# v0a.net
KiCad netlist of a schematic drawn in EAGLE
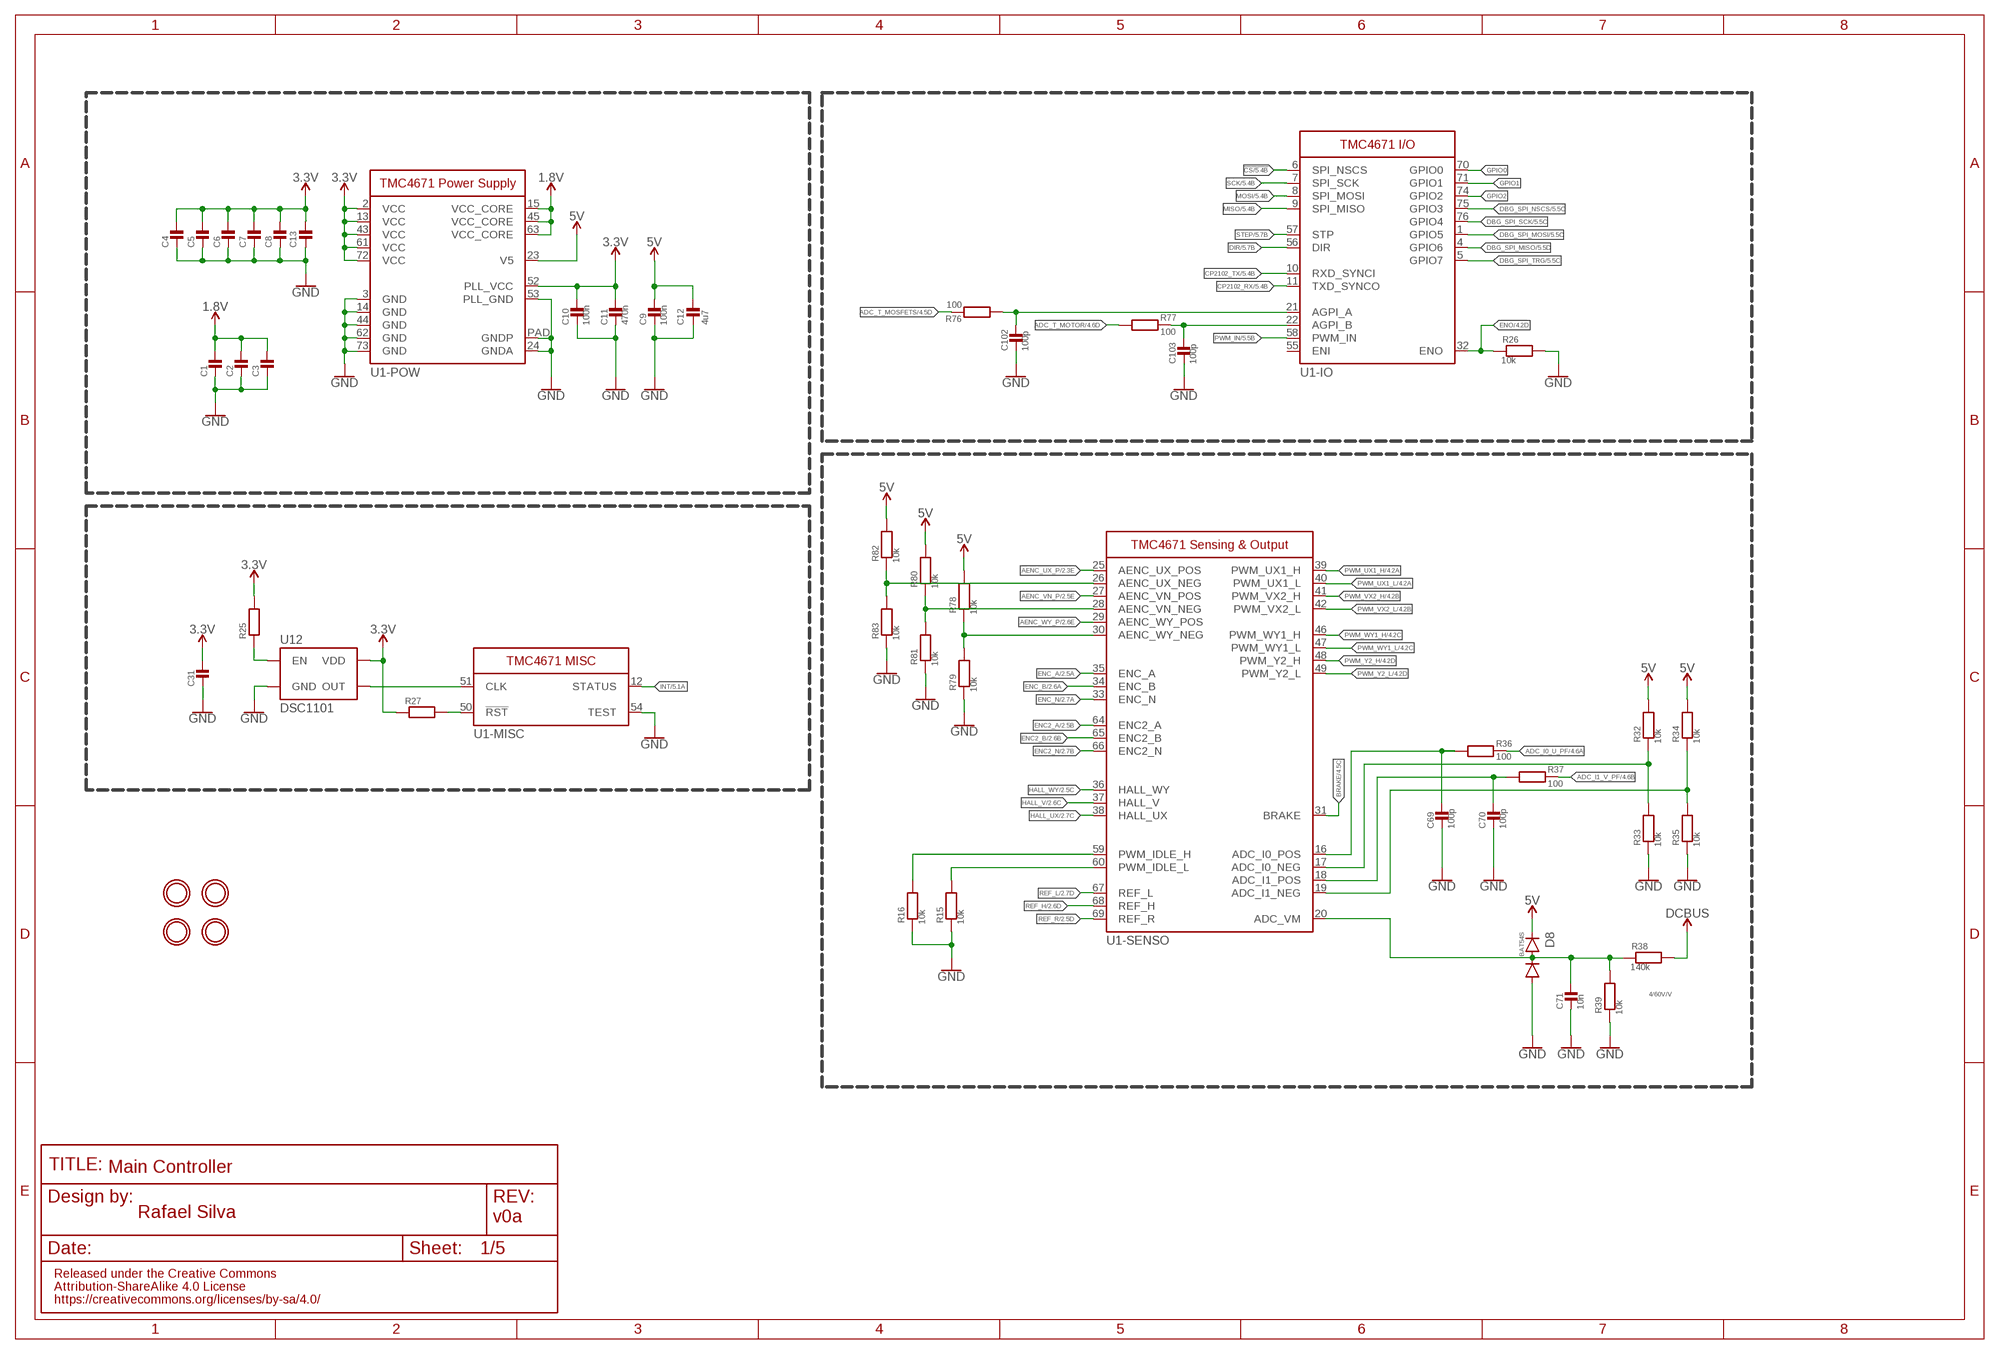
[diagram p0: schematic, sheet 1]
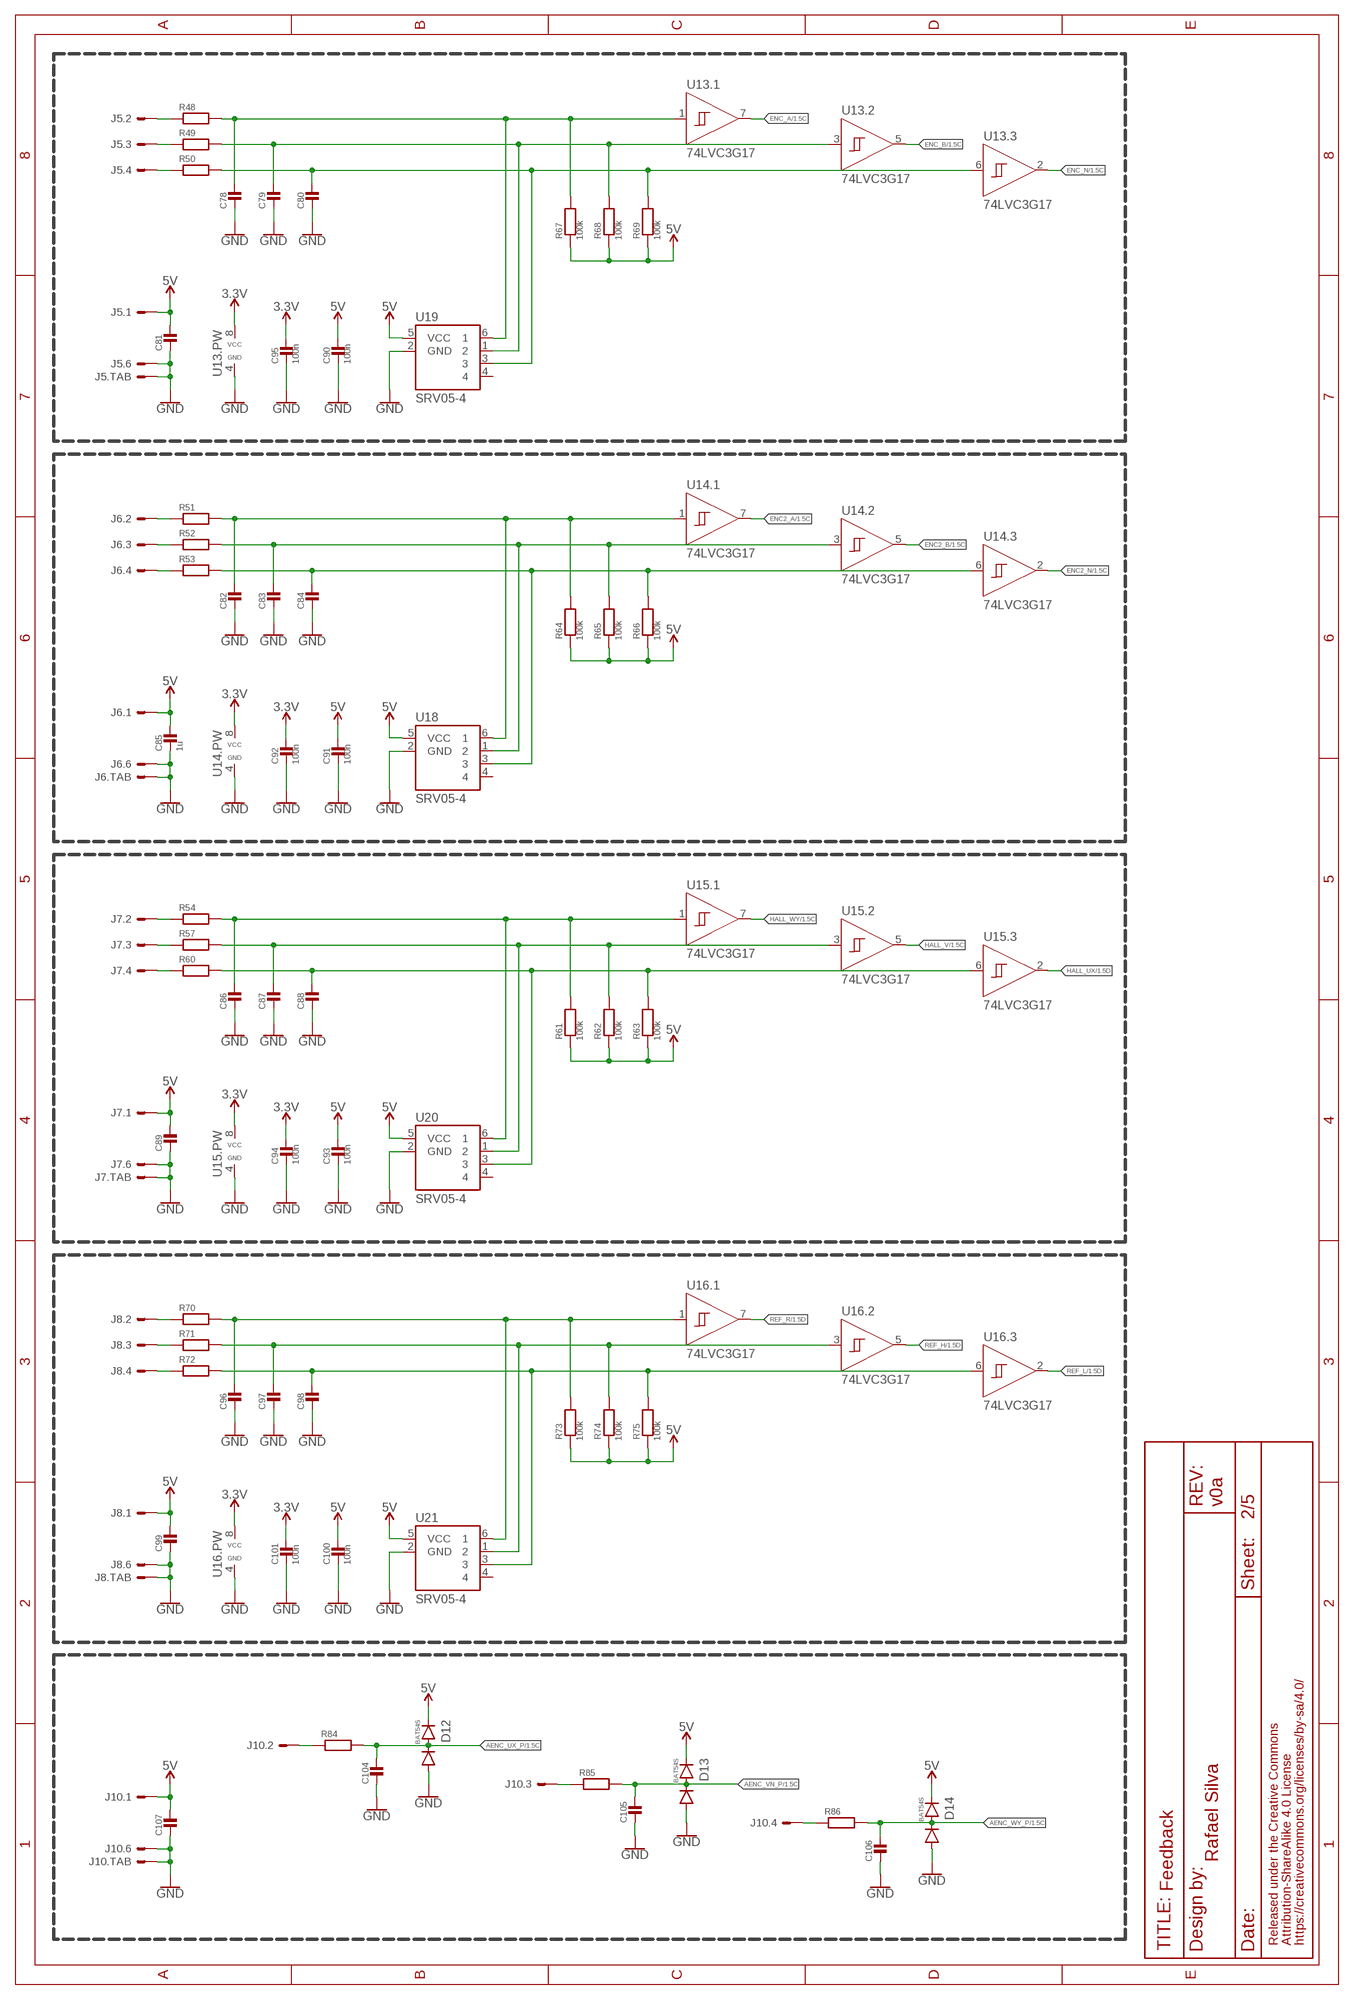
[diagram p1: schematic, sheet 2]
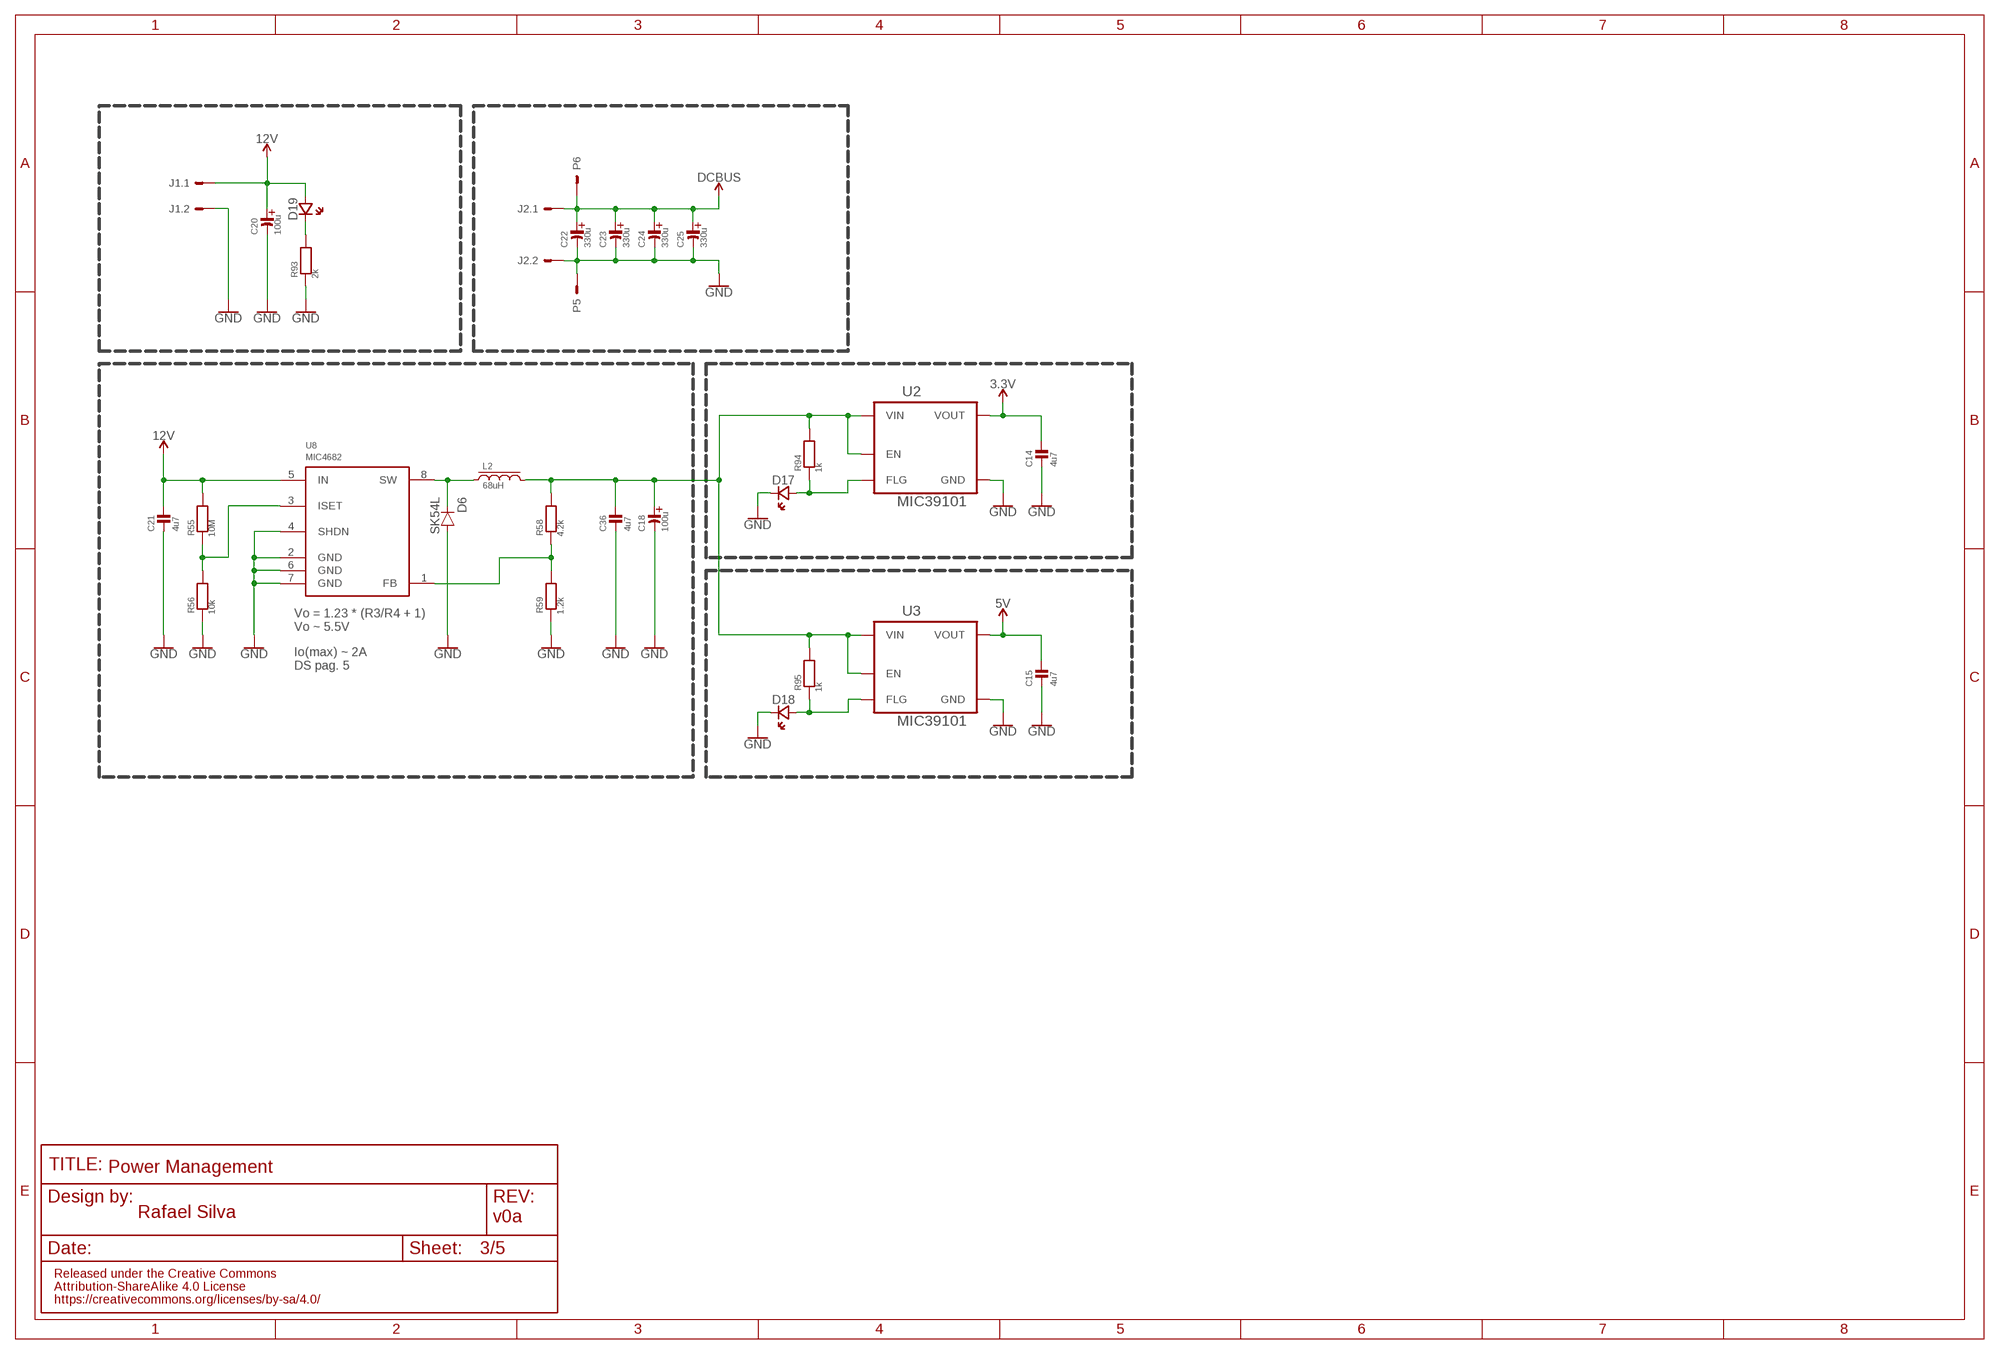
[diagram p2: schematic, sheet 3]
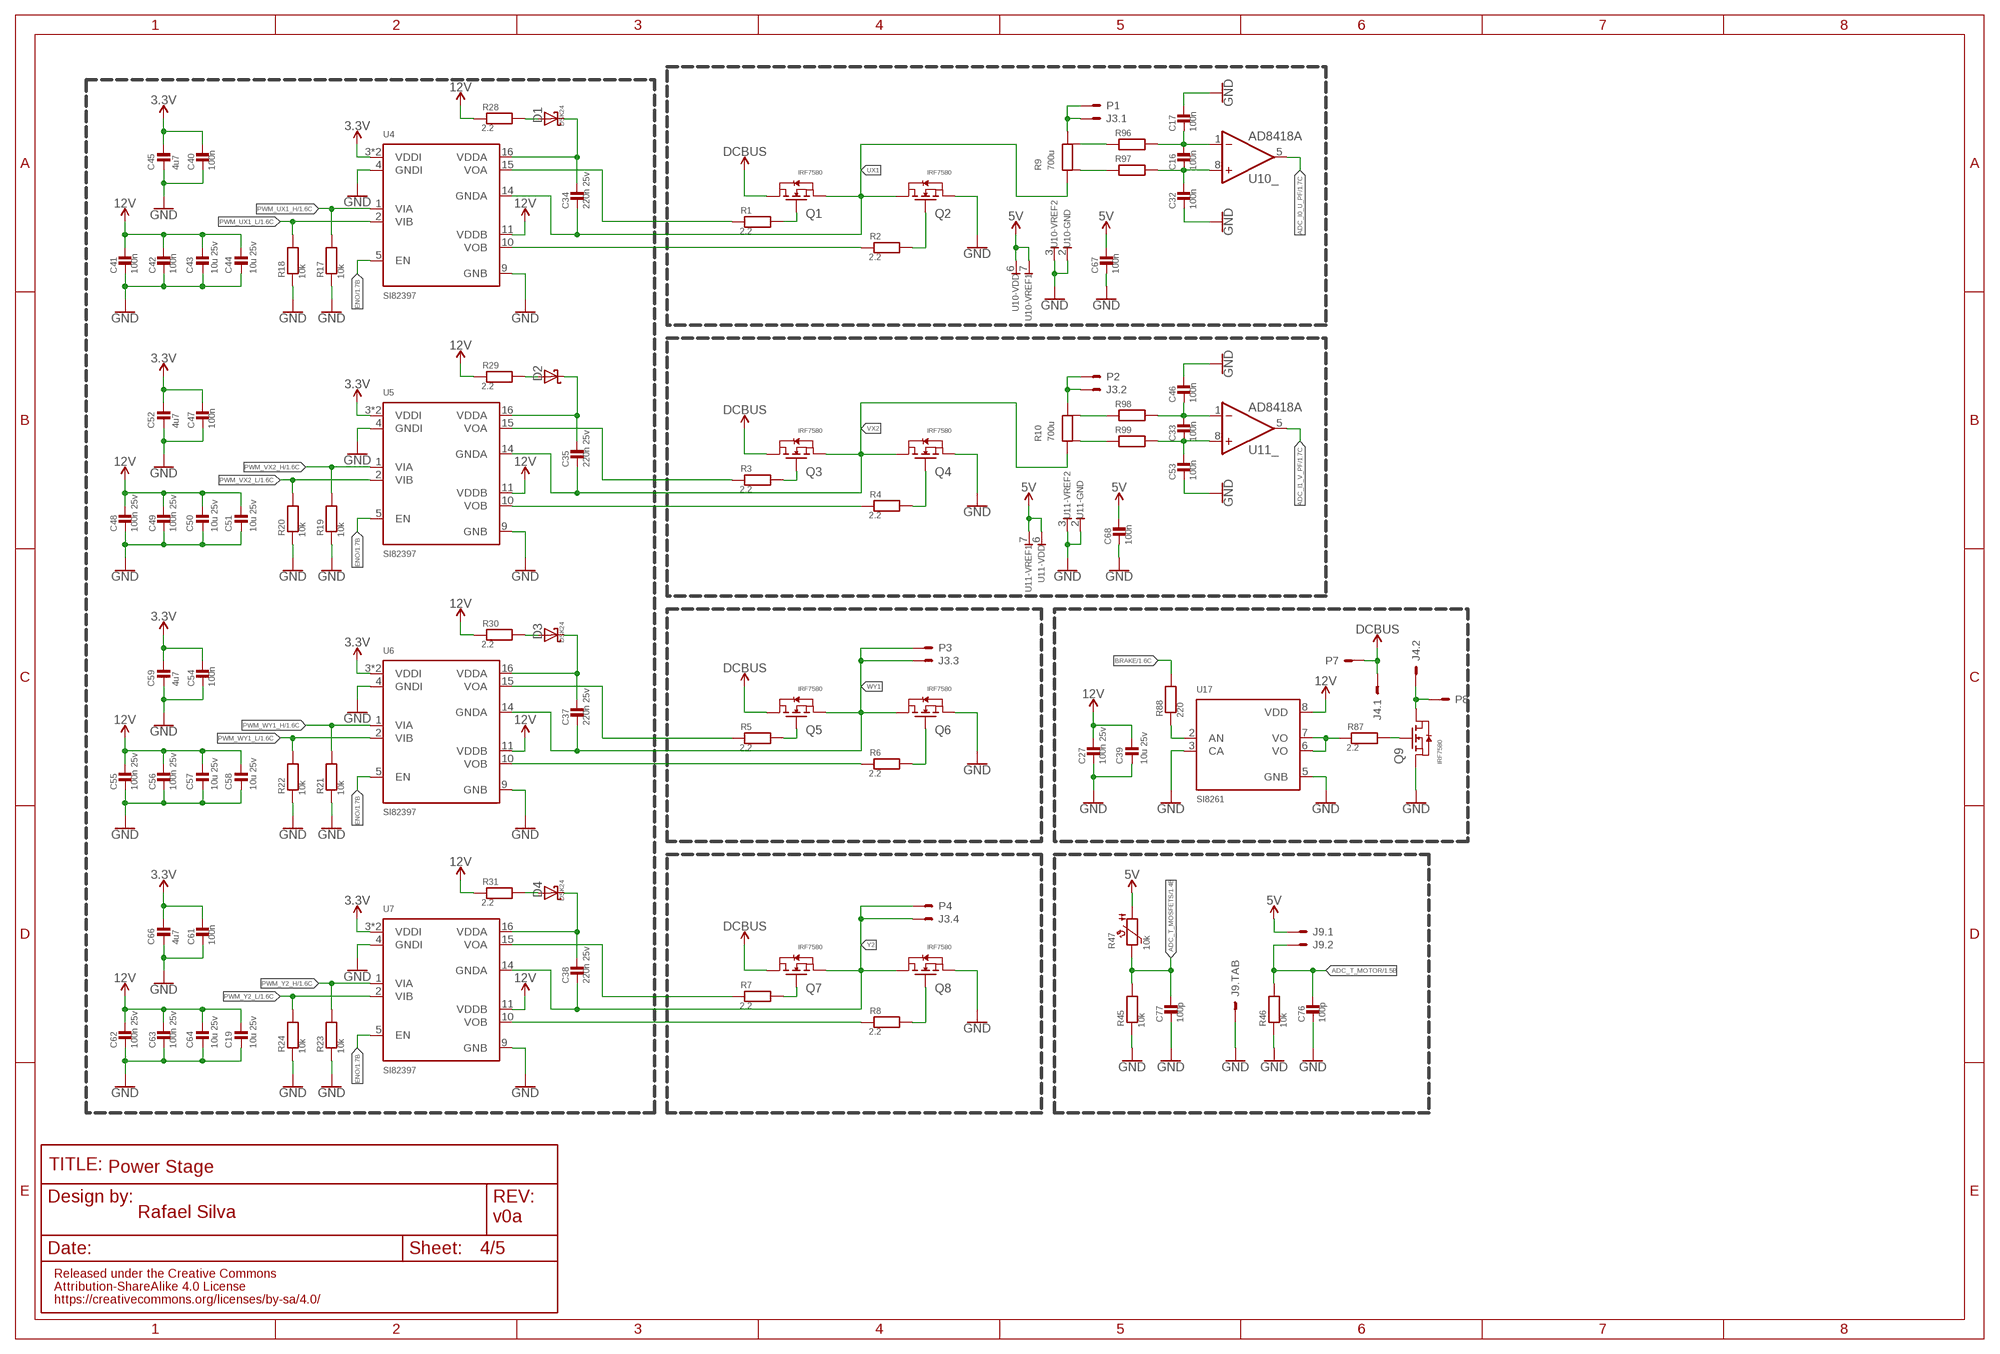
[diagram p3: schematic, sheet 4]
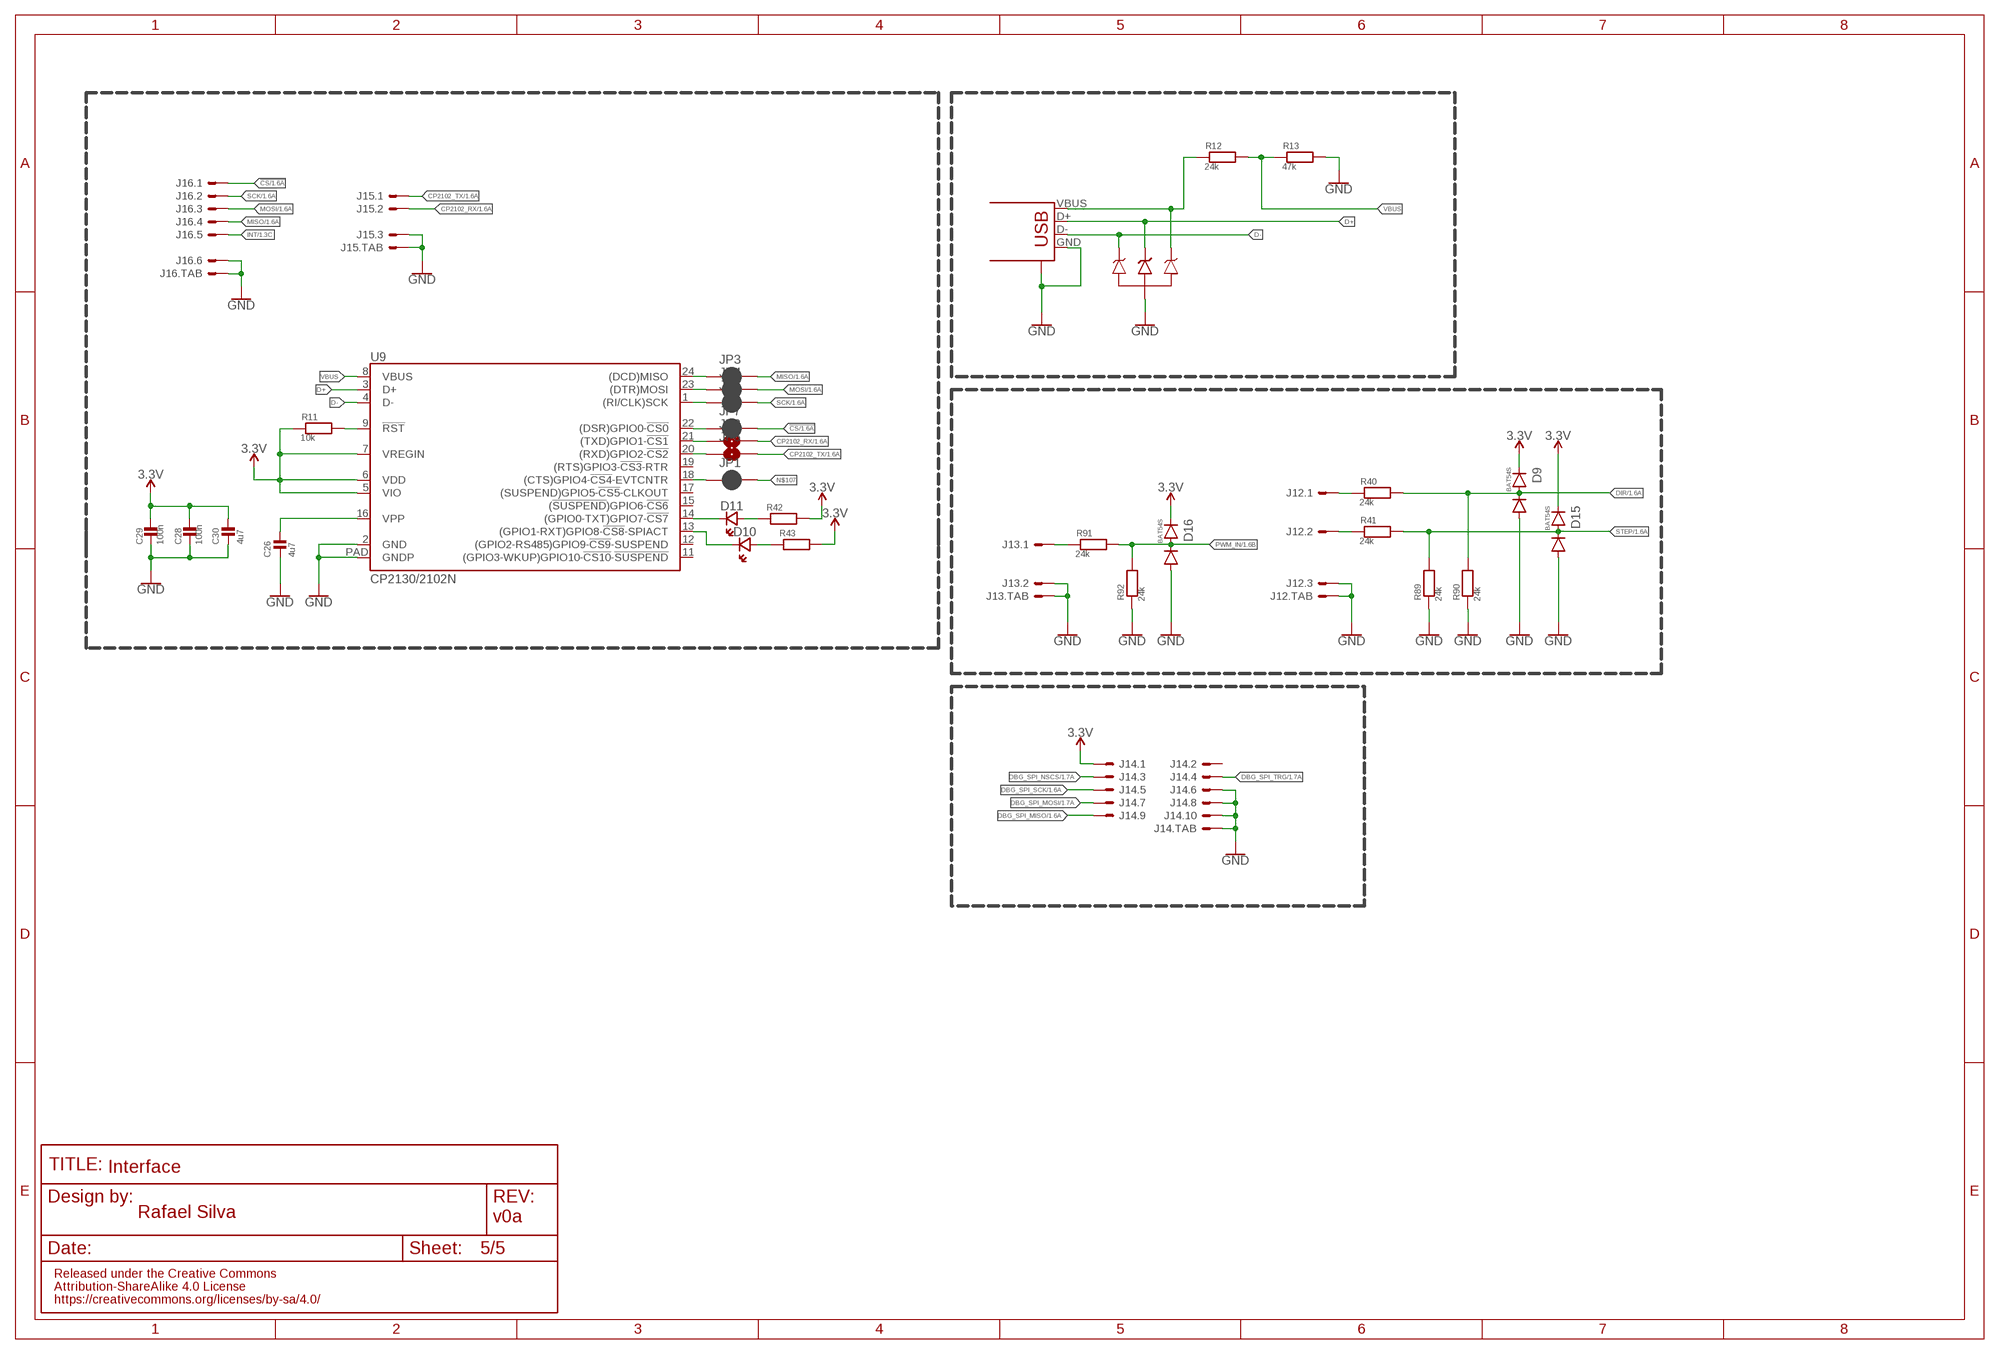
[diagram p4: schematic, sheet 5]

(export (version "E")
  (design (tool "Eeschema 10.0.6"))
  (components
    (comp (ref "C26")
      (value "4u7")
      (footprint "eagle-import:0603_WAVE")
      (libsource (lib "eagle-import") (part "MLCC0603"))
    )
    (comp (ref "C28")
      (value "100n")
      (footprint "eagle-import:0603_WAVE")
      (libsource (lib "eagle-import") (part "MLCC0603"))
    )
    (comp (ref "C29")
      (value "100n")
      (footprint "eagle-import:0603_WAVE")
      (libsource (lib "eagle-import") (part "MLCC0603"))
    )
    (comp (ref "C30")
      (value "4u7")
      (footprint "eagle-import:0603_WAVE")
      (libsource (lib "eagle-import") (part "MLCC0603"))
    )
    (comp (ref "D5")
      (value "SP0503BAHT")
      (footprint "eagle-import:SOT143")
      (libsource (lib "eagle-import") (part "SP0503BAHT"))
    )
    (comp (ref "D9")
      (value "BAT54S")
      (footprint "eagle-import:SOT-23-3")
      (libsource (lib "eagle-import") (part "BAT54S"))
    )
    (comp (ref "D10")
      (value "LED0603")
      (footprint "eagle-import:CHIPLED_0603")
      (libsource (lib "eagle-import") (part "LED0603"))
    )
    (comp (ref "D11")
      (value "LED0603")
      (footprint "eagle-import:CHIPLED_0603")
      (libsource (lib "eagle-import") (part "LED0603"))
    )
    (comp (ref "D15")
      (value "BAT54S")
      (footprint "eagle-import:SOT-23-3")
      (libsource (lib "eagle-import") (part "BAT54S"))
    )
    (comp (ref "D16")
      (value "BAT54S")
      (footprint "eagle-import:SOT-23-3")
      (libsource (lib "eagle-import") (part "BAT54S"))
    )
    (comp (ref "J12")
      (value "SH-3")
      (footprint "eagle-import:SM03B-SSR-H-TB")
      (libsource (lib "eagle-import") (part "SH-3"))
    )
    (comp (ref "J13")
      (value "SH-2")
      (footprint "eagle-import:SM02B-SSR-H-TB")
      (libsource (lib "eagle-import") (part "SH-2"))
    )
    (comp (ref "J14")
      (value "F20F-10DP-1V")
      (footprint "eagle-import:F20F-10DP-1V")
      (libsource (lib "eagle-import") (part "F20F-10DP-1V"))
    )
    (comp (ref "J15")
      (value "SH-3")
      (footprint "eagle-import:SM03B-SSR-H-TB")
      (libsource (lib "eagle-import") (part "SH-3"))
    )
    (comp (ref "J16")
      (value "SH-6")
      (footprint "eagle-import:SM06B-SSR-H-TB")
      (libsource (lib "eagle-import") (part "SH-6"))
    )
    (comp (ref "JP1")
      (value "JUMPER-SMT_2_NC_PASTE_SILK")
      (footprint "eagle-import:SMT-JUMPER_2_NC_PASTE_SILK")
      (libsource (lib "eagle-import") (part "JUMPER-SMT_2_NC_PASTE_SILK"))
    )
    (comp (ref "JP2")
      (value "JUMPER-SMT_2_NO_SILK")
      (footprint "eagle-import:SMT-JUMPER_2_NO_SILK")
      (libsource (lib "eagle-import") (part "JUMPER-SMT_2_NO_SILK"))
    )
    (comp (ref "JP3")
      (value "JUMPER-SMT_2_NC_PASTE_SILK")
      (footprint "eagle-import:SMT-JUMPER_2_NC_PASTE_SILK")
      (libsource (lib "eagle-import") (part "JUMPER-SMT_2_NC_PASTE_SILK"))
    )
    (comp (ref "JP4")
      (value "JUMPER-SMT_2_NC_PASTE_SILK")
      (footprint "eagle-import:SMT-JUMPER_2_NC_PASTE_SILK")
      (libsource (lib "eagle-import") (part "JUMPER-SMT_2_NC_PASTE_SILK"))
    )
    (comp (ref "JP5")
      (value "JUMPER-SMT_2_NC_PASTE_SILK")
      (footprint "eagle-import:SMT-JUMPER_2_NC_PASTE_SILK")
      (libsource (lib "eagle-import") (part "JUMPER-SMT_2_NC_PASTE_SILK"))
    )
    (comp (ref "JP6")
      (value "JUMPER-SMT_2_NO_SILK")
      (footprint "eagle-import:SMT-JUMPER_2_NO_SILK")
      (libsource (lib "eagle-import") (part "JUMPER-SMT_2_NO_SILK"))
    )
    (comp (ref "JP7")
      (value "JUMPER-SMT_2_NC_PASTE_SILK")
      (footprint "eagle-import:SMT-JUMPER_2_NC_PASTE_SILK")
      (libsource (lib "eagle-import") (part "JUMPER-SMT_2_NC_PASTE_SILK"))
    )
    (comp (ref "R11")
      (value "10k")
      (footprint "eagle-import:0603_WAVE")
      (libsource (lib "eagle-import") (part "RESISTOR0603"))
    )
    (comp (ref "R12")
      (value "24k")
      (footprint "eagle-import:0603_WAVE")
      (libsource (lib "eagle-import") (part "RESISTOR0603"))
    )
    (comp (ref "R13")
      (value "47k")
      (footprint "eagle-import:0603_WAVE")
      (libsource (lib "eagle-import") (part "RESISTOR0603"))
    )
    (comp (ref "R40")
      (value "24k")
      (footprint "eagle-import:0603_WAVE")
      (libsource (lib "eagle-import") (part "RESISTOR0603"))
    )
    (comp (ref "R41")
      (value "24k")
      (footprint "eagle-import:0603_WAVE")
      (libsource (lib "eagle-import") (part "RESISTOR0603"))
    )
    (comp (ref "R42")
      (value "RESISTOR0603")
      (footprint "eagle-import:0603_WAVE")
      (libsource (lib "eagle-import") (part "RESISTOR0603"))
    )
    (comp (ref "R43")
      (value "RESISTOR0603")
      (footprint "eagle-import:0603_WAVE")
      (libsource (lib "eagle-import") (part "RESISTOR0603"))
    )
    (comp (ref "R89")
      (value "24k")
      (footprint "eagle-import:0603_WAVE")
      (libsource (lib "eagle-import") (part "RESISTOR0603"))
    )
    (comp (ref "R90")
      (value "24k")
      (footprint "eagle-import:0603_WAVE")
      (libsource (lib "eagle-import") (part "RESISTOR0603"))
    )
    (comp (ref "R91")
      (value "24k")
      (footprint "eagle-import:0603_WAVE")
      (libsource (lib "eagle-import") (part "RESISTOR0603"))
    )
    (comp (ref "R92")
      (value "24k")
      (footprint "eagle-import:0603_WAVE")
      (libsource (lib "eagle-import") (part "RESISTOR0603"))
    )
    (comp (ref "U$10")
      (value "USB-SHIELD")
      (footprint "eagle-import:USB-M-S1")
      (libsource (lib "eagle-import") (part "USB-SHIELD"))
    )
    (comp (ref "U9")
      (value "CP2130/2102N")
      (footprint "eagle-import:QFN24")
      (libsource (lib "eagle-import") (part "CP2130/2102N"))
    )
    (comp (ref "C16")
      (value "100n")
      (footprint "eagle-import:0603_WAVE")
      (libsource (lib "eagle-import") (part "MLCC0603"))
    )
    (comp (ref "C17")
      (value "100n")
      (footprint "eagle-import:0603_WAVE")
      (libsource (lib "eagle-import") (part "MLCC0603"))
    )
    (comp (ref "C19")
      (value "10u 25v")
      (footprint "eagle-import:0603_WAVE")
      (libsource (lib "eagle-import") (part "MLCC0603"))
    )
    (comp (ref "C27")
      (value "100n 25v")
      (footprint "eagle-import:0603_WAVE")
      (libsource (lib "eagle-import") (part "MLCC0603"))
    )
    (comp (ref "C32")
      (value "100n")
      (footprint "eagle-import:0603_WAVE")
      (libsource (lib "eagle-import") (part "MLCC0603"))
    )
    (comp (ref "C33")
      (value "100n")
      (footprint "eagle-import:0603_WAVE")
      (libsource (lib "eagle-import") (part "MLCC0603"))
    )
    (comp (ref "C34")
      (value "220n 25v")
      (footprint "eagle-import:0603_WAVE")
      (libsource (lib "eagle-import") (part "MLCC0603"))
    )
    (comp (ref "C35")
      (value "220n 25v")
      (footprint "eagle-import:0603_WAVE")
      (libsource (lib "eagle-import") (part "MLCC0603"))
    )
    (comp (ref "C37")
      (value "220n 25v")
      (footprint "eagle-import:0603_WAVE")
      (libsource (lib "eagle-import") (part "MLCC0603"))
    )
    (comp (ref "C38")
      (value "220n 25v")
      (footprint "eagle-import:0603_WAVE")
      (libsource (lib "eagle-import") (part "MLCC0603"))
    )
    (comp (ref "C39")
      (value "10u 25v")
      (footprint "eagle-import:0603_WAVE")
      (libsource (lib "eagle-import") (part "MLCC0603"))
    )
    (comp (ref "C40")
      (value "100n")
      (footprint "eagle-import:0603_WAVE")
      (libsource (lib "eagle-import") (part "MLCC0603"))
    )
    (comp (ref "C41")
      (value "100n")
      (footprint "eagle-import:0603_WAVE")
      (libsource (lib "eagle-import") (part "MLCC0603"))
    )
    (comp (ref "C42")
      (value "100n")
      (footprint "eagle-import:0603_WAVE")
      (libsource (lib "eagle-import") (part "MLCC0603"))
    )
    (comp (ref "C43")
      (value "10u 25v")
      (footprint "eagle-import:0603_WAVE")
      (libsource (lib "eagle-import") (part "MLCC0603"))
    )
    (comp (ref "C44")
      (value "10u 25v")
      (footprint "eagle-import:0603_WAVE")
      (libsource (lib "eagle-import") (part "MLCC0603"))
    )
    (comp (ref "C45")
      (value "4u7")
      (footprint "eagle-import:0603_WAVE")
      (libsource (lib "eagle-import") (part "MLCC0603"))
    )
    (comp (ref "C46")
      (value "100n")
      (footprint "eagle-import:0603_WAVE")
      (libsource (lib "eagle-import") (part "MLCC0603"))
    )
    (comp (ref "C47")
      (value "100n")
      (footprint "eagle-import:0603_WAVE")
      (libsource (lib "eagle-import") (part "MLCC0603"))
    )
    (comp (ref "C48")
      (value "100n 25v")
      (footprint "eagle-import:0603_WAVE")
      (libsource (lib "eagle-import") (part "MLCC0603"))
    )
    (comp (ref "C49")
      (value "100n 25v")
      (footprint "eagle-import:0603_WAVE")
      (libsource (lib "eagle-import") (part "MLCC0603"))
    )
    (comp (ref "C50")
      (value "10u 25v")
      (footprint "eagle-import:0603_WAVE")
      (libsource (lib "eagle-import") (part "MLCC0603"))
    )
    (comp (ref "C51")
      (value "10u 25v")
      (footprint "eagle-import:0603_WAVE")
      (libsource (lib "eagle-import") (part "MLCC0603"))
    )
    (comp (ref "C52")
      (value "4u7")
      (footprint "eagle-import:0603_WAVE")
      (libsource (lib "eagle-import") (part "MLCC0603"))
    )
    (comp (ref "C53")
      (value "100n")
      (footprint "eagle-import:0603_WAVE")
      (libsource (lib "eagle-import") (part "MLCC0603"))
    )
    (comp (ref "C54")
      (value "100n")
      (footprint "eagle-import:0603_WAVE")
      (libsource (lib "eagle-import") (part "MLCC0603"))
    )
    (comp (ref "C55")
      (value "100n 25v")
      (footprint "eagle-import:0603_WAVE")
      (libsource (lib "eagle-import") (part "MLCC0603"))
    )
    (comp (ref "C56")
      (value "100n 25v")
      (footprint "eagle-import:0603_WAVE")
      (libsource (lib "eagle-import") (part "MLCC0603"))
    )
    (comp (ref "C57")
      (value "10u 25v")
      (footprint "eagle-import:0603_WAVE")
      (libsource (lib "eagle-import") (part "MLCC0603"))
    )
    (comp (ref "C58")
      (value "10u 25v")
      (footprint "eagle-import:0603_WAVE")
      (libsource (lib "eagle-import") (part "MLCC0603"))
    )
    (comp (ref "C59")
      (value "4u7")
      (footprint "eagle-import:0603_WAVE")
      (libsource (lib "eagle-import") (part "MLCC0603"))
    )
    (comp (ref "C61")
      (value "100n")
      (footprint "eagle-import:0603_WAVE")
      (libsource (lib "eagle-import") (part "MLCC0603"))
    )
    (comp (ref "C62")
      (value "100n 25v")
      (footprint "eagle-import:0603_WAVE")
      (libsource (lib "eagle-import") (part "MLCC0603"))
    )
    (comp (ref "C63")
      (value "100n 25v")
      (footprint "eagle-import:0603_WAVE")
      (libsource (lib "eagle-import") (part "MLCC0603"))
    )
    (comp (ref "C64")
      (value "10u 25v")
      (footprint "eagle-import:0603_WAVE")
      (libsource (lib "eagle-import") (part "MLCC0603"))
    )
    (comp (ref "C66")
      (value "4u7")
      (footprint "eagle-import:0603_WAVE")
      (libsource (lib "eagle-import") (part "MLCC0603"))
    )
    (comp (ref "C67")
      (value "100n")
      (footprint "eagle-import:0603_WAVE")
      (libsource (lib "eagle-import") (part "MLCC0603"))
    )
    (comp (ref "C68")
      (value "100n")
      (footprint "eagle-import:0603_WAVE")
      (libsource (lib "eagle-import") (part "MLCC0603"))
    )
    (comp (ref "C76")
      (value "100p")
      (footprint "eagle-import:0603_WAVE")
      (libsource (lib "eagle-import") (part "MLCC0603"))
    )
    (comp (ref "C77")
      (value "100p")
      (footprint "eagle-import:0603_WAVE")
      (libsource (lib "eagle-import") (part "MLCC0603"))
    )
    (comp (ref "D1")
      (value "DSK24")
      (footprint "eagle-import:SOD-123")
      (libsource (lib "eagle-import") (part "DSK24"))
    )
    (comp (ref "D2")
      (value "DSK24")
      (footprint "eagle-import:SOD-123")
      (libsource (lib "eagle-import") (part "DSK24"))
    )
    (comp (ref "D3")
      (value "DSK24")
      (footprint "eagle-import:SOD-123")
      (libsource (lib "eagle-import") (part "DSK24"))
    )
    (comp (ref "D4")
      (value "DSK24")
      (footprint "eagle-import:SOD-123")
      (libsource (lib "eagle-import") (part "DSK24"))
    )
    (comp (ref "J3")
      (value "4P-6.35P")
      (footprint "eagle-import:4P-6.35P")
      (libsource (lib "eagle-import") (part "4P-6.35P"))
    )
    (comp (ref "J4")
      (value "2P-6.35P")
      (footprint "eagle-import:2P-6.35P")
      (libsource (lib "eagle-import") (part "2P-6.35P"))
    )
    (comp (ref "J9")
      (value "SH-2")
      (footprint "eagle-import:SM02B-SSR-H-TB")
      (libsource (lib "eagle-import") (part "SH-2"))
    )
    (comp (ref "P1")
      (value "POWPAD")
      (footprint "eagle-import:TH-HP")
      (libsource (lib "eagle-import") (part "POWPAD"))
    )
    (comp (ref "P2")
      (value "POWPAD")
      (footprint "eagle-import:TH-HP")
      (libsource (lib "eagle-import") (part "POWPAD"))
    )
    (comp (ref "P3")
      (value "POWPAD")
      (footprint "eagle-import:TH-HP")
      (libsource (lib "eagle-import") (part "POWPAD"))
    )
    (comp (ref "P4")
      (value "POWPAD")
      (footprint "eagle-import:TH-HP")
      (libsource (lib "eagle-import") (part "POWPAD"))
    )
    (comp (ref "P7")
      (value "POWPAD")
      (footprint "eagle-import:TH-HP")
      (libsource (lib "eagle-import") (part "POWPAD"))
    )
    (comp (ref "P8")
      (value "POWPAD")
      (footprint "eagle-import:TH-HP")
      (libsource (lib "eagle-import") (part "POWPAD"))
    )
    (comp (ref "Q1")
      (value "IRF7580")
      (footprint "eagle-import:DIRECTFET-ME")
      (libsource (lib "eagle-import") (part "IRF7580"))
    )
    (comp (ref "Q2")
      (value "IRF7580")
      (footprint "eagle-import:DIRECTFET-ME")
      (libsource (lib "eagle-import") (part "IRF7580"))
    )
    (comp (ref "Q3")
      (value "IRF7580")
      (footprint "eagle-import:DIRECTFET-ME")
      (libsource (lib "eagle-import") (part "IRF7580"))
    )
    (comp (ref "Q4")
      (value "IRF7580")
      (footprint "eagle-import:DIRECTFET-ME")
      (libsource (lib "eagle-import") (part "IRF7580"))
    )
    (comp (ref "Q5")
      (value "IRF7580")
      (footprint "eagle-import:DIRECTFET-ME")
      (libsource (lib "eagle-import") (part "IRF7580"))
    )
    (comp (ref "Q6")
      (value "IRF7580")
      (footprint "eagle-import:DIRECTFET-ME")
      (libsource (lib "eagle-import") (part "IRF7580"))
    )
    (comp (ref "Q7")
      (value "IRF7580")
      (footprint "eagle-import:DIRECTFET-ME")
      (libsource (lib "eagle-import") (part "IRF7580"))
    )
    (comp (ref "Q8")
      (value "IRF7580")
      (footprint "eagle-import:DIRECTFET-ME")
      (libsource (lib "eagle-import") (part "IRF7580"))
    )
    (comp (ref "Q9")
      (value "IRF7580")
      (footprint "eagle-import:DIRECTFET-ME")
      (libsource (lib "eagle-import") (part "IRF7580"))
    )
    (comp (ref "R1")
      (value "2.2")
      (footprint "eagle-import:0603_WAVE")
      (libsource (lib "eagle-import") (part "RESISTOR0603"))
    )
    (comp (ref "R2")
      (value "2.2")
      (footprint "eagle-import:0603_WAVE")
      (libsource (lib "eagle-import") (part "RESISTOR0603"))
    )
    (comp (ref "R3")
      (value "2.2")
      (footprint "eagle-import:0603_WAVE")
      (libsource (lib "eagle-import") (part "RESISTOR0603"))
    )
    (comp (ref "R4")
      (value "2.2")
      (footprint "eagle-import:0603_WAVE")
      (libsource (lib "eagle-import") (part "RESISTOR0603"))
    )
    (comp (ref "R5")
      (value "2.2")
      (footprint "eagle-import:0603_WAVE")
      (libsource (lib "eagle-import") (part "RESISTOR0603"))
    )
    (comp (ref "R6")
      (value "2.2")
      (footprint "eagle-import:0603_WAVE")
      (libsource (lib "eagle-import") (part "RESISTOR0603"))
    )
    (comp (ref "R7")
      (value "2.2")
      (footprint "eagle-import:0603_WAVE")
      (libsource (lib "eagle-import") (part "RESISTOR0603"))
    )
    (comp (ref "R8")
      (value "2.2")
      (footprint "eagle-import:0603_WAVE")
      (libsource (lib "eagle-import") (part "RESISTOR0603"))
    )
    (comp (ref "R9")
      (value "700u")
      (footprint "eagle-import:3920")
      (libsource (lib "eagle-import") (part "LRMAP3920"))
    )
    (comp (ref "R10")
      (value "700u")
      (footprint "eagle-import:3920")
      (libsource (lib "eagle-import") (part "LRMAP3920"))
    )
    (comp (ref "R17")
      (value "10k")
      (footprint "eagle-import:0603_WAVE")
      (libsource (lib "eagle-import") (part "RESISTOR0603"))
    )
    (comp (ref "R18")
      (value "10k")
      (footprint "eagle-import:0603_WAVE")
      (libsource (lib "eagle-import") (part "RESISTOR0603"))
    )
    (comp (ref "R19")
      (value "10k")
      (footprint "eagle-import:0603_WAVE")
      (libsource (lib "eagle-import") (part "RESISTOR0603"))
    )
    (comp (ref "R20")
      (value "10k")
      (footprint "eagle-import:0603_WAVE")
      (libsource (lib "eagle-import") (part "RESISTOR0603"))
    )
    (comp (ref "R21")
      (value "10k")
      (footprint "eagle-import:0603_WAVE")
      (libsource (lib "eagle-import") (part "RESISTOR0603"))
    )
    (comp (ref "R22")
      (value "10k")
      (footprint "eagle-import:0603_WAVE")
      (libsource (lib "eagle-import") (part "RESISTOR0603"))
    )
    (comp (ref "R23")
      (value "10k")
      (footprint "eagle-import:0603_WAVE")
      (libsource (lib "eagle-import") (part "RESISTOR0603"))
    )
    (comp (ref "R24")
      (value "10k")
      (footprint "eagle-import:0603_WAVE")
      (libsource (lib "eagle-import") (part "RESISTOR0603"))
    )
    (comp (ref "R28")
      (value "2.2")
      (footprint "eagle-import:0603_WAVE")
      (libsource (lib "eagle-import") (part "RESISTOR0603"))
    )
    (comp (ref "R29")
      (value "2.2")
      (footprint "eagle-import:0603_WAVE")
      (libsource (lib "eagle-import") (part "RESISTOR0603"))
    )
    (comp (ref "R30")
      (value "2.2")
      (footprint "eagle-import:0603_WAVE")
      (libsource (lib "eagle-import") (part "RESISTOR0603"))
    )
    (comp (ref "R31")
      (value "2.2")
      (footprint "eagle-import:0603_WAVE")
      (libsource (lib "eagle-import") (part "RESISTOR0603"))
    )
    (comp (ref "R45")
      (value "10k")
      (footprint "eagle-import:0603_WAVE")
      (libsource (lib "eagle-import") (part "RESISTOR0603"))
    )
    (comp (ref "R46")
      (value "10k")
      (footprint "eagle-import:0603_WAVE")
      (libsource (lib "eagle-import") (part "RESISTOR0603"))
    )
    (comp (ref "R47")
      (value "10k")
      (footprint "eagle-import:0603_WAVE")
      (libsource (lib "eagle-import") (part "NTC0603"))
    )
    (comp (ref "R87")
      (value "2.2")
      (footprint "eagle-import:0603_WAVE")
      (libsource (lib "eagle-import") (part "RESISTOR0603"))
    )
    (comp (ref "R88")
      (value "220")
      (footprint "eagle-import:0603_WAVE")
      (libsource (lib "eagle-import") (part "RESISTOR0603"))
    )
    (comp (ref "R96")
      (value "RESISTOR0603")
      (footprint "eagle-import:0603_WAVE")
      (libsource (lib "eagle-import") (part "RESISTOR0603"))
    )
    (comp (ref "R97")
      (value "RESISTOR0603")
      (footprint "eagle-import:0603_WAVE")
      (libsource (lib "eagle-import") (part "RESISTOR0603"))
    )
    (comp (ref "R98")
      (value "RESISTOR0603")
      (footprint "eagle-import:0603_WAVE")
      (libsource (lib "eagle-import") (part "RESISTOR0603"))
    )
    (comp (ref "R99")
      (value "RESISTOR0603")
      (footprint "eagle-import:0603_WAVE")
      (libsource (lib "eagle-import") (part "RESISTOR0603"))
    )
    (comp (ref "U4")
      (value "SI82397")
      (footprint "eagle-import:SOIC-16-WB")
      (libsource (lib "eagle-import") (part "SI82397"))
    )
    (comp (ref "U5")
      (value "SI82397")
      (footprint "eagle-import:SOIC-16-WB")
      (libsource (lib "eagle-import") (part "SI82397"))
    )
    (comp (ref "U6")
      (value "SI82397")
      (footprint "eagle-import:SOIC-16-WB")
      (libsource (lib "eagle-import") (part "SI82397"))
    )
    (comp (ref "U7")
      (value "SI82397")
      (footprint "eagle-import:SOIC-16-WB")
      (libsource (lib "eagle-import") (part "SI82397"))
    )
    (comp (ref "U10")
      (value "AD8418A")
      (footprint "eagle-import:MSOP-8")
      (libsource (lib "eagle-import") (part "AD8418A"))
    )
    (comp (ref "U11")
      (value "AD8418A")
      (footprint "eagle-import:MSOP-8")
      (libsource (lib "eagle-import") (part "AD8418A"))
    )
    (comp (ref "U17")
      (value "SI8261")
      (footprint "eagle-import:SOIC_8")
      (libsource (lib "eagle-import") (part "SI8261"))
    )
    (comp (ref "C78")
      (value "MLCC0603")
      (footprint "eagle-import:0603_WAVE")
      (libsource (lib "eagle-import") (part "MLCC0603"))
    )
    (comp (ref "C79")
      (value "MLCC0603")
      (footprint "eagle-import:0603_WAVE")
      (libsource (lib "eagle-import") (part "MLCC0603"))
    )
    (comp (ref "C80")
      (value "MLCC0603")
      (footprint "eagle-import:0603_WAVE")
      (libsource (lib "eagle-import") (part "MLCC0603"))
    )
    (comp (ref "C81")
      (value "MLCC0603")
      (footprint "eagle-import:0603_WAVE")
      (libsource (lib "eagle-import") (part "MLCC0603"))
    )
    (comp (ref "C82")
      (value "MLCC0603")
      (footprint "eagle-import:0603_WAVE")
      (libsource (lib "eagle-import") (part "MLCC0603"))
    )
    (comp (ref "C83")
      (value "MLCC0603")
      (footprint "eagle-import:0603_WAVE")
      (libsource (lib "eagle-import") (part "MLCC0603"))
    )
    (comp (ref "C84")
      (value "MLCC0603")
      (footprint "eagle-import:0603_WAVE")
      (libsource (lib "eagle-import") (part "MLCC0603"))
    )
    (comp (ref "C85")
      (value "1u")
      (footprint "eagle-import:0603_WAVE")
      (libsource (lib "eagle-import") (part "MLCC0603"))
    )
    (comp (ref "C86")
      (value "MLCC0603")
      (footprint "eagle-import:0603_WAVE")
      (libsource (lib "eagle-import") (part "MLCC0603"))
    )
    (comp (ref "C87")
      (value "MLCC0603")
      (footprint "eagle-import:0603_WAVE")
      (libsource (lib "eagle-import") (part "MLCC0603"))
    )
    (comp (ref "C88")
      (value "MLCC0603")
      (footprint "eagle-import:0603_WAVE")
      (libsource (lib "eagle-import") (part "MLCC0603"))
    )
    (comp (ref "C89")
      (value "MLCC0603")
      (footprint "eagle-import:0603_WAVE")
      (libsource (lib "eagle-import") (part "MLCC0603"))
    )
    (comp (ref "C90")
      (value "100n")
      (footprint "eagle-import:0603_WAVE")
      (libsource (lib "eagle-import") (part "MLCC0603"))
    )
    (comp (ref "C91")
      (value "100n")
      (footprint "eagle-import:0603_WAVE")
      (libsource (lib "eagle-import") (part "MLCC0603"))
    )
    (comp (ref "C92")
      (value "100n")
      (footprint "eagle-import:0603_WAVE")
      (libsource (lib "eagle-import") (part "MLCC0603"))
    )
    (comp (ref "C93")
      (value "100n")
      (footprint "eagle-import:0603_WAVE")
      (libsource (lib "eagle-import") (part "MLCC0603"))
    )
    (comp (ref "C94")
      (value "100n")
      (footprint "eagle-import:0603_WAVE")
      (libsource (lib "eagle-import") (part "MLCC0603"))
    )
    (comp (ref "C95")
      (value "100n")
      (footprint "eagle-import:0603_WAVE")
      (libsource (lib "eagle-import") (part "MLCC0603"))
    )
    (comp (ref "C96")
      (value "MLCC0603")
      (footprint "eagle-import:0603_WAVE")
      (libsource (lib "eagle-import") (part "MLCC0603"))
    )
    (comp (ref "C97")
      (value "MLCC0603")
      (footprint "eagle-import:0603_WAVE")
      (libsource (lib "eagle-import") (part "MLCC0603"))
    )
    (comp (ref "C98")
      (value "MLCC0603")
      (footprint "eagle-import:0603_WAVE")
      (libsource (lib "eagle-import") (part "MLCC0603"))
    )
    (comp (ref "C99")
      (value "MLCC0603")
      (footprint "eagle-import:0603_WAVE")
      (libsource (lib "eagle-import") (part "MLCC0603"))
    )
    (comp (ref "C100")
      (value "100n")
      (footprint "eagle-import:0603_WAVE")
      (libsource (lib "eagle-import") (part "MLCC0603"))
    )
    (comp (ref "C101")
      (value "100n")
      (footprint "eagle-import:0603_WAVE")
      (libsource (lib "eagle-import") (part "MLCC0603"))
    )
    (comp (ref "C104")
      (value "MLCC0603")
      (footprint "eagle-import:0603_WAVE")
      (libsource (lib "eagle-import") (part "MLCC0603"))
    )
    (comp (ref "C105")
      (value "MLCC0603")
      (footprint "eagle-import:0603_WAVE")
      (libsource (lib "eagle-import") (part "MLCC0603"))
    )
    (comp (ref "C106")
      (value "MLCC0603")
      (footprint "eagle-import:0603_WAVE")
      (libsource (lib "eagle-import") (part "MLCC0603"))
    )
    (comp (ref "C107")
      (value "MLCC0603")
      (footprint "eagle-import:0603_WAVE")
      (libsource (lib "eagle-import") (part "MLCC0603"))
    )
    (comp (ref "D12")
      (value "BAT54S")
      (footprint "eagle-import:SOT-23-3")
      (libsource (lib "eagle-import") (part "BAT54S"))
    )
    (comp (ref "D13")
      (value "BAT54S")
      (footprint "eagle-import:SOT-23-3")
      (libsource (lib "eagle-import") (part "BAT54S"))
    )
    (comp (ref "D14")
      (value "BAT54S")
      (footprint "eagle-import:SOT-23-3")
      (libsource (lib "eagle-import") (part "BAT54S"))
    )
    (comp (ref "J5")
      (value "SH-5")
      (footprint "eagle-import:SM05B-SSR-H-TB")
      (libsource (lib "eagle-import") (part "SH-5"))
    )
    (comp (ref "J6")
      (value "SH-5")
      (footprint "eagle-import:SM05B-SSR-H-TB")
      (libsource (lib "eagle-import") (part "SH-5"))
    )
    (comp (ref "J7")
      (value "SH-5")
      (footprint "eagle-import:SM05B-SSR-H-TB")
      (libsource (lib "eagle-import") (part "SH-5"))
    )
    (comp (ref "J8")
      (value "SH-5")
      (footprint "eagle-import:SM05B-SSR-H-TB")
      (libsource (lib "eagle-import") (part "SH-5"))
    )
    (comp (ref "J10")
      (value "SH-5")
      (footprint "eagle-import:SM05B-SSR-H-TB")
      (libsource (lib "eagle-import") (part "SH-5"))
    )
    (comp (ref "R48")
      (value "RESISTOR0603")
      (footprint "eagle-import:0603_WAVE")
      (libsource (lib "eagle-import") (part "RESISTOR0603"))
    )
    (comp (ref "R49")
      (value "RESISTOR0603")
      (footprint "eagle-import:0603_WAVE")
      (libsource (lib "eagle-import") (part "RESISTOR0603"))
    )
    (comp (ref "R50")
      (value "RESISTOR0603")
      (footprint "eagle-import:0603_WAVE")
      (libsource (lib "eagle-import") (part "RESISTOR0603"))
    )
    (comp (ref "R51")
      (value "RESISTOR0603")
      (footprint "eagle-import:0603_WAVE")
      (libsource (lib "eagle-import") (part "RESISTOR0603"))
    )
    (comp (ref "R52")
      (value "RESISTOR0603")
      (footprint "eagle-import:0603_WAVE")
      (libsource (lib "eagle-import") (part "RESISTOR0603"))
    )
    (comp (ref "R53")
      (value "RESISTOR0603")
      (footprint "eagle-import:0603_WAVE")
      (libsource (lib "eagle-import") (part "RESISTOR0603"))
    )
    (comp (ref "R54")
      (value "RESISTOR0603")
      (footprint "eagle-import:0603_WAVE")
      (libsource (lib "eagle-import") (part "RESISTOR0603"))
    )
    (comp (ref "R57")
      (value "RESISTOR0603")
      (footprint "eagle-import:0603_WAVE")
      (libsource (lib "eagle-import") (part "RESISTOR0603"))
    )
    (comp (ref "R60")
      (value "RESISTOR0603")
      (footprint "eagle-import:0603_WAVE")
      (libsource (lib "eagle-import") (part "RESISTOR0603"))
    )
    (comp (ref "R61")
      (value "100k")
      (footprint "eagle-import:0603_WAVE")
      (libsource (lib "eagle-import") (part "RESISTOR0603"))
    )
    (comp (ref "R62")
      (value "100k")
      (footprint "eagle-import:0603_WAVE")
      (libsource (lib "eagle-import") (part "RESISTOR0603"))
    )
    (comp (ref "R63")
      (value "100k")
      (footprint "eagle-import:0603_WAVE")
      (libsource (lib "eagle-import") (part "RESISTOR0603"))
    )
    (comp (ref "R64")
      (value "100k")
      (footprint "eagle-import:0603_WAVE")
      (libsource (lib "eagle-import") (part "RESISTOR0603"))
    )
    (comp (ref "R65")
      (value "100k")
      (footprint "eagle-import:0603_WAVE")
      (libsource (lib "eagle-import") (part "RESISTOR0603"))
    )
    (comp (ref "R66")
      (value "100k")
      (footprint "eagle-import:0603_WAVE")
      (libsource (lib "eagle-import") (part "RESISTOR0603"))
    )
    (comp (ref "R67")
      (value "100k")
      (footprint "eagle-import:0603_WAVE")
      (libsource (lib "eagle-import") (part "RESISTOR0603"))
    )
    (comp (ref "R68")
      (value "100k")
      (footprint "eagle-import:0603_WAVE")
      (libsource (lib "eagle-import") (part "RESISTOR0603"))
    )
    (comp (ref "R69")
      (value "100k")
      (footprint "eagle-import:0603_WAVE")
      (libsource (lib "eagle-import") (part "RESISTOR0603"))
    )
    (comp (ref "R70")
      (value "RESISTOR0603")
      (footprint "eagle-import:0603_WAVE")
      (libsource (lib "eagle-import") (part "RESISTOR0603"))
    )
    (comp (ref "R71")
      (value "RESISTOR0603")
      (footprint "eagle-import:0603_WAVE")
      (libsource (lib "eagle-import") (part "RESISTOR0603"))
    )
    (comp (ref "R72")
      (value "RESISTOR0603")
      (footprint "eagle-import:0603_WAVE")
      (libsource (lib "eagle-import") (part "RESISTOR0603"))
    )
    (comp (ref "R73")
      (value "100k")
      (footprint "eagle-import:0603_WAVE")
      (libsource (lib "eagle-import") (part "RESISTOR0603"))
    )
    (comp (ref "R74")
      (value "100k")
      (footprint "eagle-import:0603_WAVE")
      (libsource (lib "eagle-import") (part "RESISTOR0603"))
    )
    (comp (ref "R75")
      (value "100k")
      (footprint "eagle-import:0603_WAVE")
      (libsource (lib "eagle-import") (part "RESISTOR0603"))
    )
    (comp (ref "R84")
      (value "RESISTOR0603")
      (footprint "eagle-import:0603_WAVE")
      (libsource (lib "eagle-import") (part "RESISTOR0603"))
    )
    (comp (ref "R85")
      (value "RESISTOR0603")
      (footprint "eagle-import:0603_WAVE")
      (libsource (lib "eagle-import") (part "RESISTOR0603"))
    )
    (comp (ref "R86")
      (value "RESISTOR0603")
      (footprint "eagle-import:0603_WAVE")
      (libsource (lib "eagle-import") (part "RESISTOR0603"))
    )
    (comp (ref "U13")
      (value "74LVC3G17")
      (footprint "eagle-import:TSSOP-8")
      (libsource (lib "eagle-import") (part "74LVC3G17"))
    )
    (comp (ref "U14")
      (value "74LVC3G17")
      (footprint "eagle-import:TSSOP-8")
      (libsource (lib "eagle-import") (part "74LVC3G17"))
    )
    (comp (ref "U15")
      (value "74LVC3G17")
      (footprint "eagle-import:TSSOP-8")
      (libsource (lib "eagle-import") (part "74LVC3G17"))
    )
    (comp (ref "U16")
      (value "74LVC3G17")
      (footprint "eagle-import:TSSOP-8")
      (libsource (lib "eagle-import") (part "74LVC3G17"))
    )
    (comp (ref "U18")
      (value "SRV05-4")
      (footprint "eagle-import:SOT23-6")
      (libsource (lib "eagle-import") (part "SRV05-4"))
    )
    (comp (ref "U19")
      (value "SRV05-4")
      (footprint "eagle-import:SOT23-6")
      (libsource (lib "eagle-import") (part "SRV05-4"))
    )
    (comp (ref "U20")
      (value "SRV05-4")
      (footprint "eagle-import:SOT23-6")
      (libsource (lib "eagle-import") (part "SRV05-4"))
    )
    (comp (ref "U21")
      (value "SRV05-4")
      (footprint "eagle-import:SOT23-6")
      (libsource (lib "eagle-import") (part "SRV05-4"))
    )
    (comp (ref "C14")
      (value "4u7")
      (footprint "eagle-import:0603_WAVE")
      (libsource (lib "eagle-import") (part "MLCC0603"))
    )
    (comp (ref "C15")
      (value "4u7")
      (footprint "eagle-import:0603_WAVE")
      (libsource (lib "eagle-import") (part "MLCC0603"))
    )
    (comp (ref "C18")
      (value "100u")
      (footprint "eagle-import:PANASONIC_D")
      (libsource (lib "eagle-import") (part "CAPACITOR_ELD"))
    )
    (comp (ref "C20")
      (value "100u")
      (footprint "eagle-import:PANASONIC_D")
      (libsource (lib "eagle-import") (part "CAPACITOR_ELD"))
    )
    (comp (ref "C21")
      (value "4u7")
      (footprint "eagle-import:0603_WAVE")
      (libsource (lib "eagle-import") (part "MLCC0603"))
    )
    (comp (ref "C22")
      (value "330u")
      (footprint "eagle-import:PANASONIC_G")
      (libsource (lib "eagle-import") (part "CAPACITOR_ELG"))
    )
    (comp (ref "C23")
      (value "330u")
      (footprint "eagle-import:PANASONIC_G")
      (libsource (lib "eagle-import") (part "CAPACITOR_ELG"))
    )
    (comp (ref "C24")
      (value "330u")
      (footprint "eagle-import:PANASONIC_G")
      (libsource (lib "eagle-import") (part "CAPACITOR_ELG"))
    )
    (comp (ref "C25")
      (value "330u")
      (footprint "eagle-import:PANASONIC_G")
      (libsource (lib "eagle-import") (part "CAPACITOR_ELG"))
    )
    (comp (ref "C36")
      (value "4u7")
      (footprint "eagle-import:0603_WAVE")
      (libsource (lib "eagle-import") (part "MLCC0603"))
    )
    (comp (ref "D6")
      (value "SK54L")
      (footprint "eagle-import:DO214AA")
      (libsource (lib "eagle-import") (part "SK54L"))
    )
    (comp (ref "D17")
      (value "LED0603")
      (footprint "eagle-import:CHIPLED_0603")
      (libsource (lib "eagle-import") (part "LED0603"))
    )
    (comp (ref "D18")
      (value "LED0603")
      (footprint "eagle-import:CHIPLED_0603")
      (libsource (lib "eagle-import") (part "LED0603"))
    )
    (comp (ref "D19")
      (value "LED0603")
      (footprint "eagle-import:CHIPLED_0603")
      (libsource (lib "eagle-import") (part "LED0603"))
    )
    (comp (ref "J1")
      (value "2P-6.35P")
      (footprint "eagle-import:2P-6.35P")
      (libsource (lib "eagle-import") (part "2P-6.35P"))
    )
    (comp (ref "J2")
      (value "2P-6.35P")
      (footprint "eagle-import:2P-6.35P")
      (libsource (lib "eagle-import") (part "2P-6.35P"))
    )
    (comp (ref "L2")
      (value "68uH")
      (footprint "eagle-import:CDRH104R")
      (libsource (lib "eagle-import") (part "INDUCTORCDRH104R"))
    )
    (comp (ref "P5")
      (value "POWPAD")
      (footprint "eagle-import:TH-HP")
      (libsource (lib "eagle-import") (part "POWPAD"))
    )
    (comp (ref "P6")
      (value "POWPAD")
      (footprint "eagle-import:TH-HP")
      (libsource (lib "eagle-import") (part "POWPAD"))
    )
    (comp (ref "R55")
      (value "10M")
      (footprint "eagle-import:0603_WAVE")
      (libsource (lib "eagle-import") (part "RESISTOR0603"))
    )
    (comp (ref "R56")
      (value "10k")
      (footprint "eagle-import:0603_WAVE")
      (libsource (lib "eagle-import") (part "RESISTOR0603"))
    )
    (comp (ref "R58")
      (value "4.2k")
      (footprint "eagle-import:0603_WAVE")
      (libsource (lib "eagle-import") (part "RESISTOR0603"))
    )
    (comp (ref "R59")
      (value "1.2k")
      (footprint "eagle-import:0603_WAVE")
      (libsource (lib "eagle-import") (part "RESISTOR0603"))
    )
    (comp (ref "R93")
      (value "2k")
      (footprint "eagle-import:0603_WAVE")
      (libsource (lib "eagle-import") (part "RESISTOR0603"))
    )
    (comp (ref "R94")
      (value "1k")
      (footprint "eagle-import:0603_WAVE")
      (libsource (lib "eagle-import") (part "RESISTOR0603"))
    )
    (comp (ref "R95")
      (value "1k")
      (footprint "eagle-import:0603_WAVE")
      (libsource (lib "eagle-import") (part "RESISTOR0603"))
    )
    (comp (ref "U2")
      (value "MIC39101")
      (footprint "eagle-import:SOIC8")
      (libsource (lib "eagle-import") (part "MIC39101"))
    )
    (comp (ref "U3")
      (value "MIC39101")
      (footprint "eagle-import:SOIC8")
      (libsource (lib "eagle-import") (part "MIC39101"))
    )
    (comp (ref "U8")
      (value "MIC4682")
      (footprint "eagle-import:SOIC8")
      (libsource (lib "eagle-import") (part "MIC4682"))
    )
    (comp (ref "C1")
      (value "MLCC0603")
      (footprint "eagle-import:0603_WAVE")
      (libsource (lib "eagle-import") (part "MLCC0603"))
    )
    (comp (ref "C2")
      (value "MLCC0603")
      (footprint "eagle-import:0603_WAVE")
      (libsource (lib "eagle-import") (part "MLCC0603"))
    )
    (comp (ref "C3")
      (value "MLCC0603")
      (footprint "eagle-import:0603_WAVE")
      (libsource (lib "eagle-import") (part "MLCC0603"))
    )
    (comp (ref "C4")
      (value "MLCC0603")
      (footprint "eagle-import:0603_WAVE")
      (libsource (lib "eagle-import") (part "MLCC0603"))
    )
    (comp (ref "C5")
      (value "MLCC0603")
      (footprint "eagle-import:0603_WAVE")
      (libsource (lib "eagle-import") (part "MLCC0603"))
    )
    (comp (ref "C6")
      (value "MLCC0603")
      (footprint "eagle-import:0603_WAVE")
      (libsource (lib "eagle-import") (part "MLCC0603"))
    )
    (comp (ref "C7")
      (value "MLCC0603")
      (footprint "eagle-import:0603_WAVE")
      (libsource (lib "eagle-import") (part "MLCC0603"))
    )
    (comp (ref "C8")
      (value "MLCC0603")
      (footprint "eagle-import:0603_WAVE")
      (libsource (lib "eagle-import") (part "MLCC0603"))
    )
    (comp (ref "C9")
      (value "100n")
      (footprint "eagle-import:0603_WAVE")
      (libsource (lib "eagle-import") (part "MLCC0603"))
    )
    (comp (ref "C10")
      (value "100n")
      (footprint "eagle-import:0603_WAVE")
      (libsource (lib "eagle-import") (part "MLCC0603"))
    )
    (comp (ref "C11")
      (value "470n")
      (footprint "eagle-import:0603_WAVE")
      (libsource (lib "eagle-import") (part "MLCC0603"))
    )
    (comp (ref "C12")
      (value "4u7")
      (footprint "eagle-import:0603_WAVE")
      (libsource (lib "eagle-import") (part "MLCC0603"))
    )
    (comp (ref "C13")
      (value "MLCC0603")
      (footprint "eagle-import:0603_WAVE")
      (libsource (lib "eagle-import") (part "MLCC0603"))
    )
    (comp (ref "C31")
      (value "MLCC0603")
      (footprint "eagle-import:0603_WAVE")
      (libsource (lib "eagle-import") (part "MLCC0603"))
    )
    (comp (ref "C69")
      (value "100p")
      (footprint "eagle-import:0603_WAVE")
      (libsource (lib "eagle-import") (part "MLCC0603"))
    )
    (comp (ref "C70")
      (value "100p")
      (footprint "eagle-import:0603_WAVE")
      (libsource (lib "eagle-import") (part "MLCC0603"))
    )
    (comp (ref "C71")
      (value "10n")
      (footprint "eagle-import:0603_WAVE")
      (libsource (lib "eagle-import") (part "MLCC0603"))
    )
    (comp (ref "C102")
      (value "100p")
      (footprint "eagle-import:0603_WAVE")
      (libsource (lib "eagle-import") (part "MLCC0603"))
    )
    (comp (ref "C103")
      (value "100p")
      (footprint "eagle-import:0603_WAVE")
      (libsource (lib "eagle-import") (part "MLCC0603"))
    )
    (comp (ref "D8")
      (value "BAT54S")
      (footprint "eagle-import:SOT-23-3")
      (libsource (lib "eagle-import") (part "BAT54S"))
    )
    (comp (ref "R15")
      (value "10k")
      (footprint "eagle-import:0603_WAVE")
      (libsource (lib "eagle-import") (part "RESISTOR0603"))
    )
    (comp (ref "R16")
      (value "10k")
      (footprint "eagle-import:0603_WAVE")
      (libsource (lib "eagle-import") (part "RESISTOR0603"))
    )
    (comp (ref "R25")
      (value "RESISTOR0603")
      (footprint "eagle-import:0603_WAVE")
      (libsource (lib "eagle-import") (part "RESISTOR0603"))
    )
    (comp (ref "R26")
      (value "10k")
      (footprint "eagle-import:0603_WAVE")
      (libsource (lib "eagle-import") (part "RESISTOR0603"))
    )
    (comp (ref "R27")
      (value "RESISTOR0603")
      (footprint "eagle-import:0603_WAVE")
      (libsource (lib "eagle-import") (part "RESISTOR0603"))
    )
    (comp (ref "R32")
      (value "10k")
      (footprint "eagle-import:0603_WAVE")
      (libsource (lib "eagle-import") (part "RESISTOR0603"))
    )
    (comp (ref "R33")
      (value "10k")
      (footprint "eagle-import:0603_WAVE")
      (libsource (lib "eagle-import") (part "RESISTOR0603"))
    )
    (comp (ref "R34")
      (value "10k")
      (footprint "eagle-import:0603_WAVE")
      (libsource (lib "eagle-import") (part "RESISTOR0603"))
    )
    (comp (ref "R35")
      (value "10k")
      (footprint "eagle-import:0603_WAVE")
      (libsource (lib "eagle-import") (part "RESISTOR0603"))
    )
    (comp (ref "R36")
      (value "100")
      (footprint "eagle-import:0603_WAVE")
      (libsource (lib "eagle-import") (part "RESISTOR0603"))
    )
    (comp (ref "R37")
      (value "100")
      (footprint "eagle-import:0603_WAVE")
      (libsource (lib "eagle-import") (part "RESISTOR0603"))
    )
    (comp (ref "R38")
      (value "140k")
      (footprint "eagle-import:0603_WAVE")
      (libsource (lib "eagle-import") (part "RESISTOR0603"))
    )
    (comp (ref "R39")
      (value "10k")
      (footprint "eagle-import:0603_WAVE")
      (libsource (lib "eagle-import") (part "RESISTOR0603"))
    )
    (comp (ref "R76")
      (value "100")
      (footprint "eagle-import:0603_WAVE")
      (libsource (lib "eagle-import") (part "RESISTOR0603"))
    )
    (comp (ref "R77")
      (value "100")
      (footprint "eagle-import:0603_WAVE")
      (libsource (lib "eagle-import") (part "RESISTOR0603"))
    )
    (comp (ref "R78")
      (value "10k")
      (footprint "eagle-import:0603_WAVE")
      (libsource (lib "eagle-import") (part "RESISTOR0603"))
    )
    (comp (ref "R79")
      (value "10k")
      (footprint "eagle-import:0603_WAVE")
      (libsource (lib "eagle-import") (part "RESISTOR0603"))
    )
    (comp (ref "R80")
      (value "10k")
      (footprint "eagle-import:0603_WAVE")
      (libsource (lib "eagle-import") (part "RESISTOR0603"))
    )
    (comp (ref "R81")
      (value "10k")
      (footprint "eagle-import:0603_WAVE")
      (libsource (lib "eagle-import") (part "RESISTOR0603"))
    )
    (comp (ref "R82")
      (value "10k")
      (footprint "eagle-import:0603_WAVE")
      (libsource (lib "eagle-import") (part "RESISTOR0603"))
    )
    (comp (ref "R83")
      (value "10k")
      (footprint "eagle-import:0603_WAVE")
      (libsource (lib "eagle-import") (part "RESISTOR0603"))
    )
    (comp (ref "U$12")
      (value "MOUNTINGHOLE3.0")
      (footprint "eagle-import:MOUNTINGHOLE_3.0_PLATED")
      (libsource (lib "eagle-import") (part "MOUNTINGHOLE3.0"))
    )
    (comp (ref "U$13")
      (value "MOUNTINGHOLE3.0")
      (footprint "eagle-import:MOUNTINGHOLE_3.0_PLATED")
      (libsource (lib "eagle-import") (part "MOUNTINGHOLE3.0"))
    )
    (comp (ref "U$15")
      (value "MOUNTINGHOLE3.0")
      (footprint "eagle-import:MOUNTINGHOLE_3.0_PLATED")
      (libsource (lib "eagle-import") (part "MOUNTINGHOLE3.0"))
    )
    (comp (ref "U$16")
      (value "MOUNTINGHOLE3.0")
      (footprint "eagle-import:MOUNTINGHOLE_3.0_PLATED")
      (libsource (lib "eagle-import") (part "MOUNTINGHOLE3.0"))
    )
    (comp (ref "U1")
      (value "TMC4671")
      (footprint "eagle-import:QFN76")
      (libsource (lib "eagle-import") (part "TMC4671"))
    )
    (comp (ref "U12")
      (value "DSC1101")
      (footprint "eagle-import:CDFN_5X3.2")
      (libsource (lib "eagle-import") (part "DSC1101"))
    )
  )
  (nets
    (net (code "1") (name "1.8V") (class "Default")
      (node (ref "C1") (pin "P$1") (pinfunction "P$1_P$1") (pintype "bidirectional"))
      (node (ref "C2") (pin "P$1") (pinfunction "P$1_P$1") (pintype "bidirectional"))
      (node (ref "C3") (pin "P$1") (pinfunction "P$1_P$1") (pintype "bidirectional"))
      (node (ref "U1") (pin "15") (pinfunction "VCC_CORE_15") (pintype "bidirectional"))
      (node (ref "U1") (pin "45") (pinfunction "VCC_CORE_45") (pintype "bidirectional"))
      (node (ref "U1") (pin "63") (pinfunction "VCC_CORE_63") (pintype "bidirectional"))
    )
    (net (code "2") (name "3.3V") (class "Default")
      (node (ref "C10") (pin "P$1") (pinfunction "P$1_P$1") (pintype "bidirectional"))
      (node (ref "C101") (pin "P$1") (pinfunction "P$1_P$1") (pintype "bidirectional"))
      (node (ref "C11") (pin "P$1") (pinfunction "P$1_P$1") (pintype "bidirectional"))
      (node (ref "C13") (pin "P$1") (pinfunction "P$1_P$1") (pintype "bidirectional"))
      (node (ref "C14") (pin "P$1") (pinfunction "P$1_P$1") (pintype "bidirectional"))
      (node (ref "C28") (pin "P$1") (pinfunction "P$1_P$1") (pintype "bidirectional"))
      (node (ref "C29") (pin "P$1") (pinfunction "P$1_P$1") (pintype "bidirectional"))
      (node (ref "C30") (pin "P$1") (pinfunction "P$1_P$1") (pintype "bidirectional"))
      (node (ref "C31") (pin "P$1") (pinfunction "P$1_P$1") (pintype "bidirectional"))
      (node (ref "C4") (pin "P$1") (pinfunction "P$1_P$1") (pintype "bidirectional"))
      (node (ref "C40") (pin "P$1") (pinfunction "P$1_P$1") (pintype "bidirectional"))
      (node (ref "C45") (pin "P$1") (pinfunction "P$1_P$1") (pintype "bidirectional"))
      (node (ref "C47") (pin "P$1") (pinfunction "P$1_P$1") (pintype "bidirectional"))
      (node (ref "C5") (pin "P$1") (pinfunction "P$1_P$1") (pintype "bidirectional"))
      (node (ref "C52") (pin "P$1") (pinfunction "P$1_P$1") (pintype "bidirectional"))
      (node (ref "C54") (pin "P$1") (pinfunction "P$1_P$1") (pintype "bidirectional"))
      (node (ref "C59") (pin "P$1") (pinfunction "P$1_P$1") (pintype "bidirectional"))
      (node (ref "C6") (pin "P$1") (pinfunction "P$1_P$1") (pintype "bidirectional"))
      (node (ref "C61") (pin "P$1") (pinfunction "P$1_P$1") (pintype "bidirectional"))
      (node (ref "C66") (pin "P$1") (pinfunction "P$1_P$1") (pintype "bidirectional"))
      (node (ref "C7") (pin "P$1") (pinfunction "P$1_P$1") (pintype "bidirectional"))
      (node (ref "C8") (pin "P$1") (pinfunction "P$1_P$1") (pintype "bidirectional"))
      (node (ref "C92") (pin "P$1") (pinfunction "P$1_P$1") (pintype "bidirectional"))
      (node (ref "C94") (pin "P$1") (pinfunction "P$1_P$1") (pintype "bidirectional"))
      (node (ref "C95") (pin "P$1") (pinfunction "P$1_P$1") (pintype "bidirectional"))
      (node (ref "D15") (pin "P$2") (pinfunction "2_P$2") (pintype "bidirectional"))
      (node (ref "D16") (pin "P$2") (pinfunction "2_P$2") (pintype "bidirectional"))
      (node (ref "D9") (pin "P$2") (pinfunction "2_P$2") (pintype "bidirectional"))
      (node (ref "J14") (pin "1") (pinfunction "S_1") (pintype "passive"))
      (node (ref "R11") (pin "P$1") (pinfunction "P$1_P$1") (pintype "bidirectional"))
      (node (ref "R25") (pin "P$2") (pinfunction "P$2_P$2") (pintype "bidirectional"))
      (node (ref "R27") (pin "P$1") (pinfunction "P$1_P$1") (pintype "bidirectional"))
      (node (ref "R42") (pin "P$2") (pinfunction "P$2_P$2") (pintype "bidirectional"))
      (node (ref "R43") (pin "P$2") (pinfunction "P$2_P$2") (pintype "bidirectional"))
      (node (ref "U1") (pin "13") (pinfunction "VCC_13") (pintype "bidirectional"))
      (node (ref "U1") (pin "2") (pinfunction "VCC_2") (pintype "bidirectional"))
      (node (ref "U1") (pin "43") (pinfunction "VCC_43") (pintype "bidirectional"))
      (node (ref "U1") (pin "52") (pinfunction "PLL_VCC_52") (pintype "bidirectional"))
      (node (ref "U1") (pin "61") (pinfunction "VCC_61") (pintype "bidirectional"))
      (node (ref "U1") (pin "72") (pinfunction "VCC_72") (pintype "bidirectional"))
      (node (ref "U12") (pin "6") (pinfunction "VDD_6") (pintype "bidirectional"))
      (node (ref "U13") (pin "8") (pinfunction "VCC_8") (pintype "bidirectional"))
      (node (ref "U14") (pin "8") (pinfunction "VCC_8") (pintype "bidirectional"))
      (node (ref "U15") (pin "8") (pinfunction "VCC_8") (pintype "bidirectional"))
      (node (ref "U16") (pin "8") (pinfunction "VCC_8") (pintype "bidirectional"))
      (node (ref "U2") (pin "3") (pinfunction "VOUT_3") (pintype "bidirectional"))
      (node (ref "U4") (pin "3") (pinfunction "VDDI_3") (pintype "bidirectional"))
      (node (ref "U4") (pin "8") (pinfunction "VDDI_8") (pintype "bidirectional"))
      (node (ref "U5") (pin "3") (pinfunction "VDDI_3") (pintype "bidirectional"))
      (node (ref "U5") (pin "8") (pinfunction "VDDI_8") (pintype "bidirectional"))
      (node (ref "U6") (pin "3") (pinfunction "VDDI_3") (pintype "bidirectional"))
      (node (ref "U6") (pin "8") (pinfunction "VDDI_8") (pintype "bidirectional"))
      (node (ref "U7") (pin "3") (pinfunction "VDDI_3") (pintype "bidirectional"))
      (node (ref "U7") (pin "8") (pinfunction "VDDI_8") (pintype "bidirectional"))
      (node (ref "U9") (pin "5") (pinfunction "VIO_5") (pintype "bidirectional"))
      (node (ref "U9") (pin "6") (pinfunction "VDD_6") (pintype "bidirectional"))
      (node (ref "U9") (pin "7") (pinfunction "VREGIN_7") (pintype "bidirectional"))
    )
    (net (code "3") (name "5V") (class "Default")
      (node (ref "C100") (pin "P$1") (pinfunction "P$1_P$1") (pintype "bidirectional"))
      (node (ref "C107") (pin "P$1") (pinfunction "P$1_P$1") (pintype "bidirectional"))
      (node (ref "C12") (pin "P$1") (pinfunction "P$1_P$1") (pintype "bidirectional"))
      (node (ref "C15") (pin "P$1") (pinfunction "P$1_P$1") (pintype "bidirectional"))
      (node (ref "C67") (pin "P$1") (pinfunction "P$1_P$1") (pintype "bidirectional"))
      (node (ref "C68") (pin "P$1") (pinfunction "P$1_P$1") (pintype "bidirectional"))
      (node (ref "C81") (pin "P$1") (pinfunction "P$1_P$1") (pintype "bidirectional"))
      (node (ref "C85") (pin "P$1") (pinfunction "P$1_P$1") (pintype "bidirectional"))
      (node (ref "C89") (pin "P$1") (pinfunction "P$1_P$1") (pintype "bidirectional"))
      (node (ref "C9") (pin "P$1") (pinfunction "P$1_P$1") (pintype "bidirectional"))
      (node (ref "C90") (pin "P$1") (pinfunction "P$1_P$1") (pintype "bidirectional"))
      (node (ref "C91") (pin "P$1") (pinfunction "P$1_P$1") (pintype "bidirectional"))
      (node (ref "C93") (pin "P$1") (pinfunction "P$1_P$1") (pintype "bidirectional"))
      (node (ref "C99") (pin "P$1") (pinfunction "P$1_P$1") (pintype "bidirectional"))
      (node (ref "D12") (pin "P$2") (pinfunction "2_P$2") (pintype "bidirectional"))
      (node (ref "D13") (pin "P$2") (pinfunction "2_P$2") (pintype "bidirectional"))
      (node (ref "D14") (pin "P$2") (pinfunction "2_P$2") (pintype "bidirectional"))
      (node (ref "D8") (pin "P$2") (pinfunction "2_P$2") (pintype "bidirectional"))
      (node (ref "J10") (pin "1") (pinfunction "S_1") (pintype "passive"))
      (node (ref "J5") (pin "1") (pinfunction "S_1") (pintype "passive"))
      (node (ref "J6") (pin "1") (pinfunction "S_1") (pintype "passive"))
      (node (ref "J7") (pin "1") (pinfunction "S_1") (pintype "passive"))
      (node (ref "J8") (pin "1") (pinfunction "S_1") (pintype "passive"))
      (node (ref "J9") (pin "1") (pinfunction "S_1") (pintype "passive"))
      (node (ref "R32") (pin "P$2") (pinfunction "P$2_P$2") (pintype "bidirectional"))
      (node (ref "R34") (pin "P$2") (pinfunction "P$2_P$2") (pintype "bidirectional"))
      (node (ref "R47") (pin "P$2") (pinfunction "P$2_P$2") (pintype "bidirectional"))
      (node (ref "R61") (pin "P$1") (pinfunction "P$1_P$1") (pintype "bidirectional"))
      (node (ref "R62") (pin "P$1") (pinfunction "P$1_P$1") (pintype "bidirectional"))
      (node (ref "R63") (pin "P$1") (pinfunction "P$1_P$1") (pintype "bidirectional"))
      (node (ref "R64") (pin "P$1") (pinfunction "P$1_P$1") (pintype "bidirectional"))
      (node (ref "R65") (pin "P$1") (pinfunction "P$1_P$1") (pintype "bidirectional"))
      (node (ref "R66") (pin "P$1") (pinfunction "P$1_P$1") (pintype "bidirectional"))
      (node (ref "R67") (pin "P$1") (pinfunction "P$1_P$1") (pintype "bidirectional"))
      (node (ref "R68") (pin "P$1") (pinfunction "P$1_P$1") (pintype "bidirectional"))
      (node (ref "R69") (pin "P$1") (pinfunction "P$1_P$1") (pintype "bidirectional"))
      (node (ref "R73") (pin "P$1") (pinfunction "P$1_P$1") (pintype "bidirectional"))
      (node (ref "R74") (pin "P$1") (pinfunction "P$1_P$1") (pintype "bidirectional"))
      (node (ref "R75") (pin "P$1") (pinfunction "P$1_P$1") (pintype "bidirectional"))
      (node (ref "R78") (pin "P$2") (pinfunction "P$2_P$2") (pintype "bidirectional"))
      (node (ref "R80") (pin "P$2") (pinfunction "P$2_P$2") (pintype "bidirectional"))
      (node (ref "R82") (pin "P$2") (pinfunction "P$2_P$2") (pintype "bidirectional"))
      (node (ref "U1") (pin "23") (pinfunction "V5_23") (pintype "bidirectional"))
      (node (ref "U10") (pin "6") (pinfunction "P$1_6") (pintype "bidirectional"))
      (node (ref "U10") (pin "7") (pinfunction "P$1_7") (pintype "bidirectional"))
      (node (ref "U11") (pin "6") (pinfunction "P$1_6") (pintype "bidirectional"))
      (node (ref "U11") (pin "7") (pinfunction "P$1_7") (pintype "bidirectional"))
      (node (ref "U18") (pin "5") (pinfunction "VCC_5") (pintype "bidirectional"))
      (node (ref "U19") (pin "5") (pinfunction "VCC_5") (pintype "bidirectional"))
      (node (ref "U20") (pin "5") (pinfunction "VCC_5") (pintype "bidirectional"))
      (node (ref "U21") (pin "5") (pinfunction "VCC_5") (pintype "bidirectional"))
      (node (ref "U3") (pin "3") (pinfunction "VOUT_3") (pintype "bidirectional"))
    )
    (net (code "4") (name "12V") (class "Default")
      (node (ref "C19") (pin "P$1") (pinfunction "P$1_P$1") (pintype "bidirectional"))
      (node (ref "C20") (pin "+") (pinfunction "AN_+") (pintype "bidirectional"))
      (node (ref "C21") (pin "P$1") (pinfunction "P$1_P$1") (pintype "bidirectional"))
      (node (ref "C27") (pin "P$1") (pinfunction "P$1_P$1") (pintype "bidirectional"))
      (node (ref "C39") (pin "P$1") (pinfunction "P$1_P$1") (pintype "bidirectional"))
      (node (ref "C41") (pin "P$1") (pinfunction "P$1_P$1") (pintype "bidirectional"))
      (node (ref "C42") (pin "P$1") (pinfunction "P$1_P$1") (pintype "bidirectional"))
      (node (ref "C43") (pin "P$1") (pinfunction "P$1_P$1") (pintype "bidirectional"))
      (node (ref "C44") (pin "P$1") (pinfunction "P$1_P$1") (pintype "bidirectional"))
      (node (ref "C48") (pin "P$1") (pinfunction "P$1_P$1") (pintype "bidirectional"))
      (node (ref "C49") (pin "P$1") (pinfunction "P$1_P$1") (pintype "bidirectional"))
      (node (ref "C50") (pin "P$1") (pinfunction "P$1_P$1") (pintype "bidirectional"))
      (node (ref "C51") (pin "P$1") (pinfunction "P$1_P$1") (pintype "bidirectional"))
      (node (ref "C55") (pin "P$1") (pinfunction "P$1_P$1") (pintype "bidirectional"))
      (node (ref "C56") (pin "P$1") (pinfunction "P$1_P$1") (pintype "bidirectional"))
      (node (ref "C57") (pin "P$1") (pinfunction "P$1_P$1") (pintype "bidirectional"))
      (node (ref "C58") (pin "P$1") (pinfunction "P$1_P$1") (pintype "bidirectional"))
      (node (ref "C62") (pin "P$1") (pinfunction "P$1_P$1") (pintype "bidirectional"))
      (node (ref "C63") (pin "P$1") (pinfunction "P$1_P$1") (pintype "bidirectional"))
      (node (ref "C64") (pin "P$1") (pinfunction "P$1_P$1") (pintype "bidirectional"))
      (node (ref "D19") (pin "A") (pinfunction "AN_A") (pintype "bidirectional"))
      (node (ref "J1") (pin "1") (pinfunction "S_1") (pintype "passive"))
      (node (ref "R28") (pin "P$1") (pinfunction "P$1_P$1") (pintype "bidirectional"))
      (node (ref "R29") (pin "P$1") (pinfunction "P$1_P$1") (pintype "bidirectional"))
      (node (ref "R30") (pin "P$1") (pinfunction "P$1_P$1") (pintype "bidirectional"))
      (node (ref "R31") (pin "P$1") (pinfunction "P$1_P$1") (pintype "bidirectional"))
      (node (ref "R55") (pin "P$2") (pinfunction "P$2_P$2") (pintype "bidirectional"))
      (node (ref "U17") (pin "8") (pinfunction "VDD_8") (pintype "bidirectional"))
      (node (ref "U4") (pin "11") (pinfunction "VDDB_11") (pintype "bidirectional"))
      (node (ref "U5") (pin "11") (pinfunction "VDDB_11") (pintype "bidirectional"))
      (node (ref "U6") (pin "11") (pinfunction "VDDB_11") (pintype "bidirectional"))
      (node (ref "U7") (pin "11") (pinfunction "VDDB_11") (pintype "bidirectional"))
      (node (ref "U8") (pin "5") (pinfunction "IN_5") (pintype "bidirectional"))
    )
    (net (code "5") (name "ADC_I0_U_PF") (class "Default")
      (node (ref "R36") (pin "P$2") (pinfunction "P$2_P$2") (pintype "bidirectional"))
      (node (ref "U10") (pin "5") (pinfunction "O_5") (pintype "bidirectional"))
    )
    (net (code "6") (name "ADC_I1_V_PF") (class "Default")
      (node (ref "R37") (pin "P$2") (pinfunction "P$2_P$2") (pintype "bidirectional"))
      (node (ref "U11") (pin "5") (pinfunction "O_5") (pintype "bidirectional"))
    )
    (net (code "7") (name "ADC_T_MOSFETS") (class "Default")
      (node (ref "C77") (pin "P$1") (pinfunction "P$1_P$1") (pintype "bidirectional"))
      (node (ref "R45") (pin "P$2") (pinfunction "P$2_P$2") (pintype "bidirectional"))
      (node (ref "R47") (pin "P$1") (pinfunction "P$1_P$1") (pintype "bidirectional"))
      (node (ref "R76") (pin "P$2") (pinfunction "P$2_P$2") (pintype "bidirectional"))
    )
    (net (code "8") (name "ADC_T_MOTOR") (class "Default")
      (node (ref "C76") (pin "P$1") (pinfunction "P$1_P$1") (pintype "bidirectional"))
      (node (ref "J9") (pin "2") (pinfunction "S_2") (pintype "passive"))
      (node (ref "R46") (pin "P$2") (pinfunction "P$2_P$2") (pintype "bidirectional"))
      (node (ref "R77") (pin "P$1") (pinfunction "P$1_P$1") (pintype "bidirectional"))
    )
    (net (code "9") (name "AENC_UX_P") (class "Default")
      (node (ref "C104") (pin "P$1") (pinfunction "P$1_P$1") (pintype "bidirectional"))
      (node (ref "D12") (pin "P$3") (pinfunction "3_P$3") (pintype "bidirectional"))
      (node (ref "R84") (pin "P$2") (pinfunction "P$2_P$2") (pintype "bidirectional"))
      (node (ref "U1") (pin "25") (pinfunction "AENC_UX_POS_25") (pintype "bidirectional"))
    )
    (net (code "10") (name "AENC_VN_P") (class "Default")
      (node (ref "C105") (pin "P$1") (pinfunction "P$1_P$1") (pintype "bidirectional"))
      (node (ref "D13") (pin "P$3") (pinfunction "3_P$3") (pintype "bidirectional"))
      (node (ref "R85") (pin "P$2") (pinfunction "P$2_P$2") (pintype "bidirectional"))
      (node (ref "U1") (pin "27") (pinfunction "AENC_VN_POS_27") (pintype "bidirectional"))
    )
    (net (code "11") (name "AENC_WY_P") (class "Default")
      (node (ref "C106") (pin "P$1") (pinfunction "P$1_P$1") (pintype "bidirectional"))
      (node (ref "D14") (pin "P$3") (pinfunction "3_P$3") (pintype "bidirectional"))
      (node (ref "R86") (pin "P$2") (pinfunction "P$2_P$2") (pintype "bidirectional"))
      (node (ref "U1") (pin "29") (pinfunction "AENC_WY_POS_29") (pintype "bidirectional"))
    )
    (net (code "12") (name "BRAKE") (class "Default")
      (node (ref "R88") (pin "P$2") (pinfunction "P$2_P$2") (pintype "bidirectional"))
      (node (ref "U1") (pin "31") (pinfunction "BRAKE_31") (pintype "bidirectional"))
    )
    (net (code "13") (name "CP2102_RX") (class "Default")
      (node (ref "J15") (pin "2") (pinfunction "S_2") (pintype "passive"))
      (node (ref "JP2") (pin "2") (pinfunction "2_2") (pintype "passive"))
      (node (ref "U1") (pin "11") (pinfunction "TXD_SYNCO_11") (pintype "bidirectional"))
    )
    (net (code "14") (name "CP2102_TX") (class "Default")
      (node (ref "J15") (pin "1") (pinfunction "S_1") (pintype "passive"))
      (node (ref "JP6") (pin "2") (pinfunction "2_2") (pintype "passive"))
      (node (ref "U1") (pin "10") (pinfunction "RXD_SYNCI_10") (pintype "bidirectional"))
    )
    (net (code "15") (name "D+") (class "Default")
      (node (ref "D5") (pin "3") (pinfunction "3_3") (pintype "bidirectional"))
      (node (ref "U$10") (pin "D+") (pinfunction "D+_D+") (pintype "bidirectional"))
      (node (ref "U9") (pin "3") (pinfunction "D+_3") (pintype "bidirectional"))
    )
    (net (code "16") (name "D-") (class "Default")
      (node (ref "D5") (pin "2") (pinfunction "2_2") (pintype "bidirectional"))
      (node (ref "U$10") (pin "D-") (pinfunction "D-_D-") (pintype "bidirectional"))
      (node (ref "U9") (pin "4") (pinfunction "D-_4") (pintype "bidirectional"))
    )
    (net (code "17") (name "DBG_SPI_MISO") (class "Default")
      (node (ref "J14") (pin "9") (pinfunction "S_9") (pintype "passive"))
      (node (ref "U1") (pin "4") (pinfunction "GPIO6_4") (pintype "bidirectional"))
    )
    (net (code "18") (name "DBG_SPI_MOSI") (class "Default")
      (node (ref "J14") (pin "7") (pinfunction "S_7") (pintype "passive"))
      (node (ref "U1") (pin "1") (pinfunction "GPIO5_1") (pintype "bidirectional"))
    )
    (net (code "19") (name "DBG_SPI_NSCS") (class "Default")
      (node (ref "J14") (pin "3") (pinfunction "S_3") (pintype "passive"))
      (node (ref "U1") (pin "75") (pinfunction "GPIO3_75") (pintype "bidirectional"))
    )
    (net (code "20") (name "DBG_SPI_SCK") (class "Default")
      (node (ref "J14") (pin "5") (pinfunction "S_5") (pintype "passive"))
      (node (ref "U1") (pin "76") (pinfunction "GPIO4_76") (pintype "bidirectional"))
    )
    (net (code "21") (name "DBG_SPI_TRG") (class "Default")
      (node (ref "J14") (pin "4") (pinfunction "S_4") (pintype "passive"))
      (node (ref "U1") (pin "5") (pinfunction "GPIO7_5") (pintype "bidirectional"))
    )
    (net (code "22") (name "DCBUS") (class "Default")
      (node (ref "C22") (pin "+") (pinfunction "AN_+") (pintype "bidirectional"))
      (node (ref "C23") (pin "+") (pinfunction "AN_+") (pintype "bidirectional"))
      (node (ref "C24") (pin "+") (pinfunction "AN_+") (pintype "bidirectional"))
      (node (ref "C25") (pin "+") (pinfunction "AN_+") (pintype "bidirectional"))
      (node (ref "J2") (pin "1") (pinfunction "S_1") (pintype "passive"))
      (node (ref "J4") (pin "1") (pinfunction "S_1") (pintype "passive"))
      (node (ref "P6") (pin "H1") (pinfunction "S_H1") (pintype "passive"))
      (node (ref "P6") (pin "H10") (pinfunction "S_H10") (pintype "passive"))
      (node (ref "P6") (pin "H11") (pinfunction "S_H11") (pintype "passive"))
      (node (ref "P6") (pin "H12") (pinfunction "S_H12") (pintype "passive"))
      (node (ref "P6") (pin "H2") (pinfunction "S_H2") (pintype "passive"))
      (node (ref "P6") (pin "H3") (pinfunction "S_H3") (pintype "passive"))
      (node (ref "P6") (pin "H4") (pinfunction "S_H4") (pintype "passive"))
      (node (ref "P6") (pin "H5") (pinfunction "S_H5") (pintype "passive"))
      (node (ref "P6") (pin "H6") (pinfunction "S_H6") (pintype "passive"))
      (node (ref "P6") (pin "H7") (pinfunction "S_H7") (pintype "passive"))
      (node (ref "P6") (pin "H8") (pinfunction "S_H8") (pintype "passive"))
      (node (ref "P6") (pin "H9") (pinfunction "S_H9") (pintype "passive"))
      (node (ref "P6") (pin "PAD") (pinfunction "S_PAD") (pintype "passive"))
      (node (ref "P7") (pin "H1") (pinfunction "S_H1") (pintype "passive"))
      (node (ref "P7") (pin "H10") (pinfunction "S_H10") (pintype "passive"))
      (node (ref "P7") (pin "H11") (pinfunction "S_H11") (pintype "passive"))
      (node (ref "P7") (pin "H12") (pinfunction "S_H12") (pintype "passive"))
      (node (ref "P7") (pin "H2") (pinfunction "S_H2") (pintype "passive"))
      (node (ref "P7") (pin "H3") (pinfunction "S_H3") (pintype "passive"))
      (node (ref "P7") (pin "H4") (pinfunction "S_H4") (pintype "passive"))
      (node (ref "P7") (pin "H5") (pinfunction "S_H5") (pintype "passive"))
      (node (ref "P7") (pin "H6") (pinfunction "S_H6") (pintype "passive"))
      (node (ref "P7") (pin "H7") (pinfunction "S_H7") (pintype "passive"))
      (node (ref "P7") (pin "H8") (pinfunction "S_H8") (pintype "passive"))
      (node (ref "P7") (pin "H9") (pinfunction "S_H9") (pintype "passive"))
      (node (ref "P7") (pin "PAD") (pinfunction "S_PAD") (pintype "passive"))
      (node (ref "Q1") (pin "D1") (pinfunction "D1_D1") (pintype "bidirectional"))
      (node (ref "Q1") (pin "D2") (pinfunction "D1_D2") (pintype "bidirectional"))
      (node (ref "Q1") (pin "D3") (pinfunction "D1_D3") (pintype "bidirectional"))
      (node (ref "Q1") (pin "D4") (pinfunction "D1_D4") (pintype "bidirectional"))
      (node (ref "Q3") (pin "D1") (pinfunction "D1_D1") (pintype "bidirectional"))
      (node (ref "Q3") (pin "D2") (pinfunction "D1_D2") (pintype "bidirectional"))
      (node (ref "Q3") (pin "D3") (pinfunction "D1_D3") (pintype "bidirectional"))
      (node (ref "Q3") (pin "D4") (pinfunction "D1_D4") (pintype "bidirectional"))
      (node (ref "Q5") (pin "D1") (pinfunction "D1_D1") (pintype "bidirectional"))
      (node (ref "Q5") (pin "D2") (pinfunction "D1_D2") (pintype "bidirectional"))
      (node (ref "Q5") (pin "D3") (pinfunction "D1_D3") (pintype "bidirectional"))
      (node (ref "Q5") (pin "D4") (pinfunction "D1_D4") (pintype "bidirectional"))
      (node (ref "Q7") (pin "D1") (pinfunction "D1_D1") (pintype "bidirectional"))
      (node (ref "Q7") (pin "D2") (pinfunction "D1_D2") (pintype "bidirectional"))
      (node (ref "Q7") (pin "D3") (pinfunction "D1_D3") (pintype "bidirectional"))
      (node (ref "Q7") (pin "D4") (pinfunction "D1_D4") (pintype "bidirectional"))
      (node (ref "R38") (pin "P$2") (pinfunction "P$2_P$2") (pintype "bidirectional"))
    )
    (net (code "23") (name "DIR") (class "Default")
      (node (ref "D9") (pin "P$3") (pinfunction "3_P$3") (pintype "bidirectional"))
      (node (ref "R40") (pin "P$2") (pinfunction "P$2_P$2") (pintype "bidirectional"))
      (node (ref "R90") (pin "P$2") (pinfunction "P$2_P$2") (pintype "bidirectional"))
      (node (ref "U1") (pin "56") (pinfunction "DIR_56") (pintype "bidirectional"))
    )
    (net (code "24") (name "ENC2_A") (class "Default")
      (node (ref "U1") (pin "64") (pinfunction "ENC2_A_64") (pintype "bidirectional"))
      (node (ref "U14") (pin "7") (pinfunction "Y_7") (pintype "output"))
    )
    (net (code "25") (name "ENC2_B") (class "Default")
      (node (ref "U1") (pin "65") (pinfunction "ENC2_B_65") (pintype "bidirectional"))
      (node (ref "U14") (pin "5") (pinfunction "Y_5") (pintype "output"))
    )
    (net (code "26") (name "ENC2_N") (class "Default")
      (node (ref "U1") (pin "66") (pinfunction "ENC2_N_66") (pintype "bidirectional"))
      (node (ref "U14") (pin "2") (pinfunction "Y_2") (pintype "output"))
    )
    (net (code "27") (name "ENC_A") (class "Default")
      (node (ref "U1") (pin "35") (pinfunction "ENC_A_35") (pintype "bidirectional"))
      (node (ref "U13") (pin "7") (pinfunction "Y_7") (pintype "output"))
    )
    (net (code "28") (name "ENC_B") (class "Default")
      (node (ref "U1") (pin "34") (pinfunction "ENC_B_34") (pintype "bidirectional"))
      (node (ref "U13") (pin "5") (pinfunction "Y_5") (pintype "output"))
    )
    (net (code "29") (name "ENC_N") (class "Default")
      (node (ref "U1") (pin "33") (pinfunction "ENC_N_33") (pintype "bidirectional"))
      (node (ref "U13") (pin "2") (pinfunction "Y_2") (pintype "output"))
    )
    (net (code "30") (name "ENO") (class "Default")
      (node (ref "R26") (pin "P$1") (pinfunction "P$1_P$1") (pintype "bidirectional"))
      (node (ref "U1") (pin "32") (pinfunction "ENO_32") (pintype "bidirectional"))
      (node (ref "U4") (pin "5") (pinfunction "EN_5") (pintype "bidirectional"))
      (node (ref "U5") (pin "5") (pinfunction "EN_5") (pintype "bidirectional"))
      (node (ref "U6") (pin "5") (pinfunction "EN_5") (pintype "bidirectional"))
      (node (ref "U7") (pin "5") (pinfunction "EN_5") (pintype "bidirectional"))
    )
    (net (code "31") (name "GND") (class "Default")
      (node (ref "C1") (pin "P$2") (pinfunction "P$2_P$2") (pintype "bidirectional"))
      (node (ref "C10") (pin "P$2") (pinfunction "P$2_P$2") (pintype "bidirectional"))
      (node (ref "C100") (pin "P$2") (pinfunction "P$2_P$2") (pintype "bidirectional"))
      (node (ref "C101") (pin "P$2") (pinfunction "P$2_P$2") (pintype "bidirectional"))
      (node (ref "C102") (pin "P$2") (pinfunction "P$2_P$2") (pintype "bidirectional"))
      (node (ref "C103") (pin "P$2") (pinfunction "P$2_P$2") (pintype "bidirectional"))
      (node (ref "C104") (pin "P$2") (pinfunction "P$2_P$2") (pintype "bidirectional"))
      (node (ref "C105") (pin "P$2") (pinfunction "P$2_P$2") (pintype "bidirectional"))
      (node (ref "C106") (pin "P$2") (pinfunction "P$2_P$2") (pintype "bidirectional"))
      (node (ref "C107") (pin "P$2") (pinfunction "P$2_P$2") (pintype "bidirectional"))
      (node (ref "C11") (pin "P$2") (pinfunction "P$2_P$2") (pintype "bidirectional"))
      (node (ref "C12") (pin "P$2") (pinfunction "P$2_P$2") (pintype "bidirectional"))
      (node (ref "C13") (pin "P$2") (pinfunction "P$2_P$2") (pintype "bidirectional"))
      (node (ref "C14") (pin "P$2") (pinfunction "P$2_P$2") (pintype "bidirectional"))
      (node (ref "C15") (pin "P$2") (pinfunction "P$2_P$2") (pintype "bidirectional"))
      (node (ref "C17") (pin "P$1") (pinfunction "P$1_P$1") (pintype "bidirectional"))
      (node (ref "C18") (pin "-") (pinfunction "CA_-") (pintype "bidirectional"))
      (node (ref "C19") (pin "P$2") (pinfunction "P$2_P$2") (pintype "bidirectional"))
      (node (ref "C2") (pin "P$2") (pinfunction "P$2_P$2") (pintype "bidirectional"))
      (node (ref "C20") (pin "-") (pinfunction "CA_-") (pintype "bidirectional"))
      (node (ref "C21") (pin "P$2") (pinfunction "P$2_P$2") (pintype "bidirectional"))
      (node (ref "C22") (pin "-") (pinfunction "CA_-") (pintype "bidirectional"))
      (node (ref "C23") (pin "-") (pinfunction "CA_-") (pintype "bidirectional"))
      (node (ref "C24") (pin "-") (pinfunction "CA_-") (pintype "bidirectional"))
      (node (ref "C25") (pin "-") (pinfunction "CA_-") (pintype "bidirectional"))
      (node (ref "C26") (pin "P$2") (pinfunction "P$2_P$2") (pintype "bidirectional"))
      (node (ref "C27") (pin "P$2") (pinfunction "P$2_P$2") (pintype "bidirectional"))
      (node (ref "C28") (pin "P$2") (pinfunction "P$2_P$2") (pintype "bidirectional"))
      (node (ref "C29") (pin "P$2") (pinfunction "P$2_P$2") (pintype "bidirectional"))
      (node (ref "C3") (pin "P$2") (pinfunction "P$2_P$2") (pintype "bidirectional"))
      (node (ref "C30") (pin "P$2") (pinfunction "P$2_P$2") (pintype "bidirectional"))
      (node (ref "C31") (pin "P$2") (pinfunction "P$2_P$2") (pintype "bidirectional"))
      (node (ref "C32") (pin "P$2") (pinfunction "P$2_P$2") (pintype "bidirectional"))
      (node (ref "C36") (pin "P$2") (pinfunction "P$2_P$2") (pintype "bidirectional"))
      (node (ref "C39") (pin "P$2") (pinfunction "P$2_P$2") (pintype "bidirectional"))
      (node (ref "C4") (pin "P$2") (pinfunction "P$2_P$2") (pintype "bidirectional"))
      (node (ref "C40") (pin "P$2") (pinfunction "P$2_P$2") (pintype "bidirectional"))
      (node (ref "C41") (pin "P$2") (pinfunction "P$2_P$2") (pintype "bidirectional"))
      (node (ref "C42") (pin "P$2") (pinfunction "P$2_P$2") (pintype "bidirectional"))
      (node (ref "C43") (pin "P$2") (pinfunction "P$2_P$2") (pintype "bidirectional"))
      (node (ref "C44") (pin "P$2") (pinfunction "P$2_P$2") (pintype "bidirectional"))
      (node (ref "C45") (pin "P$2") (pinfunction "P$2_P$2") (pintype "bidirectional"))
      (node (ref "C46") (pin "P$1") (pinfunction "P$1_P$1") (pintype "bidirectional"))
      (node (ref "C47") (pin "P$2") (pinfunction "P$2_P$2") (pintype "bidirectional"))
      (node (ref "C48") (pin "P$2") (pinfunction "P$2_P$2") (pintype "bidirectional"))
      (node (ref "C49") (pin "P$2") (pinfunction "P$2_P$2") (pintype "bidirectional"))
      (node (ref "C5") (pin "P$2") (pinfunction "P$2_P$2") (pintype "bidirectional"))
      (node (ref "C50") (pin "P$2") (pinfunction "P$2_P$2") (pintype "bidirectional"))
      (node (ref "C51") (pin "P$2") (pinfunction "P$2_P$2") (pintype "bidirectional"))
      (node (ref "C52") (pin "P$2") (pinfunction "P$2_P$2") (pintype "bidirectional"))
      (node (ref "C53") (pin "P$2") (pinfunction "P$2_P$2") (pintype "bidirectional"))
      (node (ref "C54") (pin "P$2") (pinfunction "P$2_P$2") (pintype "bidirectional"))
      (node (ref "C55") (pin "P$2") (pinfunction "P$2_P$2") (pintype "bidirectional"))
      (node (ref "C56") (pin "P$2") (pinfunction "P$2_P$2") (pintype "bidirectional"))
      (node (ref "C57") (pin "P$2") (pinfunction "P$2_P$2") (pintype "bidirectional"))
      (node (ref "C58") (pin "P$2") (pinfunction "P$2_P$2") (pintype "bidirectional"))
      (node (ref "C59") (pin "P$2") (pinfunction "P$2_P$2") (pintype "bidirectional"))
      (node (ref "C6") (pin "P$2") (pinfunction "P$2_P$2") (pintype "bidirectional"))
      (node (ref "C61") (pin "P$2") (pinfunction "P$2_P$2") (pintype "bidirectional"))
      (node (ref "C62") (pin "P$2") (pinfunction "P$2_P$2") (pintype "bidirectional"))
      (node (ref "C63") (pin "P$2") (pinfunction "P$2_P$2") (pintype "bidirectional"))
      (node (ref "C64") (pin "P$2") (pinfunction "P$2_P$2") (pintype "bidirectional"))
      (node (ref "C66") (pin "P$2") (pinfunction "P$2_P$2") (pintype "bidirectional"))
      (node (ref "C67") (pin "P$2") (pinfunction "P$2_P$2") (pintype "bidirectional"))
      (node (ref "C68") (pin "P$2") (pinfunction "P$2_P$2") (pintype "bidirectional"))
      (node (ref "C69") (pin "P$2") (pinfunction "P$2_P$2") (pintype "bidirectional"))
      (node (ref "C7") (pin "P$2") (pinfunction "P$2_P$2") (pintype "bidirectional"))
      (node (ref "C70") (pin "P$2") (pinfunction "P$2_P$2") (pintype "bidirectional"))
      (node (ref "C71") (pin "P$2") (pinfunction "P$2_P$2") (pintype "bidirectional"))
      (node (ref "C76") (pin "P$2") (pinfunction "P$2_P$2") (pintype "bidirectional"))
      (node (ref "C77") (pin "P$2") (pinfunction "P$2_P$2") (pintype "bidirectional"))
      (node (ref "C78") (pin "P$2") (pinfunction "P$2_P$2") (pintype "bidirectional"))
      (node (ref "C79") (pin "P$2") (pinfunction "P$2_P$2") (pintype "bidirectional"))
      (node (ref "C8") (pin "P$2") (pinfunction "P$2_P$2") (pintype "bidirectional"))
      (node (ref "C80") (pin "P$2") (pinfunction "P$2_P$2") (pintype "bidirectional"))
      (node (ref "C81") (pin "P$2") (pinfunction "P$2_P$2") (pintype "bidirectional"))
      (node (ref "C82") (pin "P$2") (pinfunction "P$2_P$2") (pintype "bidirectional"))
      (node (ref "C83") (pin "P$2") (pinfunction "P$2_P$2") (pintype "bidirectional"))
      (node (ref "C84") (pin "P$2") (pinfunction "P$2_P$2") (pintype "bidirectional"))
      (node (ref "C85") (pin "P$2") (pinfunction "P$2_P$2") (pintype "bidirectional"))
      (node (ref "C86") (pin "P$2") (pinfunction "P$2_P$2") (pintype "bidirectional"))
      (node (ref "C87") (pin "P$2") (pinfunction "P$2_P$2") (pintype "bidirectional"))
      (node (ref "C88") (pin "P$2") (pinfunction "P$2_P$2") (pintype "bidirectional"))
      (node (ref "C89") (pin "P$2") (pinfunction "P$2_P$2") (pintype "bidirectional"))
      (node (ref "C9") (pin "P$2") (pinfunction "P$2_P$2") (pintype "bidirectional"))
      (node (ref "C90") (pin "P$2") (pinfunction "P$2_P$2") (pintype "bidirectional"))
      (node (ref "C91") (pin "P$2") (pinfunction "P$2_P$2") (pintype "bidirectional"))
      (node (ref "C92") (pin "P$2") (pinfunction "P$2_P$2") (pintype "bidirectional"))
      (node (ref "C93") (pin "P$2") (pinfunction "P$2_P$2") (pintype "bidirectional"))
      (node (ref "C94") (pin "P$2") (pinfunction "P$2_P$2") (pintype "bidirectional"))
      (node (ref "C95") (pin "P$2") (pinfunction "P$2_P$2") (pintype "bidirectional"))
      (node (ref "C96") (pin "P$2") (pinfunction "P$2_P$2") (pintype "bidirectional"))
      (node (ref "C97") (pin "P$2") (pinfunction "P$2_P$2") (pintype "bidirectional"))
      (node (ref "C98") (pin "P$2") (pinfunction "P$2_P$2") (pintype "bidirectional"))
      (node (ref "C99") (pin "P$2") (pinfunction "P$2_P$2") (pintype "bidirectional"))
      (node (ref "D12") (pin "P$1") (pinfunction "1_P$1") (pintype "bidirectional"))
      (node (ref "D13") (pin "P$1") (pinfunction "1_P$1") (pintype "bidirectional"))
      (node (ref "D14") (pin "P$1") (pinfunction "1_P$1") (pintype "bidirectional"))
      (node (ref "D15") (pin "P$1") (pinfunction "1_P$1") (pintype "bidirectional"))
      (node (ref "D16") (pin "P$1") (pinfunction "1_P$1") (pintype "bidirectional"))
      (node (ref "D17") (pin "C") (pinfunction "CA_C") (pintype "bidirectional"))
      (node (ref "D18") (pin "C") (pinfunction "CA_C") (pintype "bidirectional"))
      (node (ref "D5") (pin "1") (pinfunction "1_1") (pintype "bidirectional"))
      (node (ref "D6") (pin "A") (pinfunction "A_A") (pintype "bidirectional"))
      (node (ref "D8") (pin "P$1") (pinfunction "1_P$1") (pintype "bidirectional"))
      (node (ref "D9") (pin "P$1") (pinfunction "1_P$1") (pintype "bidirectional"))
      (node (ref "J1") (pin "2") (pinfunction "S_2") (pintype "passive"))
      (node (ref "J10") (pin "5") (pinfunction "S_5") (pintype "passive"))
      (node (ref "J10") (pin "FIT@1") (pinfunction "S_FIT@1") (pintype "passive"))
      (node (ref "J10") (pin "FIT@2") (pinfunction "S_FIT@2") (pintype "passive"))
      (node (ref "J12") (pin "3") (pinfunction "S_3") (pintype "passive"))
      (node (ref "J12") (pin "FIT@1") (pinfunction "S_FIT@1") (pintype "passive"))
      (node (ref "J12") (pin "FIT@2") (pinfunction "S_FIT@2") (pintype "passive"))
      (node (ref "J13") (pin "2") (pinfunction "S_2") (pintype "passive"))
      (node (ref "J13") (pin "FIT@1") (pinfunction "S_FIT@1") (pintype "passive"))
      (node (ref "J13") (pin "FIT@2") (pinfunction "S_FIT@2") (pintype "passive"))
      (node (ref "J14") (pin "10") (pinfunction "S_10") (pintype "passive"))
      (node (ref "J14") (pin "6") (pinfunction "S_6") (pintype "passive"))
      (node (ref "J14") (pin "8") (pinfunction "S_8") (pintype "passive"))
      (node (ref "J14") (pin "TAB1") (pinfunction "S_TAB1") (pintype "passive"))
      (node (ref "J14") (pin "TAB2") (pinfunction "S_TAB2") (pintype "passive"))
      (node (ref "J15") (pin "3") (pinfunction "S_3") (pintype "passive"))
      (node (ref "J15") (pin "FIT@1") (pinfunction "S_FIT@1") (pintype "passive"))
      (node (ref "J15") (pin "FIT@2") (pinfunction "S_FIT@2") (pintype "passive"))
      (node (ref "J16") (pin "6") (pinfunction "S_6") (pintype "passive"))
      (node (ref "J16") (pin "FIT@1") (pinfunction "S_FIT@1") (pintype "passive"))
      (node (ref "J16") (pin "FIT@2") (pinfunction "S_FIT@2") (pintype "passive"))
      (node (ref "J2") (pin "2") (pinfunction "S_2") (pintype "passive"))
      (node (ref "J5") (pin "5") (pinfunction "S_5") (pintype "passive"))
      (node (ref "J5") (pin "FIT@1") (pinfunction "S_FIT@1") (pintype "passive"))
      (node (ref "J5") (pin "FIT@2") (pinfunction "S_FIT@2") (pintype "passive"))
      (node (ref "J6") (pin "5") (pinfunction "S_5") (pintype "passive"))
      (node (ref "J6") (pin "FIT@1") (pinfunction "S_FIT@1") (pintype "passive"))
      (node (ref "J6") (pin "FIT@2") (pinfunction "S_FIT@2") (pintype "passive"))
      (node (ref "J7") (pin "5") (pinfunction "S_5") (pintype "passive"))
      (node (ref "J7") (pin "FIT@1") (pinfunction "S_FIT@1") (pintype "passive"))
      (node (ref "J7") (pin "FIT@2") (pinfunction "S_FIT@2") (pintype "passive"))
      (node (ref "J8") (pin "5") (pinfunction "S_5") (pintype "passive"))
      (node (ref "J8") (pin "FIT@1") (pinfunction "S_FIT@1") (pintype "passive"))
      (node (ref "J8") (pin "FIT@2") (pinfunction "S_FIT@2") (pintype "passive"))
      (node (ref "J9") (pin "FIT@1") (pinfunction "S_FIT@1") (pintype "passive"))
      (node (ref "J9") (pin "FIT@2") (pinfunction "S_FIT@2") (pintype "passive"))
      (node (ref "P5") (pin "H1") (pinfunction "S_H1") (pintype "passive"))
      (node (ref "P5") (pin "H10") (pinfunction "S_H10") (pintype "passive"))
      (node (ref "P5") (pin "H11") (pinfunction "S_H11") (pintype "passive"))
      (node (ref "P5") (pin "H12") (pinfunction "S_H12") (pintype "passive"))
      (node (ref "P5") (pin "H2") (pinfunction "S_H2") (pintype "passive"))
      (node (ref "P5") (pin "H3") (pinfunction "S_H3") (pintype "passive"))
      (node (ref "P5") (pin "H4") (pinfunction "S_H4") (pintype "passive"))
      (node (ref "P5") (pin "H5") (pinfunction "S_H5") (pintype "passive"))
      (node (ref "P5") (pin "H6") (pinfunction "S_H6") (pintype "passive"))
      (node (ref "P5") (pin "H7") (pinfunction "S_H7") (pintype "passive"))
      (node (ref "P5") (pin "H8") (pinfunction "S_H8") (pintype "passive"))
      (node (ref "P5") (pin "H9") (pinfunction "S_H9") (pintype "passive"))
      (node (ref "P5") (pin "PAD") (pinfunction "S_PAD") (pintype "passive"))
      (node (ref "Q2") (pin "S1") (pinfunction "S1_S1") (pintype "bidirectional"))
      (node (ref "Q2") (pin "S2") (pinfunction "S1_S2") (pintype "bidirectional"))
      (node (ref "Q2") (pin "S3") (pinfunction "S1_S3") (pintype "bidirectional"))
      (node (ref "Q2") (pin "S4") (pinfunction "S1_S4") (pintype "bidirectional"))
      (node (ref "Q2") (pin "S5") (pinfunction "S1_S5") (pintype "bidirectional"))
      (node (ref "Q4") (pin "S1") (pinfunction "S1_S1") (pintype "bidirectional"))
      (node (ref "Q4") (pin "S2") (pinfunction "S1_S2") (pintype "bidirectional"))
      (node (ref "Q4") (pin "S3") (pinfunction "S1_S3") (pintype "bidirectional"))
      (node (ref "Q4") (pin "S4") (pinfunction "S1_S4") (pintype "bidirectional"))
      (node (ref "Q4") (pin "S5") (pinfunction "S1_S5") (pintype "bidirectional"))
      (node (ref "Q6") (pin "S1") (pinfunction "S1_S1") (pintype "bidirectional"))
      (node (ref "Q6") (pin "S2") (pinfunction "S1_S2") (pintype "bidirectional"))
      (node (ref "Q6") (pin "S3") (pinfunction "S1_S3") (pintype "bidirectional"))
      (node (ref "Q6") (pin "S4") (pinfunction "S1_S4") (pintype "bidirectional"))
      (node (ref "Q6") (pin "S5") (pinfunction "S1_S5") (pintype "bidirectional"))
      (node (ref "Q8") (pin "S1") (pinfunction "S1_S1") (pintype "bidirectional"))
      (node (ref "Q8") (pin "S2") (pinfunction "S1_S2") (pintype "bidirectional"))
      (node (ref "Q8") (pin "S3") (pinfunction "S1_S3") (pintype "bidirectional"))
      (node (ref "Q8") (pin "S4") (pinfunction "S1_S4") (pintype "bidirectional"))
      (node (ref "Q8") (pin "S5") (pinfunction "S1_S5") (pintype "bidirectional"))
      (node (ref "Q9") (pin "S1") (pinfunction "S1_S1") (pintype "bidirectional"))
      (node (ref "Q9") (pin "S2") (pinfunction "S1_S2") (pintype "bidirectional"))
      (node (ref "Q9") (pin "S3") (pinfunction "S1_S3") (pintype "bidirectional"))
      (node (ref "Q9") (pin "S4") (pinfunction "S1_S4") (pintype "bidirectional"))
      (node (ref "Q9") (pin "S5") (pinfunction "S1_S5") (pintype "bidirectional"))
      (node (ref "R13") (pin "P$2") (pinfunction "P$2_P$2") (pintype "bidirectional"))
      (node (ref "R15") (pin "P$1") (pinfunction "P$1_P$1") (pintype "bidirectional"))
      (node (ref "R16") (pin "P$1") (pinfunction "P$1_P$1") (pintype "bidirectional"))
      (node (ref "R17") (pin "P$1") (pinfunction "P$1_P$1") (pintype "bidirectional"))
      (node (ref "R18") (pin "P$1") (pinfunction "P$1_P$1") (pintype "bidirectional"))
      (node (ref "R19") (pin "P$1") (pinfunction "P$1_P$1") (pintype "bidirectional"))
      (node (ref "R20") (pin "P$1") (pinfunction "P$1_P$1") (pintype "bidirectional"))
      (node (ref "R21") (pin "P$1") (pinfunction "P$1_P$1") (pintype "bidirectional"))
      (node (ref "R22") (pin "P$1") (pinfunction "P$1_P$1") (pintype "bidirectional"))
      (node (ref "R23") (pin "P$1") (pinfunction "P$1_P$1") (pintype "bidirectional"))
      (node (ref "R24") (pin "P$1") (pinfunction "P$1_P$1") (pintype "bidirectional"))
      (node (ref "R26") (pin "P$2") (pinfunction "P$2_P$2") (pintype "bidirectional"))
      (node (ref "R33") (pin "P$1") (pinfunction "P$1_P$1") (pintype "bidirectional"))
      (node (ref "R35") (pin "P$1") (pinfunction "P$1_P$1") (pintype "bidirectional"))
      (node (ref "R39") (pin "P$1") (pinfunction "P$1_P$1") (pintype "bidirectional"))
      (node (ref "R45") (pin "P$1") (pinfunction "P$1_P$1") (pintype "bidirectional"))
      (node (ref "R46") (pin "P$1") (pinfunction "P$1_P$1") (pintype "bidirectional"))
      (node (ref "R56") (pin "P$1") (pinfunction "P$1_P$1") (pintype "bidirectional"))
      (node (ref "R59") (pin "P$1") (pinfunction "P$1_P$1") (pintype "bidirectional"))
      (node (ref "R79") (pin "P$1") (pinfunction "P$1_P$1") (pintype "bidirectional"))
      (node (ref "R81") (pin "P$1") (pinfunction "P$1_P$1") (pintype "bidirectional"))
      (node (ref "R83") (pin "P$1") (pinfunction "P$1_P$1") (pintype "bidirectional"))
      (node (ref "R89") (pin "P$1") (pinfunction "P$1_P$1") (pintype "bidirectional"))
      (node (ref "R90") (pin "P$1") (pinfunction "P$1_P$1") (pintype "bidirectional"))
      (node (ref "R92") (pin "P$1") (pinfunction "P$1_P$1") (pintype "bidirectional"))
      (node (ref "R93") (pin "P$1") (pinfunction "P$1_P$1") (pintype "bidirectional"))
      (node (ref "U$10") (pin "GND") (pinfunction "GND_GND") (pintype "bidirectional"))
      (node (ref "U$10") (pin "GND@1") (pinfunction "CASE_GND@1") (pintype "bidirectional"))
      (node (ref "U$10") (pin "GND@2") (pinfunction "CASE_GND@2") (pintype "bidirectional"))
      (node (ref "U$10") (pin "GND@3") (pinfunction "CASE_GND@3") (pintype "bidirectional"))
      (node (ref "U$10") (pin "GND@4") (pinfunction "CASE_GND@4") (pintype "bidirectional"))
      (node (ref "U1") (pin "14") (pinfunction "GND_14") (pintype "bidirectional"))
      (node (ref "U1") (pin "24") (pinfunction "GNDA_24") (pintype "bidirectional"))
      (node (ref "U1") (pin "3") (pinfunction "GND_3") (pintype "bidirectional"))
      (node (ref "U1") (pin "44") (pinfunction "GND_44") (pintype "bidirectional"))
      (node (ref "U1") (pin "53") (pinfunction "PLL_GND_53") (pintype "bidirectional"))
      (node (ref "U1") (pin "54") (pinfunction "TEST_54") (pintype "bidirectional"))
      (node (ref "U1") (pin "62") (pinfunction "GND_62") (pintype "bidirectional"))
      (node (ref "U1") (pin "73") (pinfunction "GND_73") (pintype "bidirectional"))
      (node (ref "U1") (pin "PAD") (pinfunction "GNDP_PAD") (pintype "bidirectional"))
      (node (ref "U10") (pin "2") (pinfunction "P$1_2") (pintype "bidirectional"))
      (node (ref "U10") (pin "3") (pinfunction "P$1_3") (pintype "bidirectional"))
      (node (ref "U11") (pin "2") (pinfunction "P$1_2") (pintype "bidirectional"))
      (node (ref "U11") (pin "3") (pinfunction "P$1_3") (pintype "bidirectional"))
      (node (ref "U12") (pin "3") (pinfunction "GND_3") (pintype "bidirectional"))
      (node (ref "U13") (pin "4") (pinfunction "GND_4") (pintype "bidirectional"))
      (node (ref "U14") (pin "4") (pinfunction "GND_4") (pintype "bidirectional"))
      (node (ref "U15") (pin "4") (pinfunction "GND_4") (pintype "bidirectional"))
      (node (ref "U16") (pin "4") (pinfunction "GND_4") (pintype "bidirectional"))
      (node (ref "U17") (pin "3") (pinfunction "CA_3") (pintype "bidirectional"))
      (node (ref "U17") (pin "5") (pinfunction "GNB_5") (pintype "bidirectional"))
      (node (ref "U18") (pin "2") (pinfunction "GND_2") (pintype "bidirectional"))
      (node (ref "U19") (pin "2") (pinfunction "GND_2") (pintype "bidirectional"))
      (node (ref "U2") (pin "5") (pinfunction "GND_5") (pintype "bidirectional"))
      (node (ref "U2") (pin "6") (pinfunction "GND_6") (pintype "bidirectional"))
      (node (ref "U2") (pin "7") (pinfunction "GND_7") (pintype "bidirectional"))
      (node (ref "U2") (pin "8") (pinfunction "GND_8") (pintype "bidirectional"))
      (node (ref "U20") (pin "2") (pinfunction "GND_2") (pintype "bidirectional"))
      (node (ref "U21") (pin "2") (pinfunction "GND_2") (pintype "bidirectional"))
      (node (ref "U3") (pin "5") (pinfunction "GND_5") (pintype "bidirectional"))
      (node (ref "U3") (pin "6") (pinfunction "GND_6") (pintype "bidirectional"))
      (node (ref "U3") (pin "7") (pinfunction "GND_7") (pintype "bidirectional"))
      (node (ref "U3") (pin "8") (pinfunction "GND_8") (pintype "bidirectional"))
      (node (ref "U4") (pin "4") (pinfunction "GNDI_4") (pintype "bidirectional"))
      (node (ref "U4") (pin "9") (pinfunction "GNB_9") (pintype "bidirectional"))
      (node (ref "U5") (pin "4") (pinfunction "GNDI_4") (pintype "bidirectional"))
      (node (ref "U5") (pin "9") (pinfunction "GNB_9") (pintype "bidirectional"))
      (node (ref "U6") (pin "4") (pinfunction "GNDI_4") (pintype "bidirectional"))
      (node (ref "U6") (pin "9") (pinfunction "GNB_9") (pintype "bidirectional"))
      (node (ref "U7") (pin "4") (pinfunction "GNDI_4") (pintype "bidirectional"))
      (node (ref "U7") (pin "9") (pinfunction "GNB_9") (pintype "bidirectional"))
      (node (ref "U8") (pin "2") (pinfunction "GND_2") (pintype "bidirectional"))
      (node (ref "U8") (pin "4") (pinfunction "SHDN_4") (pintype "bidirectional"))
      (node (ref "U8") (pin "6") (pinfunction "GND_6") (pintype "bidirectional"))
      (node (ref "U8") (pin "7") (pinfunction "GND_7") (pintype "bidirectional"))
      (node (ref "U9") (pin "2") (pinfunction "GND_2") (pintype "bidirectional"))
      (node (ref "U9") (pin "PAD") (pinfunction "GNDP_PAD") (pintype "bidirectional"))
    )
    (net (code "32") (name "GPIO0") (class "Default")
      (node (ref "U1") (pin "70") (pinfunction "GPIO0_70") (pintype "bidirectional"))
    )
    (net (code "33") (name "GPIO1") (class "Default")
      (node (ref "U1") (pin "71") (pinfunction "GPIO1_71") (pintype "bidirectional"))
    )
    (net (code "34") (name "GPIO2") (class "Default")
      (node (ref "U1") (pin "74") (pinfunction "GPIO2_74") (pintype "bidirectional"))
    )
    (net (code "35") (name "HALL_UX") (class "Default")
      (node (ref "U1") (pin "38") (pinfunction "HALL_UX_38") (pintype "bidirectional"))
      (node (ref "U15") (pin "2") (pinfunction "Y_2") (pintype "output"))
    )
    (net (code "36") (name "HALL_V") (class "Default")
      (node (ref "U1") (pin "37") (pinfunction "HALL_V_37") (pintype "bidirectional"))
      (node (ref "U15") (pin "5") (pinfunction "Y_5") (pintype "output"))
    )
    (net (code "37") (name "HALL_WY") (class "Default")
      (node (ref "U1") (pin "36") (pinfunction "HALL_WY_36") (pintype "bidirectional"))
      (node (ref "U15") (pin "7") (pinfunction "Y_7") (pintype "output"))
    )
    (net (code "38") (name "INT") (class "Default")
      (node (ref "J16") (pin "5") (pinfunction "S_5") (pintype "passive"))
      (node (ref "U1") (pin "12") (pinfunction "STATUS_12") (pintype "bidirectional"))
    )
    (net (code "39") (name "MISO") (class "Default")
      (node (ref "J16") (pin "4") (pinfunction "S_4") (pintype "passive"))
      (node (ref "JP3") (pin "2") (pinfunction "2_2") (pintype "passive"))
      (node (ref "U1") (pin "9") (pinfunction "SPI_MISO_9") (pintype "bidirectional"))
    )
    (net (code "40") (name "MOSI") (class "Default")
      (node (ref "J16") (pin "3") (pinfunction "S_3") (pintype "passive"))
      (node (ref "JP4") (pin "2") (pinfunction "2_2") (pintype "passive"))
      (node (ref "U1") (pin "8") (pinfunction "SPI_MOSI_8") (pintype "bidirectional"))
    )
    (net (code "41") (name "N$107") (class "Default")
      (node (ref "JP1") (pin "2") (pinfunction "2_2") (pintype "passive"))
    )
    (net (code "42") (name "Net-(C18-AN)") (class "Default")
      (node (ref "C18") (pin "+") (pinfunction "AN_+") (pintype "bidirectional"))
      (node (ref "C36") (pin "P$1") (pinfunction "P$1_P$1") (pintype "bidirectional"))
      (node (ref "L2") (pin "2") (pinfunction "P$2_2") (pintype "bidirectional"))
      (node (ref "R58") (pin "P$2") (pinfunction "P$2_P$2") (pintype "bidirectional"))
      (node (ref "R94") (pin "P$2") (pinfunction "P$2_P$2") (pintype "bidirectional"))
      (node (ref "R95") (pin "P$2") (pinfunction "P$2_P$2") (pintype "bidirectional"))
      (node (ref "U2") (pin "1") (pinfunction "EN_1") (pintype "bidirectional"))
      (node (ref "U2") (pin "2") (pinfunction "VIN_2") (pintype "bidirectional"))
      (node (ref "U3") (pin "1") (pinfunction "EN_1") (pintype "bidirectional"))
      (node (ref "U3") (pin "2") (pinfunction "VIN_2") (pintype "bidirectional"))
    )
    (net (code "43") (name "Net-(D1-PadA)") (class "Default")
      (node (ref "D1") (pin "A") (pinfunction "A_A") (pintype "passive"))
      (node (ref "R28") (pin "P$2") (pinfunction "P$2_P$2") (pintype "bidirectional"))
    )
    (net (code "44") (name "Net-(D2-PadA)") (class "Default")
      (node (ref "D2") (pin "A") (pinfunction "A_A") (pintype "passive"))
      (node (ref "R29") (pin "P$2") (pinfunction "P$2_P$2") (pintype "bidirectional"))
    )
    (net (code "45") (name "Net-(D3-PadA)") (class "Default")
      (node (ref "D3") (pin "A") (pinfunction "A_A") (pintype "passive"))
      (node (ref "R30") (pin "P$2") (pinfunction "P$2_P$2") (pintype "bidirectional"))
    )
    (net (code "46") (name "Net-(D4-PadA)") (class "Default")
      (node (ref "D4") (pin "A") (pinfunction "A_A") (pintype "passive"))
      (node (ref "R31") (pin "P$2") (pinfunction "P$2_P$2") (pintype "bidirectional"))
    )
    (net (code "47") (name "Net-(D5-Pad4)") (class "Default")
      (node (ref "D5") (pin "4") (pinfunction "4_4") (pintype "bidirectional"))
      (node (ref "R12") (pin "P$1") (pinfunction "P$1_P$1") (pintype "bidirectional"))
      (node (ref "U$10") (pin "VBUS") (pinfunction "VBUS_VBUS") (pintype "bidirectional"))
    )
    (net (code "48") (name "Net-(D8-3)") (class "Default")
      (node (ref "C71") (pin "P$1") (pinfunction "P$1_P$1") (pintype "bidirectional"))
      (node (ref "D8") (pin "P$3") (pinfunction "3_P$3") (pintype "bidirectional"))
      (node (ref "R38") (pin "P$1") (pinfunction "P$1_P$1") (pintype "bidirectional"))
      (node (ref "R39") (pin "P$2") (pinfunction "P$2_P$2") (pintype "bidirectional"))
      (node (ref "U1") (pin "20") (pinfunction "ADC_VM_20") (pintype "bidirectional"))
    )
    (net (code "49") (name "Net-(D10-AN)") (class "Default")
      (node (ref "D10") (pin "A") (pinfunction "AN_A") (pintype "bidirectional"))
      (node (ref "R43") (pin "P$1") (pinfunction "P$1_P$1") (pintype "bidirectional"))
    )
    (net (code "50") (name "Net-(D10-CA)") (class "Default")
      (node (ref "D10") (pin "C") (pinfunction "CA_C") (pintype "bidirectional"))
      (node (ref "U9") (pin "13") (pinfunction "(GPIO1-RXT)GPIO8-~{CS8}-SPIACT_13") (pintype "bidirectional"))
    )
    (net (code "51") (name "Net-(D11-AN)") (class "Default")
      (node (ref "D11") (pin "A") (pinfunction "AN_A") (pintype "bidirectional"))
      (node (ref "R42") (pin "P$1") (pinfunction "P$1_P$1") (pintype "bidirectional"))
    )
    (net (code "52") (name "Net-(D11-CA)") (class "Default")
      (node (ref "D11") (pin "C") (pinfunction "CA_C") (pintype "bidirectional"))
      (node (ref "U9") (pin "14") (pinfunction "(GPIO0-TXT)GPIO7-~{CS7}_14") (pintype "bidirectional"))
    )
    (net (code "53") (name "Net-(D17-AN)") (class "Default")
      (node (ref "D17") (pin "A") (pinfunction "AN_A") (pintype "bidirectional"))
      (node (ref "R94") (pin "P$1") (pinfunction "P$1_P$1") (pintype "bidirectional"))
      (node (ref "U2") (pin "4") (pinfunction "FLG_4") (pintype "bidirectional"))
    )
    (net (code "54") (name "Net-(D18-AN)") (class "Default")
      (node (ref "D18") (pin "A") (pinfunction "AN_A") (pintype "bidirectional"))
      (node (ref "R95") (pin "P$1") (pinfunction "P$1_P$1") (pintype "bidirectional"))
      (node (ref "U3") (pin "4") (pinfunction "FLG_4") (pintype "bidirectional"))
    )
    (net (code "55") (name "Net-(D19-CA)") (class "Default")
      (node (ref "D19") (pin "C") (pinfunction "CA_C") (pintype "bidirectional"))
      (node (ref "R93") (pin "P$2") (pinfunction "P$2_P$2") (pintype "bidirectional"))
    )
    (net (code "56") (name "Net-(J3A-S)") (class "Default")
      (node (ref "J3") (pin "1") (pinfunction "S_1") (pintype "passive"))
      (node (ref "P1") (pin "H1") (pinfunction "S_H1") (pintype "passive"))
      (node (ref "P1") (pin "H10") (pinfunction "S_H10") (pintype "passive"))
      (node (ref "P1") (pin "H11") (pinfunction "S_H11") (pintype "passive"))
      (node (ref "P1") (pin "H12") (pinfunction "S_H12") (pintype "passive"))
      (node (ref "P1") (pin "H2") (pinfunction "S_H2") (pintype "passive"))
      (node (ref "P1") (pin "H3") (pinfunction "S_H3") (pintype "passive"))
      (node (ref "P1") (pin "H4") (pinfunction "S_H4") (pintype "passive"))
      (node (ref "P1") (pin "H5") (pinfunction "S_H5") (pintype "passive"))
      (node (ref "P1") (pin "H6") (pinfunction "S_H6") (pintype "passive"))
      (node (ref "P1") (pin "H7") (pinfunction "S_H7") (pintype "passive"))
      (node (ref "P1") (pin "H8") (pinfunction "S_H8") (pintype "passive"))
      (node (ref "P1") (pin "H9") (pinfunction "S_H9") (pintype "passive"))
      (node (ref "P1") (pin "PAD") (pinfunction "S_PAD") (pintype "passive"))
      (node (ref "R9") (pin "3") (pinfunction "P$2_3") (pintype "bidirectional"))
      (node (ref "R9") (pin "4") (pinfunction "P$2_4") (pintype "bidirectional"))
    )
    (net (code "57") (name "Net-(J3B-S)") (class "Default")
      (node (ref "J3") (pin "2") (pinfunction "S_2") (pintype "passive"))
      (node (ref "P2") (pin "H1") (pinfunction "S_H1") (pintype "passive"))
      (node (ref "P2") (pin "H10") (pinfunction "S_H10") (pintype "passive"))
      (node (ref "P2") (pin "H11") (pinfunction "S_H11") (pintype "passive"))
      (node (ref "P2") (pin "H12") (pinfunction "S_H12") (pintype "passive"))
      (node (ref "P2") (pin "H2") (pinfunction "S_H2") (pintype "passive"))
      (node (ref "P2") (pin "H3") (pinfunction "S_H3") (pintype "passive"))
      (node (ref "P2") (pin "H4") (pinfunction "S_H4") (pintype "passive"))
      (node (ref "P2") (pin "H5") (pinfunction "S_H5") (pintype "passive"))
      (node (ref "P2") (pin "H6") (pinfunction "S_H6") (pintype "passive"))
      (node (ref "P2") (pin "H7") (pinfunction "S_H7") (pintype "passive"))
      (node (ref "P2") (pin "H8") (pinfunction "S_H8") (pintype "passive"))
      (node (ref "P2") (pin "H9") (pinfunction "S_H9") (pintype "passive"))
      (node (ref "P2") (pin "PAD") (pinfunction "S_PAD") (pintype "passive"))
      (node (ref "R10") (pin "3") (pinfunction "P$2_3") (pintype "bidirectional"))
      (node (ref "R10") (pin "4") (pinfunction "P$2_4") (pintype "bidirectional"))
    )
    (net (code "58") (name "Net-(J4B-S)") (class "Default")
      (node (ref "J4") (pin "2") (pinfunction "S_2") (pintype "passive"))
      (node (ref "P8") (pin "H1") (pinfunction "S_H1") (pintype "passive"))
      (node (ref "P8") (pin "H10") (pinfunction "S_H10") (pintype "passive"))
      (node (ref "P8") (pin "H11") (pinfunction "S_H11") (pintype "passive"))
      (node (ref "P8") (pin "H12") (pinfunction "S_H12") (pintype "passive"))
      (node (ref "P8") (pin "H2") (pinfunction "S_H2") (pintype "passive"))
      (node (ref "P8") (pin "H3") (pinfunction "S_H3") (pintype "passive"))
      (node (ref "P8") (pin "H4") (pinfunction "S_H4") (pintype "passive"))
      (node (ref "P8") (pin "H5") (pinfunction "S_H5") (pintype "passive"))
      (node (ref "P8") (pin "H6") (pinfunction "S_H6") (pintype "passive"))
      (node (ref "P8") (pin "H7") (pinfunction "S_H7") (pintype "passive"))
      (node (ref "P8") (pin "H8") (pinfunction "S_H8") (pintype "passive"))
      (node (ref "P8") (pin "H9") (pinfunction "S_H9") (pintype "passive"))
      (node (ref "P8") (pin "PAD") (pinfunction "S_PAD") (pintype "passive"))
      (node (ref "Q9") (pin "D1") (pinfunction "D1_D1") (pintype "bidirectional"))
      (node (ref "Q9") (pin "D2") (pinfunction "D1_D2") (pintype "bidirectional"))
      (node (ref "Q9") (pin "D3") (pinfunction "D1_D3") (pintype "bidirectional"))
      (node (ref "Q9") (pin "D4") (pinfunction "D1_D4") (pintype "bidirectional"))
    )
    (net (code "59") (name "Net-(J5B-S)") (class "Default")
      (node (ref "J5") (pin "2") (pinfunction "S_2") (pintype "passive"))
      (node (ref "R48") (pin "P$1") (pinfunction "P$1_P$1") (pintype "bidirectional"))
    )
    (net (code "60") (name "Net-(J5C-S)") (class "Default")
      (node (ref "J5") (pin "3") (pinfunction "S_3") (pintype "passive"))
      (node (ref "R49") (pin "P$1") (pinfunction "P$1_P$1") (pintype "bidirectional"))
    )
    (net (code "61") (name "Net-(J5D-S)") (class "Default")
      (node (ref "J5") (pin "4") (pinfunction "S_4") (pintype "passive"))
      (node (ref "R50") (pin "P$1") (pinfunction "P$1_P$1") (pintype "bidirectional"))
    )
    (net (code "62") (name "Net-(J6B-S)") (class "Default")
      (node (ref "J6") (pin "2") (pinfunction "S_2") (pintype "passive"))
      (node (ref "R51") (pin "P$1") (pinfunction "P$1_P$1") (pintype "bidirectional"))
    )
    (net (code "63") (name "Net-(J6C-S)") (class "Default")
      (node (ref "J6") (pin "3") (pinfunction "S_3") (pintype "passive"))
      (node (ref "R52") (pin "P$1") (pinfunction "P$1_P$1") (pintype "bidirectional"))
    )
    (net (code "64") (name "Net-(J6D-S)") (class "Default")
      (node (ref "J6") (pin "4") (pinfunction "S_4") (pintype "passive"))
      (node (ref "R53") (pin "P$1") (pinfunction "P$1_P$1") (pintype "bidirectional"))
    )
    (net (code "65") (name "Net-(J7B-S)") (class "Default")
      (node (ref "J7") (pin "2") (pinfunction "S_2") (pintype "passive"))
      (node (ref "R54") (pin "P$1") (pinfunction "P$1_P$1") (pintype "bidirectional"))
    )
    (net (code "66") (name "Net-(J7C-S)") (class "Default")
      (node (ref "J7") (pin "3") (pinfunction "S_3") (pintype "passive"))
      (node (ref "R57") (pin "P$1") (pinfunction "P$1_P$1") (pintype "bidirectional"))
    )
    (net (code "67") (name "Net-(J7D-S)") (class "Default")
      (node (ref "J7") (pin "4") (pinfunction "S_4") (pintype "passive"))
      (node (ref "R60") (pin "P$1") (pinfunction "P$1_P$1") (pintype "bidirectional"))
    )
    (net (code "68") (name "Net-(J8B-S)") (class "Default")
      (node (ref "J8") (pin "2") (pinfunction "S_2") (pintype "passive"))
      (node (ref "R70") (pin "P$1") (pinfunction "P$1_P$1") (pintype "bidirectional"))
    )
    (net (code "69") (name "Net-(J8C-S)") (class "Default")
      (node (ref "J8") (pin "3") (pinfunction "S_3") (pintype "passive"))
      (node (ref "R71") (pin "P$1") (pinfunction "P$1_P$1") (pintype "bidirectional"))
    )
    (net (code "70") (name "Net-(J8D-S)") (class "Default")
      (node (ref "J8") (pin "4") (pinfunction "S_4") (pintype "passive"))
      (node (ref "R72") (pin "P$1") (pinfunction "P$1_P$1") (pintype "bidirectional"))
    )
    (net (code "71") (name "Net-(J10B-S)") (class "Default")
      (node (ref "J10") (pin "2") (pinfunction "S_2") (pintype "passive"))
      (node (ref "R84") (pin "P$1") (pinfunction "P$1_P$1") (pintype "bidirectional"))
    )
    (net (code "72") (name "Net-(J10C-S)") (class "Default")
      (node (ref "J10") (pin "3") (pinfunction "S_3") (pintype "passive"))
      (node (ref "R85") (pin "P$1") (pinfunction "P$1_P$1") (pintype "bidirectional"))
    )
    (net (code "73") (name "Net-(J10D-S)") (class "Default")
      (node (ref "J10") (pin "4") (pinfunction "S_4") (pintype "passive"))
      (node (ref "R86") (pin "P$1") (pinfunction "P$1_P$1") (pintype "bidirectional"))
    )
    (net (code "74") (name "Net-(J12A-S)") (class "Default")
      (node (ref "J12") (pin "1") (pinfunction "S_1") (pintype "passive"))
      (node (ref "R40") (pin "P$1") (pinfunction "P$1_P$1") (pintype "bidirectional"))
    )
    (net (code "75") (name "Net-(J12B-S)") (class "Default")
      (node (ref "J12") (pin "2") (pinfunction "S_2") (pintype "passive"))
      (node (ref "R41") (pin "P$1") (pinfunction "P$1_P$1") (pintype "bidirectional"))
    )
    (net (code "76") (name "Net-(J13A-S)") (class "Default")
      (node (ref "J13") (pin "1") (pinfunction "S_1") (pintype "passive"))
      (node (ref "R91") (pin "P$1") (pinfunction "P$1_P$1") (pintype "bidirectional"))
    )
    (net (code "77") (name "Net-(L2-P$1)") (class "Default")
      (node (ref "D6") (pin "C") (pinfunction "C_C") (pintype "bidirectional"))
      (node (ref "L2") (pin "1") (pinfunction "P$1_1") (pintype "bidirectional"))
      (node (ref "U8") (pin "8") (pinfunction "SW_8") (pintype "bidirectional"))
    )
    (net (code "78") (name "Net-(Q1-G1)") (class "Default")
      (node (ref "Q1") (pin "G") (pinfunction "G1_G") (pintype "bidirectional"))
      (node (ref "R1") (pin "P$2") (pinfunction "P$2_P$2") (pintype "bidirectional"))
    )
    (net (code "79") (name "Net-(Q2-G1)") (class "Default")
      (node (ref "Q2") (pin "G") (pinfunction "G1_G") (pintype "bidirectional"))
      (node (ref "R2") (pin "P$2") (pinfunction "P$2_P$2") (pintype "bidirectional"))
    )
    (net (code "80") (name "Net-(Q3-G1)") (class "Default")
      (node (ref "Q3") (pin "G") (pinfunction "G1_G") (pintype "bidirectional"))
      (node (ref "R3") (pin "P$2") (pinfunction "P$2_P$2") (pintype "bidirectional"))
    )
    (net (code "81") (name "Net-(Q4-G1)") (class "Default")
      (node (ref "Q4") (pin "G") (pinfunction "G1_G") (pintype "bidirectional"))
      (node (ref "R4") (pin "P$2") (pinfunction "P$2_P$2") (pintype "bidirectional"))
    )
    (net (code "82") (name "Net-(Q5-G1)") (class "Default")
      (node (ref "Q5") (pin "G") (pinfunction "G1_G") (pintype "bidirectional"))
      (node (ref "R5") (pin "P$2") (pinfunction "P$2_P$2") (pintype "bidirectional"))
    )
    (net (code "83") (name "Net-(Q6-G1)") (class "Default")
      (node (ref "Q6") (pin "G") (pinfunction "G1_G") (pintype "bidirectional"))
      (node (ref "R6") (pin "P$2") (pinfunction "P$2_P$2") (pintype "bidirectional"))
    )
    (net (code "84") (name "Net-(Q7-G1)") (class "Default")
      (node (ref "Q7") (pin "G") (pinfunction "G1_G") (pintype "bidirectional"))
      (node (ref "R7") (pin "P$2") (pinfunction "P$2_P$2") (pintype "bidirectional"))
    )
    (net (code "85") (name "Net-(Q8-G1)") (class "Default")
      (node (ref "Q8") (pin "G") (pinfunction "G1_G") (pintype "bidirectional"))
      (node (ref "R8") (pin "P$2") (pinfunction "P$2_P$2") (pintype "bidirectional"))
    )
    (net (code "86") (name "Net-(Q9-G1)") (class "Default")
      (node (ref "Q9") (pin "G") (pinfunction "G1_G") (pintype "bidirectional"))
      (node (ref "R87") (pin "P$2") (pinfunction "P$2_P$2") (pintype "bidirectional"))
    )
    (net (code "87") (name "Net-(R9-PadSENSE+)") (class "Default")
      (node (ref "R9") (pin "SENSE+") (pinfunction "SENSE+_SENSE+") (pintype "bidirectional"))
      (node (ref "R97") (pin "P$1") (pinfunction "P$1_P$1") (pintype "bidirectional"))
    )
    (net (code "88") (name "Net-(R9-PadSENSE-)") (class "Default")
      (node (ref "R9") (pin "SENSE-") (pinfunction "SENSE-_SENSE-") (pintype "bidirectional"))
      (node (ref "R96") (pin "P$1") (pinfunction "P$1_P$1") (pintype "bidirectional"))
    )
    (net (code "89") (name "Net-(R10-PadSENSE+)") (class "Default")
      (node (ref "R10") (pin "SENSE+") (pinfunction "SENSE+_SENSE+") (pintype "bidirectional"))
      (node (ref "R99") (pin "P$1") (pinfunction "P$1_P$1") (pintype "bidirectional"))
    )
    (net (code "90") (name "Net-(R10-PadSENSE-)") (class "Default")
      (node (ref "R10") (pin "SENSE-") (pinfunction "SENSE-_SENSE-") (pintype "bidirectional"))
      (node (ref "R98") (pin "P$1") (pinfunction "P$1_P$1") (pintype "bidirectional"))
    )
    (net (code "91") (name "Net-(R87-PadP$1)") (class "Default")
      (node (ref "R87") (pin "P$1") (pinfunction "P$1_P$1") (pintype "bidirectional"))
      (node (ref "U17") (pin "6") (pinfunction "VO_6") (pintype "bidirectional"))
      (node (ref "U17") (pin "7") (pinfunction "VO_7") (pintype "bidirectional"))
    )
    (net (code "92") (name "Net-(U1A-AGPI_A)") (class "Default")
      (node (ref "C102") (pin "P$1") (pinfunction "P$1_P$1") (pintype "bidirectional"))
      (node (ref "R76") (pin "P$1") (pinfunction "P$1_P$1") (pintype "bidirectional"))
      (node (ref "U1") (pin "21") (pinfunction "AGPI_A_21") (pintype "bidirectional"))
    )
    (net (code "93") (name "Net-(U1A-AGPI_B)") (class "Default")
      (node (ref "C103") (pin "P$1") (pinfunction "P$1_P$1") (pintype "bidirectional"))
      (node (ref "R77") (pin "P$2") (pinfunction "P$2_P$2") (pintype "bidirectional"))
      (node (ref "U1") (pin "22") (pinfunction "AGPI_B_22") (pintype "bidirectional"))
    )
    (net (code "94") (name "Net-(U1B-~{RST})") (class "Default")
      (node (ref "R27") (pin "P$2") (pinfunction "P$2_P$2") (pintype "bidirectional"))
      (node (ref "U1") (pin "50") (pinfunction "~{RST}_50") (pintype "bidirectional"))
    )
    (net (code "95") (name "Net-(U1D-ADC_I0_NEG)") (class "Default")
      (node (ref "R32") (pin "P$1") (pinfunction "P$1_P$1") (pintype "bidirectional"))
      (node (ref "R33") (pin "P$2") (pinfunction "P$2_P$2") (pintype "bidirectional"))
      (node (ref "U1") (pin "17") (pinfunction "ADC_I0_NEG_17") (pintype "bidirectional"))
    )
    (net (code "96") (name "Net-(U1D-ADC_I0_POS)") (class "Default")
      (node (ref "C69") (pin "P$1") (pinfunction "P$1_P$1") (pintype "bidirectional"))
      (node (ref "R36") (pin "P$1") (pinfunction "P$1_P$1") (pintype "bidirectional"))
      (node (ref "U1") (pin "16") (pinfunction "ADC_I0_POS_16") (pintype "bidirectional"))
    )
    (net (code "97") (name "Net-(U1D-ADC_I1_NEG)") (class "Default")
      (node (ref "R34") (pin "P$1") (pinfunction "P$1_P$1") (pintype "bidirectional"))
      (node (ref "R35") (pin "P$2") (pinfunction "P$2_P$2") (pintype "bidirectional"))
      (node (ref "U1") (pin "19") (pinfunction "ADC_I1_NEG_19") (pintype "bidirectional"))
    )
    (net (code "98") (name "Net-(U1D-ADC_I1_POS)") (class "Default")
      (node (ref "C70") (pin "P$1") (pinfunction "P$1_P$1") (pintype "bidirectional"))
      (node (ref "R37") (pin "P$1") (pinfunction "P$1_P$1") (pintype "bidirectional"))
      (node (ref "U1") (pin "18") (pinfunction "ADC_I1_POS_18") (pintype "bidirectional"))
    )
    (net (code "99") (name "Net-(U1D-AENC_UX_NEG)") (class "Default")
      (node (ref "R82") (pin "P$1") (pinfunction "P$1_P$1") (pintype "bidirectional"))
      (node (ref "R83") (pin "P$2") (pinfunction "P$2_P$2") (pintype "bidirectional"))
      (node (ref "U1") (pin "26") (pinfunction "AENC_UX_NEG_26") (pintype "bidirectional"))
    )
    (net (code "100") (name "Net-(U1D-AENC_VN_NEG)") (class "Default")
      (node (ref "R80") (pin "P$1") (pinfunction "P$1_P$1") (pintype "bidirectional"))
      (node (ref "R81") (pin "P$2") (pinfunction "P$2_P$2") (pintype "bidirectional"))
      (node (ref "U1") (pin "28") (pinfunction "AENC_VN_NEG_28") (pintype "bidirectional"))
    )
    (net (code "101") (name "Net-(U1D-AENC_WY_NEG)") (class "Default")
      (node (ref "R78") (pin "P$1") (pinfunction "P$1_P$1") (pintype "bidirectional"))
      (node (ref "R79") (pin "P$2") (pinfunction "P$2_P$2") (pintype "bidirectional"))
      (node (ref "U1") (pin "30") (pinfunction "AENC_WY_NEG_30") (pintype "bidirectional"))
    )
    (net (code "102") (name "Net-(U1D-PWM_IDLE_H)") (class "Default")
      (node (ref "R16") (pin "P$2") (pinfunction "P$2_P$2") (pintype "bidirectional"))
      (node (ref "U1") (pin "59") (pinfunction "PWM_IDLE_H_59") (pintype "bidirectional"))
    )
    (net (code "103") (name "Net-(U1D-PWM_IDLE_L)") (class "Default")
      (node (ref "R15") (pin "P$2") (pinfunction "P$2_P$2") (pintype "bidirectional"))
      (node (ref "U1") (pin "60") (pinfunction "PWM_IDLE_L_60") (pintype "bidirectional"))
    )
    (net (code "104") (name "Net-(U4-VDDA)") (class "Default")
      (node (ref "C34") (pin "P$1") (pinfunction "P$1_P$1") (pintype "bidirectional"))
      (node (ref "D1") (pin "C") (pinfunction "C_C") (pintype "passive"))
      (node (ref "U4") (pin "16") (pinfunction "VDDA_16") (pintype "bidirectional"))
    )
    (net (code "105") (name "Net-(U4-VOA)") (class "Default")
      (node (ref "R1") (pin "P$1") (pinfunction "P$1_P$1") (pintype "bidirectional"))
      (node (ref "U4") (pin "15") (pinfunction "VOA_15") (pintype "bidirectional"))
    )
    (net (code "106") (name "Net-(U4-VOB)") (class "Default")
      (node (ref "R2") (pin "P$1") (pinfunction "P$1_P$1") (pintype "bidirectional"))
      (node (ref "U4") (pin "10") (pinfunction "VOB_10") (pintype "bidirectional"))
    )
    (net (code "107") (name "Net-(U5-VDDA)") (class "Default")
      (node (ref "C35") (pin "P$1") (pinfunction "P$1_P$1") (pintype "bidirectional"))
      (node (ref "D2") (pin "C") (pinfunction "C_C") (pintype "passive"))
      (node (ref "U5") (pin "16") (pinfunction "VDDA_16") (pintype "bidirectional"))
    )
    (net (code "108") (name "Net-(U5-VOA)") (class "Default")
      (node (ref "R3") (pin "P$1") (pinfunction "P$1_P$1") (pintype "bidirectional"))
      (node (ref "U5") (pin "15") (pinfunction "VOA_15") (pintype "bidirectional"))
    )
    (net (code "109") (name "Net-(U5-VOB)") (class "Default")
      (node (ref "R4") (pin "P$1") (pinfunction "P$1_P$1") (pintype "bidirectional"))
      (node (ref "U5") (pin "10") (pinfunction "VOB_10") (pintype "bidirectional"))
    )
    (net (code "110") (name "Net-(U6-VDDA)") (class "Default")
      (node (ref "C37") (pin "P$1") (pinfunction "P$1_P$1") (pintype "bidirectional"))
      (node (ref "D3") (pin "C") (pinfunction "C_C") (pintype "passive"))
      (node (ref "U6") (pin "16") (pinfunction "VDDA_16") (pintype "bidirectional"))
    )
    (net (code "111") (name "Net-(U6-VOA)") (class "Default")
      (node (ref "R5") (pin "P$1") (pinfunction "P$1_P$1") (pintype "bidirectional"))
      (node (ref "U6") (pin "15") (pinfunction "VOA_15") (pintype "bidirectional"))
    )
    (net (code "112") (name "Net-(U6-VOB)") (class "Default")
      (node (ref "R6") (pin "P$1") (pinfunction "P$1_P$1") (pintype "bidirectional"))
      (node (ref "U6") (pin "10") (pinfunction "VOB_10") (pintype "bidirectional"))
    )
    (net (code "113") (name "Net-(U7-VDDA)") (class "Default")
      (node (ref "C38") (pin "P$1") (pinfunction "P$1_P$1") (pintype "bidirectional"))
      (node (ref "D4") (pin "C") (pinfunction "C_C") (pintype "passive"))
      (node (ref "U7") (pin "16") (pinfunction "VDDA_16") (pintype "bidirectional"))
    )
    (net (code "114") (name "Net-(U7-VOA)") (class "Default")
      (node (ref "R7") (pin "P$1") (pinfunction "P$1_P$1") (pintype "bidirectional"))
      (node (ref "U7") (pin "15") (pinfunction "VOA_15") (pintype "bidirectional"))
    )
    (net (code "115") (name "Net-(U7-VOB)") (class "Default")
      (node (ref "R8") (pin "P$1") (pinfunction "P$1_P$1") (pintype "bidirectional"))
      (node (ref "U7") (pin "10") (pinfunction "VOB_10") (pintype "bidirectional"))
    )
    (net (code "116") (name "Net-(U8-FB)") (class "Default")
      (node (ref "R58") (pin "P$1") (pinfunction "P$1_P$1") (pintype "bidirectional"))
      (node (ref "R59") (pin "P$2") (pinfunction "P$2_P$2") (pintype "bidirectional"))
      (node (ref "U8") (pin "1") (pinfunction "FB_1") (pintype "bidirectional"))
    )
    (net (code "117") (name "Net-(U8-ISET)") (class "Default")
      (node (ref "R55") (pin "P$1") (pinfunction "P$1_P$1") (pintype "bidirectional"))
      (node (ref "R56") (pin "P$2") (pinfunction "P$2_P$2") (pintype "bidirectional"))
      (node (ref "U8") (pin "3") (pinfunction "ISET_3") (pintype "bidirectional"))
    )
    (net (code "118") (name "Net-(U9-(CTS)GPIO4-~{CS4}-EVTCNTR)") (class "Default")
      (node (ref "JP1") (pin "1") (pinfunction "1_1") (pintype "passive"))
      (node (ref "U9") (pin "18") (pinfunction "(CTS)GPIO4-~{CS4}-EVTCNTR_18") (pintype "bidirectional"))
    )
    (net (code "119") (name "Net-(U9-(DCD)MISO)") (class "Default")
      (node (ref "JP3") (pin "1") (pinfunction "1_1") (pintype "passive"))
      (node (ref "U9") (pin "24") (pinfunction "(DCD)MISO_24") (pintype "bidirectional"))
    )
    (net (code "120") (name "Net-(U9-(DSR)GPIO0-~{CS0})") (class "Default")
      (node (ref "JP7") (pin "1") (pinfunction "1_1") (pintype "passive"))
      (node (ref "U9") (pin "22") (pinfunction "(DSR)GPIO0-~{CS0}_22") (pintype "bidirectional"))
    )
    (net (code "121") (name "Net-(U9-(DTR)MOSI)") (class "Default")
      (node (ref "JP4") (pin "1") (pinfunction "1_1") (pintype "passive"))
      (node (ref "U9") (pin "23") (pinfunction "(DTR)MOSI_23") (pintype "bidirectional"))
    )
    (net (code "122") (name "Net-(U9-(RI{slash}CLK)SCK)") (class "Default")
      (node (ref "JP5") (pin "1") (pinfunction "1_1") (pintype "passive"))
      (node (ref "U9") (pin "1") (pinfunction "(RI/CLK)SCK_1") (pintype "bidirectional"))
    )
    (net (code "123") (name "Net-(U9-(RXD)GPIO2-~{CS2})") (class "Default")
      (node (ref "JP6") (pin "1") (pinfunction "1_1") (pintype "passive"))
      (node (ref "U9") (pin "20") (pinfunction "(RXD)GPIO2-~{CS2}_20") (pintype "bidirectional"))
    )
    (net (code "124") (name "Net-(U9-(TXD)GPIO1-~{CS1})") (class "Default")
      (node (ref "JP2") (pin "1") (pinfunction "1_1") (pintype "passive"))
      (node (ref "U9") (pin "21") (pinfunction "(TXD)GPIO1-~{CS1}_21") (pintype "bidirectional"))
    )
    (net (code "125") (name "Net-(U9-VPP)") (class "Default")
      (node (ref "C26") (pin "P$1") (pinfunction "P$1_P$1") (pintype "bidirectional"))
      (node (ref "U9") (pin "16") (pinfunction "VPP_16") (pintype "bidirectional"))
    )
    (net (code "126") (name "Net-(U9-~{RST})") (class "Default")
      (node (ref "R11") (pin "P$2") (pinfunction "P$2_P$2") (pintype "bidirectional"))
      (node (ref "U9") (pin "9") (pinfunction "~{RST}_9") (pintype "bidirectional"))
    )
    (net (code "127") (name "Net-(U10E-IN+)") (class "Default")
      (node (ref "C16") (pin "P$2") (pinfunction "P$2_P$2") (pintype "bidirectional"))
      (node (ref "C32") (pin "P$1") (pinfunction "P$1_P$1") (pintype "bidirectional"))
      (node (ref "R97") (pin "P$2") (pinfunction "P$2_P$2") (pintype "bidirectional"))
      (node (ref "U10") (pin "8") (pinfunction "IN+_8") (pintype "bidirectional"))
    )
    (net (code "128") (name "Net-(U10E-IN-)") (class "Default")
      (node (ref "C16") (pin "P$1") (pinfunction "P$1_P$1") (pintype "bidirectional"))
      (node (ref "C17") (pin "P$2") (pinfunction "P$2_P$2") (pintype "bidirectional"))
      (node (ref "R96") (pin "P$2") (pinfunction "P$2_P$2") (pintype "bidirectional"))
      (node (ref "U10") (pin "1") (pinfunction "IN-_1") (pintype "bidirectional"))
    )
    (net (code "129") (name "Net-(U11E-IN+)") (class "Default")
      (node (ref "C33") (pin "P$2") (pinfunction "P$2_P$2") (pintype "bidirectional"))
      (node (ref "C53") (pin "P$1") (pinfunction "P$1_P$1") (pintype "bidirectional"))
      (node (ref "R99") (pin "P$2") (pinfunction "P$2_P$2") (pintype "bidirectional"))
      (node (ref "U11") (pin "8") (pinfunction "IN+_8") (pintype "bidirectional"))
    )
    (net (code "130") (name "Net-(U11E-IN-)") (class "Default")
      (node (ref "C33") (pin "P$1") (pinfunction "P$1_P$1") (pintype "bidirectional"))
      (node (ref "C46") (pin "P$2") (pinfunction "P$2_P$2") (pintype "bidirectional"))
      (node (ref "R98") (pin "P$2") (pinfunction "P$2_P$2") (pintype "bidirectional"))
      (node (ref "U11") (pin "1") (pinfunction "IN-_1") (pintype "bidirectional"))
    )
    (net (code "131") (name "Net-(U12-EN)") (class "Default")
      (node (ref "R25") (pin "P$1") (pinfunction "P$1_P$1") (pintype "bidirectional"))
      (node (ref "U12") (pin "1") (pinfunction "EN_1") (pintype "bidirectional"))
    )
    (net (code "132") (name "Net-(U12-OUT)") (class "Default")
      (node (ref "U1") (pin "51") (pinfunction "CLK_51") (pintype "bidirectional"))
      (node (ref "U12") (pin "4") (pinfunction "OUT_4") (pintype "bidirectional"))
    )
    (net (code "133") (name "Net-(U13A-A)") (class "Default")
      (node (ref "C78") (pin "P$1") (pinfunction "P$1_P$1") (pintype "bidirectional"))
      (node (ref "R48") (pin "P$2") (pinfunction "P$2_P$2") (pintype "bidirectional"))
      (node (ref "R67") (pin "P$2") (pinfunction "P$2_P$2") (pintype "bidirectional"))
      (node (ref "U13") (pin "1") (pinfunction "A_1") (pintype "input"))
      (node (ref "U19") (pin "6") (pinfunction "1_6") (pintype "bidirectional"))
    )
    (net (code "134") (name "Net-(U13B-A)") (class "Default")
      (node (ref "C79") (pin "P$1") (pinfunction "P$1_P$1") (pintype "bidirectional"))
      (node (ref "R49") (pin "P$2") (pinfunction "P$2_P$2") (pintype "bidirectional"))
      (node (ref "R68") (pin "P$2") (pinfunction "P$2_P$2") (pintype "bidirectional"))
      (node (ref "U13") (pin "3") (pinfunction "A_3") (pintype "input"))
      (node (ref "U19") (pin "1") (pinfunction "2_1") (pintype "bidirectional"))
    )
    (net (code "135") (name "Net-(U13C-A)") (class "Default")
      (node (ref "C80") (pin "P$1") (pinfunction "P$1_P$1") (pintype "bidirectional"))
      (node (ref "R50") (pin "P$2") (pinfunction "P$2_P$2") (pintype "bidirectional"))
      (node (ref "R69") (pin "P$2") (pinfunction "P$2_P$2") (pintype "bidirectional"))
      (node (ref "U13") (pin "6") (pinfunction "A_6") (pintype "input"))
      (node (ref "U19") (pin "3") (pinfunction "3_3") (pintype "bidirectional"))
    )
    (net (code "136") (name "Net-(U14A-A)") (class "Default")
      (node (ref "C82") (pin "P$1") (pinfunction "P$1_P$1") (pintype "bidirectional"))
      (node (ref "R51") (pin "P$2") (pinfunction "P$2_P$2") (pintype "bidirectional"))
      (node (ref "R64") (pin "P$2") (pinfunction "P$2_P$2") (pintype "bidirectional"))
      (node (ref "U14") (pin "1") (pinfunction "A_1") (pintype "input"))
      (node (ref "U18") (pin "6") (pinfunction "1_6") (pintype "bidirectional"))
    )
    (net (code "137") (name "Net-(U14B-A)") (class "Default")
      (node (ref "C83") (pin "P$1") (pinfunction "P$1_P$1") (pintype "bidirectional"))
      (node (ref "R52") (pin "P$2") (pinfunction "P$2_P$2") (pintype "bidirectional"))
      (node (ref "R65") (pin "P$2") (pinfunction "P$2_P$2") (pintype "bidirectional"))
      (node (ref "U14") (pin "3") (pinfunction "A_3") (pintype "input"))
      (node (ref "U18") (pin "1") (pinfunction "2_1") (pintype "bidirectional"))
    )
    (net (code "138") (name "Net-(U14C-A)") (class "Default")
      (node (ref "C84") (pin "P$1") (pinfunction "P$1_P$1") (pintype "bidirectional"))
      (node (ref "R53") (pin "P$2") (pinfunction "P$2_P$2") (pintype "bidirectional"))
      (node (ref "R66") (pin "P$2") (pinfunction "P$2_P$2") (pintype "bidirectional"))
      (node (ref "U14") (pin "6") (pinfunction "A_6") (pintype "input"))
      (node (ref "U18") (pin "3") (pinfunction "3_3") (pintype "bidirectional"))
    )
    (net (code "139") (name "Net-(U15A-A)") (class "Default")
      (node (ref "C86") (pin "P$1") (pinfunction "P$1_P$1") (pintype "bidirectional"))
      (node (ref "R54") (pin "P$2") (pinfunction "P$2_P$2") (pintype "bidirectional"))
      (node (ref "R61") (pin "P$2") (pinfunction "P$2_P$2") (pintype "bidirectional"))
      (node (ref "U15") (pin "1") (pinfunction "A_1") (pintype "input"))
      (node (ref "U20") (pin "6") (pinfunction "1_6") (pintype "bidirectional"))
    )
    (net (code "140") (name "Net-(U15B-A)") (class "Default")
      (node (ref "C87") (pin "P$1") (pinfunction "P$1_P$1") (pintype "bidirectional"))
      (node (ref "R57") (pin "P$2") (pinfunction "P$2_P$2") (pintype "bidirectional"))
      (node (ref "R62") (pin "P$2") (pinfunction "P$2_P$2") (pintype "bidirectional"))
      (node (ref "U15") (pin "3") (pinfunction "A_3") (pintype "input"))
      (node (ref "U20") (pin "1") (pinfunction "2_1") (pintype "bidirectional"))
    )
    (net (code "141") (name "Net-(U15C-A)") (class "Default")
      (node (ref "C88") (pin "P$1") (pinfunction "P$1_P$1") (pintype "bidirectional"))
      (node (ref "R60") (pin "P$2") (pinfunction "P$2_P$2") (pintype "bidirectional"))
      (node (ref "R63") (pin "P$2") (pinfunction "P$2_P$2") (pintype "bidirectional"))
      (node (ref "U15") (pin "6") (pinfunction "A_6") (pintype "input"))
      (node (ref "U20") (pin "3") (pinfunction "3_3") (pintype "bidirectional"))
    )
    (net (code "142") (name "Net-(U16A-A)") (class "Default")
      (node (ref "C96") (pin "P$1") (pinfunction "P$1_P$1") (pintype "bidirectional"))
      (node (ref "R70") (pin "P$2") (pinfunction "P$2_P$2") (pintype "bidirectional"))
      (node (ref "R73") (pin "P$2") (pinfunction "P$2_P$2") (pintype "bidirectional"))
      (node (ref "U16") (pin "1") (pinfunction "A_1") (pintype "input"))
      (node (ref "U21") (pin "6") (pinfunction "1_6") (pintype "bidirectional"))
    )
    (net (code "143") (name "Net-(U16B-A)") (class "Default")
      (node (ref "C97") (pin "P$1") (pinfunction "P$1_P$1") (pintype "bidirectional"))
      (node (ref "R71") (pin "P$2") (pinfunction "P$2_P$2") (pintype "bidirectional"))
      (node (ref "R74") (pin "P$2") (pinfunction "P$2_P$2") (pintype "bidirectional"))
      (node (ref "U16") (pin "3") (pinfunction "A_3") (pintype "input"))
      (node (ref "U21") (pin "1") (pinfunction "2_1") (pintype "bidirectional"))
    )
    (net (code "144") (name "Net-(U16C-A)") (class "Default")
      (node (ref "C98") (pin "P$1") (pinfunction "P$1_P$1") (pintype "bidirectional"))
      (node (ref "R72") (pin "P$2") (pinfunction "P$2_P$2") (pintype "bidirectional"))
      (node (ref "R75") (pin "P$2") (pinfunction "P$2_P$2") (pintype "bidirectional"))
      (node (ref "U16") (pin "6") (pinfunction "A_6") (pintype "input"))
      (node (ref "U21") (pin "3") (pinfunction "3_3") (pintype "bidirectional"))
    )
    (net (code "145") (name "Net-(U17-AN)") (class "Default")
      (node (ref "R88") (pin "P$1") (pinfunction "P$1_P$1") (pintype "bidirectional"))
      (node (ref "U17") (pin "2") (pinfunction "AN_2") (pintype "bidirectional"))
    )
    (net (code "146") (name "PWM_IN") (class "Default")
      (node (ref "D16") (pin "P$3") (pinfunction "3_P$3") (pintype "bidirectional"))
      (node (ref "R91") (pin "P$2") (pinfunction "P$2_P$2") (pintype "bidirectional"))
      (node (ref "R92") (pin "P$2") (pinfunction "P$2_P$2") (pintype "bidirectional"))
      (node (ref "U1") (pin "58") (pinfunction "PWM_IN_58") (pintype "bidirectional"))
    )
    (net (code "147") (name "PWM_UX1_H") (class "Default")
      (node (ref "R17") (pin "P$2") (pinfunction "P$2_P$2") (pintype "bidirectional"))
      (node (ref "U1") (pin "39") (pinfunction "PWM_UX1_H_39") (pintype "bidirectional"))
      (node (ref "U4") (pin "1") (pinfunction "VIA_1") (pintype "bidirectional"))
    )
    (net (code "148") (name "PWM_UX1_L") (class "Default")
      (node (ref "R18") (pin "P$2") (pinfunction "P$2_P$2") (pintype "bidirectional"))
      (node (ref "U1") (pin "40") (pinfunction "PWM_UX1_L_40") (pintype "bidirectional"))
      (node (ref "U4") (pin "2") (pinfunction "VIB_2") (pintype "bidirectional"))
    )
    (net (code "149") (name "PWM_VX2_H") (class "Default")
      (node (ref "R19") (pin "P$2") (pinfunction "P$2_P$2") (pintype "bidirectional"))
      (node (ref "U1") (pin "41") (pinfunction "PWM_VX2_H_41") (pintype "bidirectional"))
      (node (ref "U5") (pin "1") (pinfunction "VIA_1") (pintype "bidirectional"))
    )
    (net (code "150") (name "PWM_VX2_L") (class "Default")
      (node (ref "R20") (pin "P$2") (pinfunction "P$2_P$2") (pintype "bidirectional"))
      (node (ref "U1") (pin "42") (pinfunction "PWM_VX2_L_42") (pintype "bidirectional"))
      (node (ref "U5") (pin "2") (pinfunction "VIB_2") (pintype "bidirectional"))
    )
    (net (code "151") (name "PWM_WY1_H") (class "Default")
      (node (ref "R21") (pin "P$2") (pinfunction "P$2_P$2") (pintype "bidirectional"))
      (node (ref "U1") (pin "46") (pinfunction "PWM_WY1_H_46") (pintype "bidirectional"))
      (node (ref "U6") (pin "1") (pinfunction "VIA_1") (pintype "bidirectional"))
    )
    (net (code "152") (name "PWM_WY1_L") (class "Default")
      (node (ref "R22") (pin "P$2") (pinfunction "P$2_P$2") (pintype "bidirectional"))
      (node (ref "U1") (pin "47") (pinfunction "PWM_WY1_L_47") (pintype "bidirectional"))
      (node (ref "U6") (pin "2") (pinfunction "VIB_2") (pintype "bidirectional"))
    )
    (net (code "153") (name "PWM_Y2_H") (class "Default")
      (node (ref "R23") (pin "P$2") (pinfunction "P$2_P$2") (pintype "bidirectional"))
      (node (ref "U1") (pin "48") (pinfunction "PWM_Y2_H_48") (pintype "bidirectional"))
      (node (ref "U7") (pin "1") (pinfunction "VIA_1") (pintype "bidirectional"))
    )
    (net (code "154") (name "PWM_Y2_L") (class "Default")
      (node (ref "R24") (pin "P$2") (pinfunction "P$2_P$2") (pintype "bidirectional"))
      (node (ref "U1") (pin "49") (pinfunction "PWM_Y2_L_49") (pintype "bidirectional"))
      (node (ref "U7") (pin "2") (pinfunction "VIB_2") (pintype "bidirectional"))
    )
    (net (code "155") (name "REF_H") (class "Default")
      (node (ref "U1") (pin "68") (pinfunction "REF_H_68") (pintype "bidirectional"))
      (node (ref "U16") (pin "5") (pinfunction "Y_5") (pintype "output"))
    )
    (net (code "156") (name "REF_L") (class "Default")
      (node (ref "U1") (pin "67") (pinfunction "REF_L_67") (pintype "bidirectional"))
      (node (ref "U16") (pin "2") (pinfunction "Y_2") (pintype "output"))
    )
    (net (code "157") (name "REF_R") (class "Default")
      (node (ref "U1") (pin "69") (pinfunction "REF_R_69") (pintype "bidirectional"))
      (node (ref "U16") (pin "7") (pinfunction "Y_7") (pintype "output"))
    )
    (net (code "158") (name "SCK") (class "Default")
      (node (ref "J16") (pin "2") (pinfunction "S_2") (pintype "passive"))
      (node (ref "JP5") (pin "2") (pinfunction "2_2") (pintype "passive"))
      (node (ref "U1") (pin "7") (pinfunction "SPI_SCK_7") (pintype "bidirectional"))
    )
    (net (code "159") (name "STEP") (class "Default")
      (node (ref "D15") (pin "P$3") (pinfunction "3_P$3") (pintype "bidirectional"))
      (node (ref "R41") (pin "P$2") (pinfunction "P$2_P$2") (pintype "bidirectional"))
      (node (ref "R89") (pin "P$2") (pinfunction "P$2_P$2") (pintype "bidirectional"))
      (node (ref "U1") (pin "57") (pinfunction "STP_57") (pintype "bidirectional"))
    )
    (net (code "160") (name "UX1") (class "Default")
      (node (ref "C34") (pin "P$2") (pinfunction "P$2_P$2") (pintype "bidirectional"))
      (node (ref "Q1") (pin "S1") (pinfunction "S1_S1") (pintype "bidirectional"))
      (node (ref "Q1") (pin "S2") (pinfunction "S1_S2") (pintype "bidirectional"))
      (node (ref "Q1") (pin "S3") (pinfunction "S1_S3") (pintype "bidirectional"))
      (node (ref "Q1") (pin "S4") (pinfunction "S1_S4") (pintype "bidirectional"))
      (node (ref "Q1") (pin "S5") (pinfunction "S1_S5") (pintype "bidirectional"))
      (node (ref "Q2") (pin "D1") (pinfunction "D1_D1") (pintype "bidirectional"))
      (node (ref "Q2") (pin "D2") (pinfunction "D1_D2") (pintype "bidirectional"))
      (node (ref "Q2") (pin "D3") (pinfunction "D1_D3") (pintype "bidirectional"))
      (node (ref "Q2") (pin "D4") (pinfunction "D1_D4") (pintype "bidirectional"))
      (node (ref "R9") (pin "1") (pinfunction "P$1_1") (pintype "bidirectional"))
      (node (ref "R9") (pin "2") (pinfunction "P$1_2") (pintype "bidirectional"))
      (node (ref "U4") (pin "14") (pinfunction "GNDA_14") (pintype "bidirectional"))
    )
    (net (code "161") (name "VBUS") (class "Default")
      (node (ref "R12") (pin "P$2") (pinfunction "P$2_P$2") (pintype "bidirectional"))
      (node (ref "R13") (pin "P$1") (pinfunction "P$1_P$1") (pintype "bidirectional"))
      (node (ref "U9") (pin "8") (pinfunction "VBUS_8") (pintype "bidirectional"))
    )
    (net (code "162") (name "VX2") (class "Default")
      (node (ref "C35") (pin "P$2") (pinfunction "P$2_P$2") (pintype "bidirectional"))
      (node (ref "Q3") (pin "S1") (pinfunction "S1_S1") (pintype "bidirectional"))
      (node (ref "Q3") (pin "S2") (pinfunction "S1_S2") (pintype "bidirectional"))
      (node (ref "Q3") (pin "S3") (pinfunction "S1_S3") (pintype "bidirectional"))
      (node (ref "Q3") (pin "S4") (pinfunction "S1_S4") (pintype "bidirectional"))
      (node (ref "Q3") (pin "S5") (pinfunction "S1_S5") (pintype "bidirectional"))
      (node (ref "Q4") (pin "D1") (pinfunction "D1_D1") (pintype "bidirectional"))
      (node (ref "Q4") (pin "D2") (pinfunction "D1_D2") (pintype "bidirectional"))
      (node (ref "Q4") (pin "D3") (pinfunction "D1_D3") (pintype "bidirectional"))
      (node (ref "Q4") (pin "D4") (pinfunction "D1_D4") (pintype "bidirectional"))
      (node (ref "R10") (pin "1") (pinfunction "P$1_1") (pintype "bidirectional"))
      (node (ref "R10") (pin "2") (pinfunction "P$1_2") (pintype "bidirectional"))
      (node (ref "U5") (pin "14") (pinfunction "GNDA_14") (pintype "bidirectional"))
    )
    (net (code "163") (name "WY1") (class "Default")
      (node (ref "C37") (pin "P$2") (pinfunction "P$2_P$2") (pintype "bidirectional"))
      (node (ref "J3") (pin "3") (pinfunction "S_3") (pintype "passive"))
      (node (ref "P3") (pin "H1") (pinfunction "S_H1") (pintype "passive"))
      (node (ref "P3") (pin "H10") (pinfunction "S_H10") (pintype "passive"))
      (node (ref "P3") (pin "H11") (pinfunction "S_H11") (pintype "passive"))
      (node (ref "P3") (pin "H12") (pinfunction "S_H12") (pintype "passive"))
      (node (ref "P3") (pin "H2") (pinfunction "S_H2") (pintype "passive"))
      (node (ref "P3") (pin "H3") (pinfunction "S_H3") (pintype "passive"))
      (node (ref "P3") (pin "H4") (pinfunction "S_H4") (pintype "passive"))
      (node (ref "P3") (pin "H5") (pinfunction "S_H5") (pintype "passive"))
      (node (ref "P3") (pin "H6") (pinfunction "S_H6") (pintype "passive"))
      (node (ref "P3") (pin "H7") (pinfunction "S_H7") (pintype "passive"))
      (node (ref "P3") (pin "H8") (pinfunction "S_H8") (pintype "passive"))
      (node (ref "P3") (pin "H9") (pinfunction "S_H9") (pintype "passive"))
      (node (ref "P3") (pin "PAD") (pinfunction "S_PAD") (pintype "passive"))
      (node (ref "Q5") (pin "S1") (pinfunction "S1_S1") (pintype "bidirectional"))
      (node (ref "Q5") (pin "S2") (pinfunction "S1_S2") (pintype "bidirectional"))
      (node (ref "Q5") (pin "S3") (pinfunction "S1_S3") (pintype "bidirectional"))
      (node (ref "Q5") (pin "S4") (pinfunction "S1_S4") (pintype "bidirectional"))
      (node (ref "Q5") (pin "S5") (pinfunction "S1_S5") (pintype "bidirectional"))
      (node (ref "Q6") (pin "D1") (pinfunction "D1_D1") (pintype "bidirectional"))
      (node (ref "Q6") (pin "D2") (pinfunction "D1_D2") (pintype "bidirectional"))
      (node (ref "Q6") (pin "D3") (pinfunction "D1_D3") (pintype "bidirectional"))
      (node (ref "Q6") (pin "D4") (pinfunction "D1_D4") (pintype "bidirectional"))
      (node (ref "U6") (pin "14") (pinfunction "GNDA_14") (pintype "bidirectional"))
    )
    (net (code "164") (name "Y2") (class "Default")
      (node (ref "C38") (pin "P$2") (pinfunction "P$2_P$2") (pintype "bidirectional"))
      (node (ref "J3") (pin "4") (pinfunction "S_4") (pintype "passive"))
      (node (ref "P4") (pin "H1") (pinfunction "S_H1") (pintype "passive"))
      (node (ref "P4") (pin "H10") (pinfunction "S_H10") (pintype "passive"))
      (node (ref "P4") (pin "H11") (pinfunction "S_H11") (pintype "passive"))
      (node (ref "P4") (pin "H12") (pinfunction "S_H12") (pintype "passive"))
      (node (ref "P4") (pin "H2") (pinfunction "S_H2") (pintype "passive"))
      (node (ref "P4") (pin "H3") (pinfunction "S_H3") (pintype "passive"))
      (node (ref "P4") (pin "H4") (pinfunction "S_H4") (pintype "passive"))
      (node (ref "P4") (pin "H5") (pinfunction "S_H5") (pintype "passive"))
      (node (ref "P4") (pin "H6") (pinfunction "S_H6") (pintype "passive"))
      (node (ref "P4") (pin "H7") (pinfunction "S_H7") (pintype "passive"))
      (node (ref "P4") (pin "H8") (pinfunction "S_H8") (pintype "passive"))
      (node (ref "P4") (pin "H9") (pinfunction "S_H9") (pintype "passive"))
      (node (ref "P4") (pin "PAD") (pinfunction "S_PAD") (pintype "passive"))
      (node (ref "Q7") (pin "S1") (pinfunction "S1_S1") (pintype "bidirectional"))
      (node (ref "Q7") (pin "S2") (pinfunction "S1_S2") (pintype "bidirectional"))
      (node (ref "Q7") (pin "S3") (pinfunction "S1_S3") (pintype "bidirectional"))
      (node (ref "Q7") (pin "S4") (pinfunction "S1_S4") (pintype "bidirectional"))
      (node (ref "Q7") (pin "S5") (pinfunction "S1_S5") (pintype "bidirectional"))
      (node (ref "Q8") (pin "D1") (pinfunction "D1_D1") (pintype "bidirectional"))
      (node (ref "Q8") (pin "D2") (pinfunction "D1_D2") (pintype "bidirectional"))
      (node (ref "Q8") (pin "D3") (pinfunction "D1_D3") (pintype "bidirectional"))
      (node (ref "Q8") (pin "D4") (pinfunction "D1_D4") (pintype "bidirectional"))
      (node (ref "U7") (pin "14") (pinfunction "GNDA_14") (pintype "bidirectional"))
    )
    (net (code "165") (name "unconnected-(J14C-S-Pad2)") (class "Default")
      (node (ref "J14") (pin "2") (pinfunction "S_2") (pintype "passive"))
    )
    (net (code "166") (name "unconnected-(U1A-ENI-Pad55)") (class "Default")
      (node (ref "U1") (pin "55") (pinfunction "ENI_55") (pintype "bidirectional"))
    )
    (net (code "167") (name "unconnected-(U9-(GPIO2-RS485)GPIO9-~{CS9}-SUSPEND-Pad12)") (class "Default")
      (node (ref "U9") (pin "12") (pinfunction "(GPIO2-RS485)GPIO9-~{CS9}-SUSPEND_12") (pintype "bidirectional"))
    )
    (net (code "168") (name "unconnected-(U9-(GPIO3-WKUP)GPIO10-~{CS10}-~{SUSPEND}-Pad11)") (class "Default")
      (node (ref "U9") (pin "11") (pinfunction "(GPIO3-WKUP)GPIO10-~{CS10}-~{SUSPEND}_11") (pintype "bidirectional"))
    )
    (net (code "169") (name "unconnected-(U9-(RTS)GPIO3-~{CS3}-RTR-Pad19)") (class "Default")
      (node (ref "U9") (pin "19") (pinfunction "(RTS)GPIO3-~{CS3}-RTR_19") (pintype "bidirectional"))
    )
    (net (code "170") (name "unconnected-(U9-(SUSPEND)GPIO5-~{CS5}-CLKOUT-Pad17)") (class "Default")
      (node (ref "U9") (pin "17") (pinfunction "(SUSPEND)GPIO5-~{CS5}-CLKOUT_17") (pintype "bidirectional"))
    )
    (net (code "171") (name "unconnected-(U9-(~{SUSPEND})GPIO6-~{CS6}-Pad15)") (class "Default")
      (node (ref "U9") (pin "15") (pinfunction "(~{SUSPEND})GPIO6-~{CS6}_15") (pintype "bidirectional"))
    )
    (net (code "172") (name "unconnected-(U18-Pad4)") (class "Default")
      (node (ref "U18") (pin "4") (pinfunction "4_4") (pintype "bidirectional"))
    )
    (net (code "173") (name "unconnected-(U19-Pad4)") (class "Default")
      (node (ref "U19") (pin "4") (pinfunction "4_4") (pintype "bidirectional"))
    )
    (net (code "174") (name "unconnected-(U20-Pad4)") (class "Default")
      (node (ref "U20") (pin "4") (pinfunction "4_4") (pintype "bidirectional"))
    )
    (net (code "175") (name "unconnected-(U21-Pad4)") (class "Default")
      (node (ref "U21") (pin "4") (pinfunction "4_4") (pintype "bidirectional"))
    )
    (net (code "176") (name "~{CS}") (class "Default")
      (node (ref "J16") (pin "1") (pinfunction "S_1") (pintype "passive"))
      (node (ref "JP7") (pin "2") (pinfunction "2_2") (pintype "passive"))
      (node (ref "U1") (pin "6") (pinfunction "SPI_NSCS_6") (pintype "bidirectional"))
    )
  )
)
